# EgSA-Cube3.net
KiCad netlist of a schematic drawn in Altium Designer
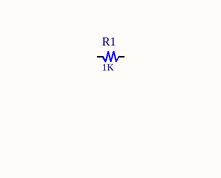
[diagram p0: EgSA-Cube3.SchDoc, top right]
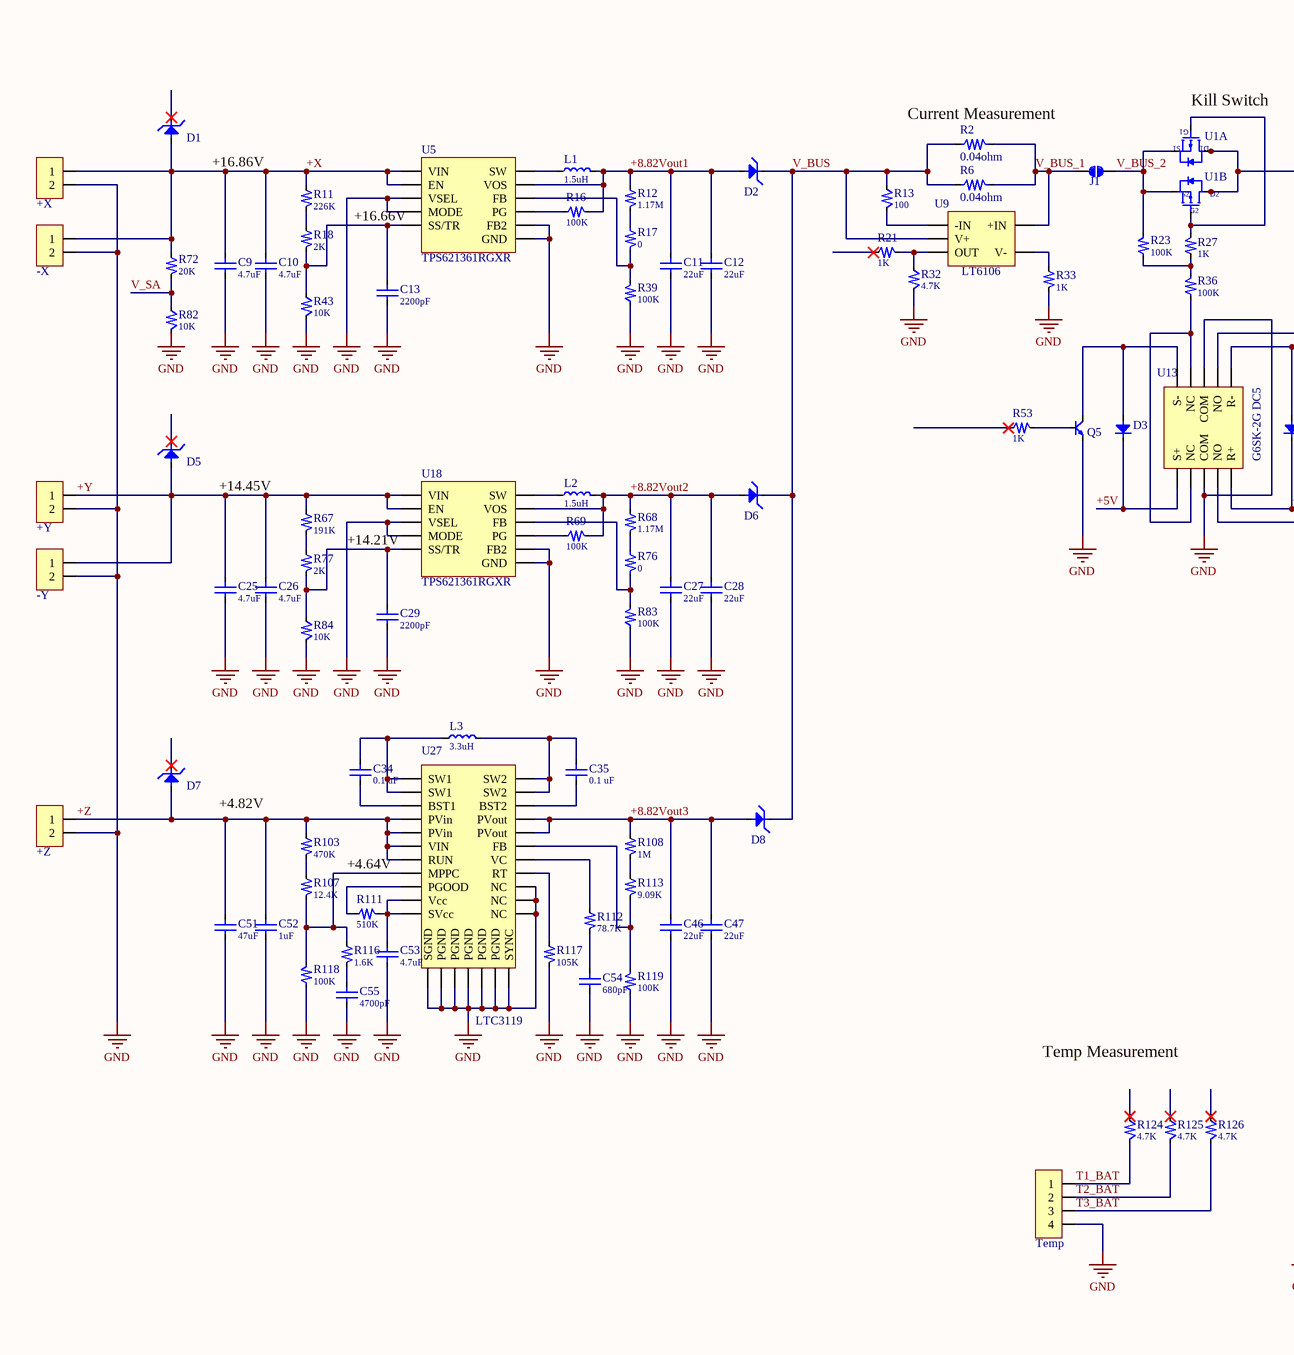
[diagram p1: EgSA-Cube3.SchDoc, bottom left]
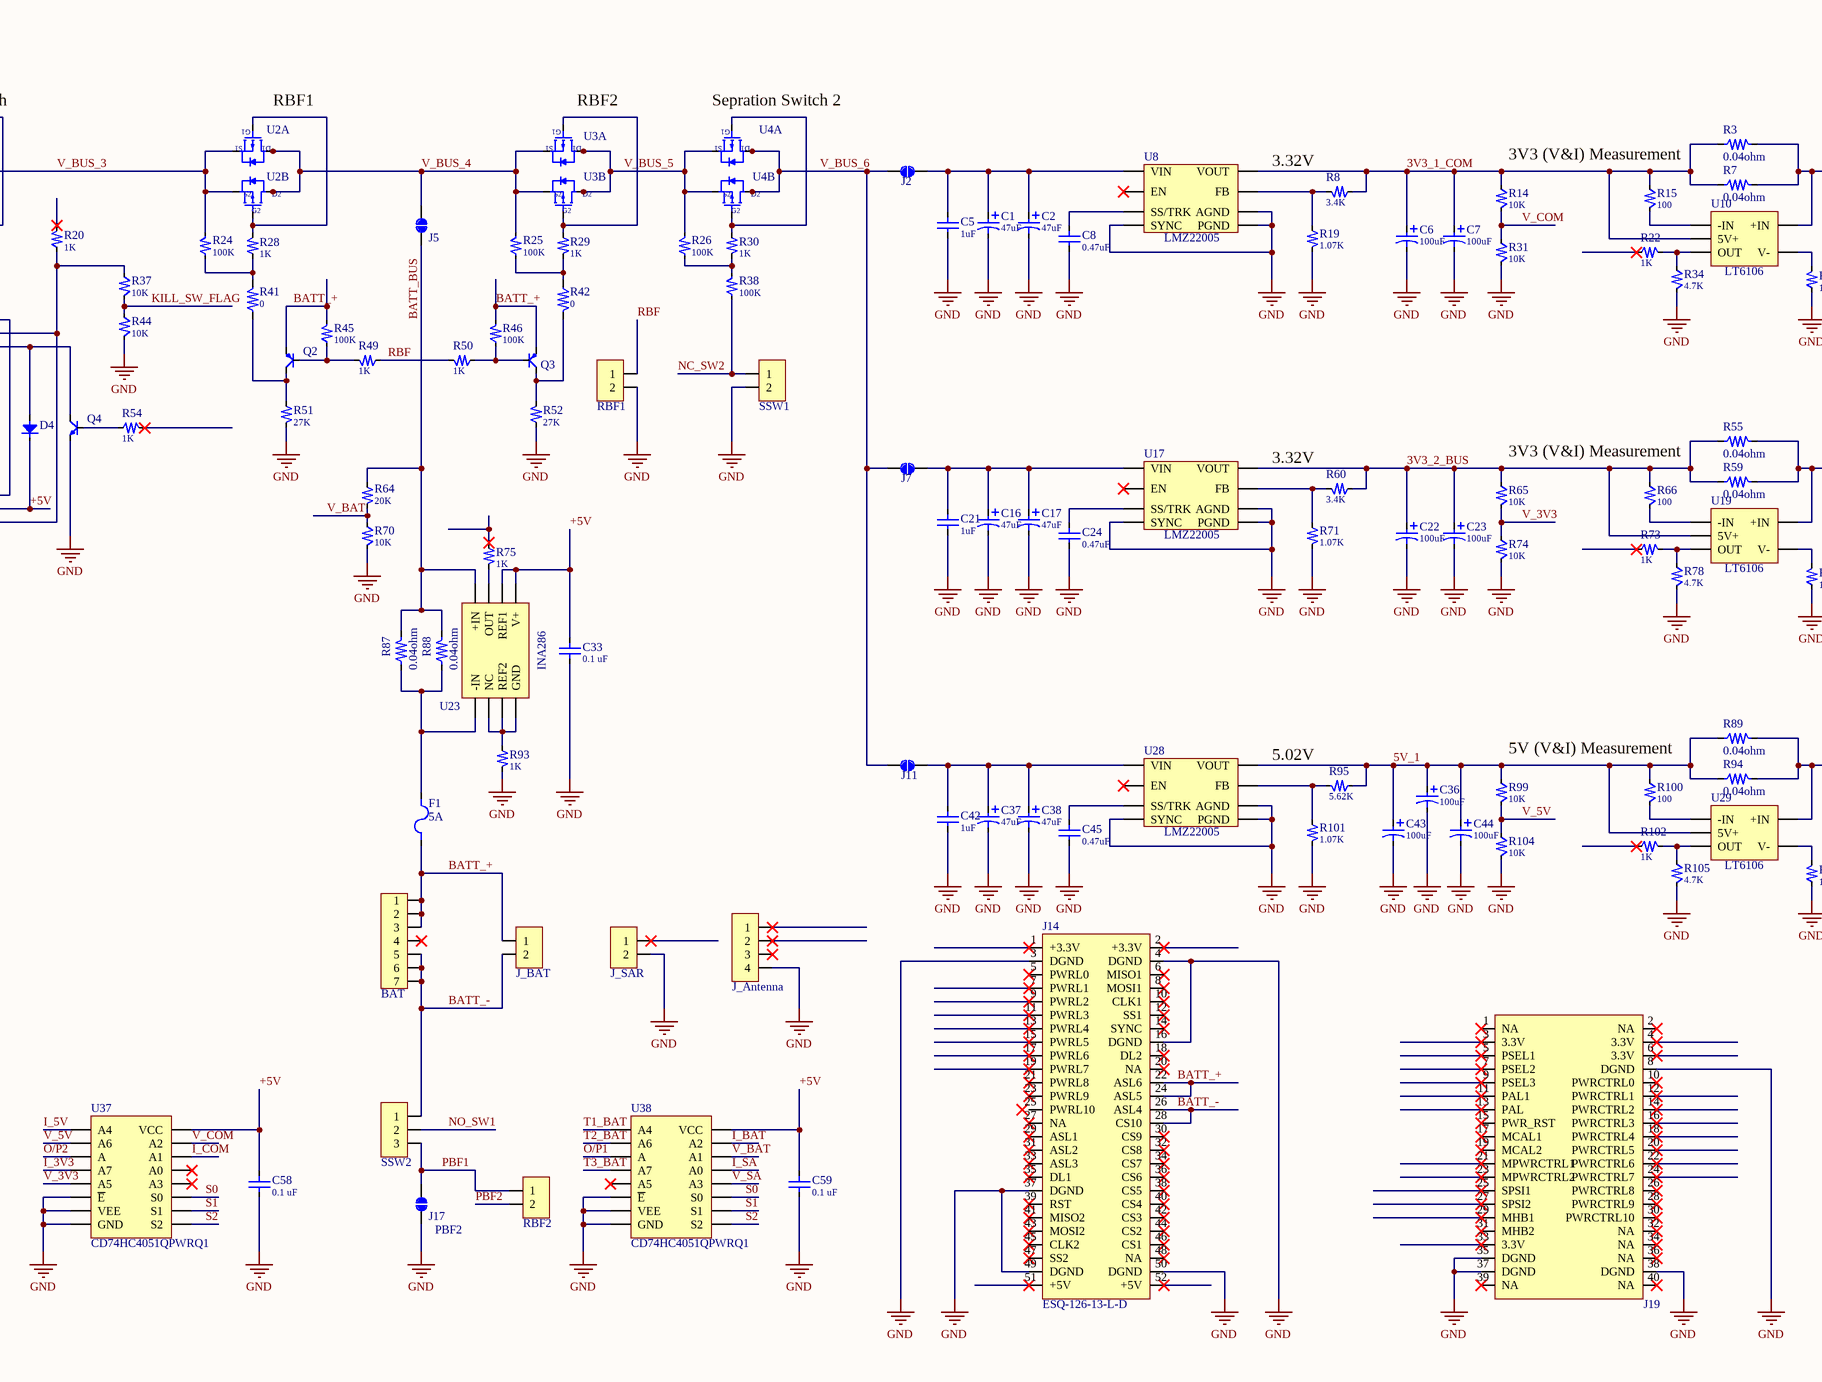
[diagram p2: EgSA-Cube3.SchDoc, bottom middle]
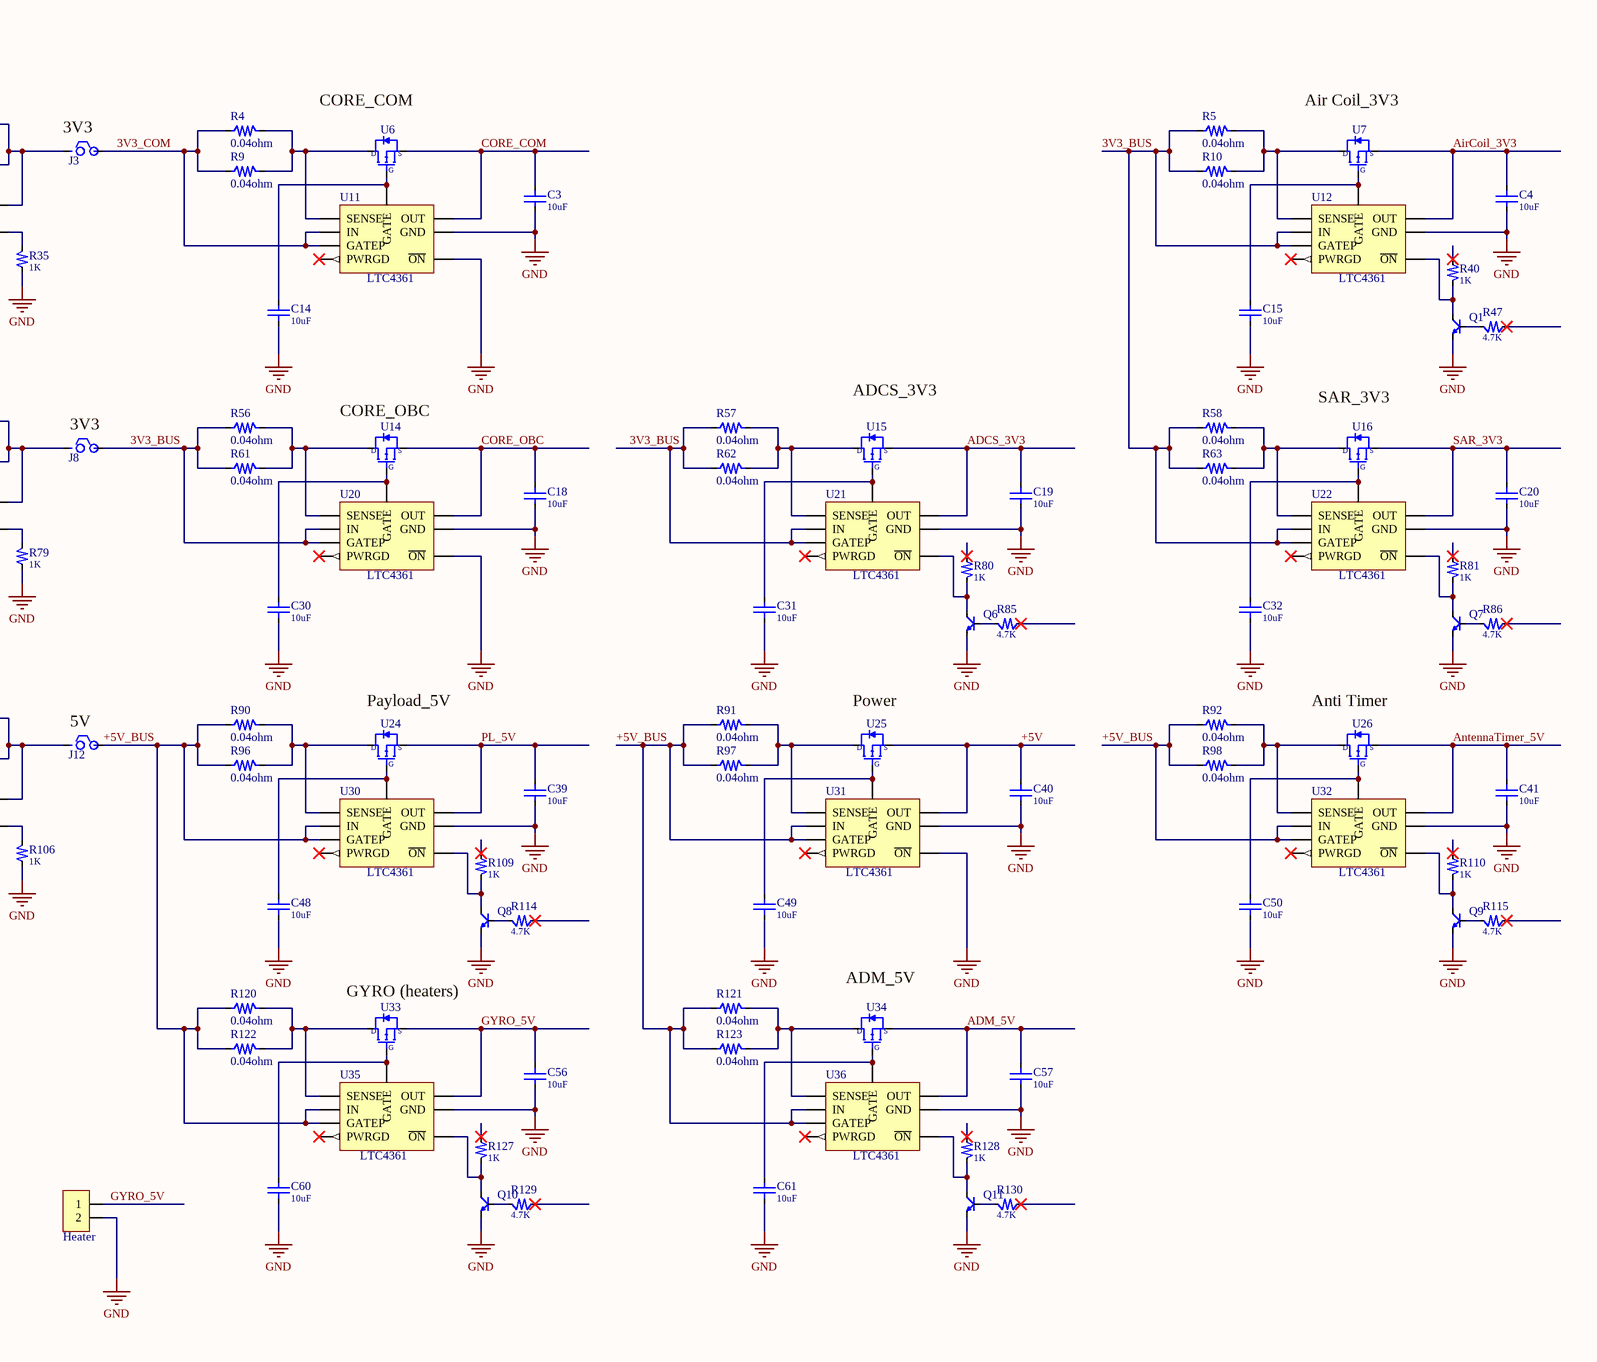
[diagram p3: EgSA-Cube3.SchDoc, bottom right]

(export (version "E")
  (design (tool "Eeschema 10.0.6"))
  (components
    (comp (ref "+X")
      (value "53261-0271")
      (footprint "53261-0271")
      (description "CONN HEADER SMD R/A 2POS 1.25MM")
      (fields
        (field (name "MANUFACTURER") "Molex, LLC")
        (field (name "MANUFACTURER PART NUMBER") "0532610271")
      )
      (libsource (lib "") (part "53261-0271_1"))
    )
    (comp (ref "+Y")
      (value "53261-0271")
      (footprint "53261-0271")
      (description "CONN HEADER SMD R/A 2POS 1.25MM")
      (fields
        (field (name "MANUFACTURER") "Molex, LLC")
        (field (name "MANUFACTURER PART NUMBER") "0532610271")
      )
      (libsource (lib "") (part "53261-0271_1"))
    )
    (comp (ref "+Z")
      (value "53261-0271")
      (footprint "53261-0271")
      (description "CONN HEADER SMD R/A 2POS 1.25MM")
      (fields
        (field (name "MANUFACTURER") "Molex, LLC")
        (field (name "MANUFACTURER PART NUMBER") "0532610271")
      )
      (libsource (lib "") (part "53261-0271_1"))
    )
    (comp (ref "-X")
      (value "53261-0271")
      (footprint "53261-0271")
      (description "CONN HEADER SMD R/A 2POS 1.25MM")
      (fields
        (field (name "MANUFACTURER") "Molex, LLC")
        (field (name "MANUFACTURER PART NUMBER") "0532610271")
      )
      (libsource (lib "") (part "53261-0271_1"))
    )
    (comp (ref "-Y")
      (value "53261-0271")
      (footprint "53261-0271")
      (description "CONN HEADER SMD R/A 2POS 1.25MM")
      (fields
        (field (name "MANUFACTURER") "Molex, LLC")
        (field (name "MANUFACTURER PART NUMBER") "0532610271")
      )
      (libsource (lib "") (part "53261-0271_1"))
    )
    (comp (ref "BAT")
      (value "53261-0771")
      (footprint "53261-0771")
      (description "CONN HEADER SMD R/A 7POS 1.25MM")
      (fields (field (name "MANUFACTURER") "Molex"))
      (libsource (lib "All_N_Cube3_Components") (part "53261-0771"))
    )
    (comp (ref "C1")
      (value "47uF")
      (footprint "T591B476M010ATE070")
      (description "CAP TANT POLY 47UF 10V 1411")
      (fields
        (field (name "MANUFACTURER") "KEMET")
        (field (name "MANUFACTURER PART NUMBER") "T591B476M010ATE070")
      )
      (libsource (lib "All_N_Cube3_Components") (part "T591B476M010ATE070"))
    )
    (comp (ref "C2")
      (value "47uF")
      (footprint "T591B476M010ATE070")
      (description "CAP TANT POLY 47UF 10V 1411")
      (fields
        (field (name "MANUFACTURER") "KEMET")
        (field (name "MANUFACTURER PART NUMBER") "T591B476M010ATE070")
      )
      (libsource (lib "All_N_Cube3_Components") (part "T591B476M010ATE070"))
    )
    (comp (ref "C3")
      (value "10uF")
      (footprint "CL21B106KOQNNNE")
      (description "CAP CER 10UF 16V X7R 0805")
      (fields
        (field (name "MANUFACTURER") "Samsung Electro-Mechanics")
        (field (name "MANUFACTURER PART NUMBER") "CL21B106KOQNNNE")
      )
      (libsource (lib "All_N_Cube3_Components") (part "CL21B106KOQNNNE"))
    )
    (comp (ref "C4")
      (value "10uF")
      (footprint "CL21B106KOQNNNE")
      (description "CAP CER 10UF 16V X7R 0805")
      (fields
        (field (name "MANUFACTURER") "Samsung Electro-Mechanics")
        (field (name "MANUFACTURER PART NUMBER") "CL21B106KOQNNNE")
      )
      (libsource (lib "All_N_Cube3_Components") (part "CL21B106KOQNNNE"))
    )
    (comp (ref "C5")
      (value "1uF")
      (footprint "CL21B105KAFVPNE")
      (description "CAP CER 1UF 25V X7R 0805")
      (fields
        (field (name "MANUFACTURER") "Samsung")
        (field (name "MANUFACTURER PART NUMBER") "CL21B105KAFVPNE")
      )
      (libsource (lib "All_N_Cube3_Components") (part "CL21B105KAFVPNE"))
    )
    (comp (ref "C6")
      (value "100uF")
      (footprint "T520B107M006ATE018")
      (description "CAP TANT POLY 100UF 6.3V 1411")
      (fields
        (field (name "MANUFACTURER") "KEMET")
        (field (name "MANUFACTURER PART NUMBER") "T520B107M006ATE018")
      )
      (libsource (lib "All_N_Cube3_Components") (part "T520B107M006ATE018"))
    )
    (comp (ref "C7")
      (value "100uF")
      (footprint "T520B107M006ATE018")
      (description "CAP TANT POLY 100UF 6.3V 1411")
      (fields
        (field (name "MANUFACTURER") "KEMET")
        (field (name "MANUFACTURER PART NUMBER") "T520B107M006ATE018")
      )
      (libsource (lib "All_N_Cube3_Components") (part "T520B107M006ATE018"))
    )
    (comp (ref "C8")
      (value "0.47uF")
      (footprint "0805YC474KAT2A")
      (description "CAP CER 0.47UF 16V X7R 0805")
      (fields
        (field (name "MANUFACTURER") "Kyocera AVX")
        (field (name "MANUFACTURER PART NUMBER") "0805YC474KAT2A")
      )
      (libsource (lib "All_N_Cube3_Components") (part "0805YC474KAT2A"))
    )
    (comp (ref "C9")
      (value "4.7uF")
      (footprint "CGA4J1X7R1V475K125AC")
      (description "CAP CER 4.7UF 35V X7R 0805")
      (fields
        (field (name "MANUFACTURER") "TDK")
        (field (name "MANUFACTURER PART NUMBER") "CGA4J1X7R1V475K125AC")
      )
      (libsource (lib "All_N_Cube3_Components") (part "CGA4J1X7R1V475K125AC"))
    )
    (comp (ref "C10")
      (value "4.7uF")
      (footprint "CGA4J1X7R1V475K125AC")
      (description "CAP CER 4.7UF 35V X7R 0805")
      (fields
        (field (name "MANUFACTURER") "TDK")
        (field (name "MANUFACTURER PART NUMBER") "CGA4J1X7R1V475K125AC")
      )
      (libsource (lib "All_N_Cube3_Components") (part "CGA4J1X7R1V475K125AC"))
    )
    (comp (ref "C11")
      (value "22uF")
      (footprint "C2012X5R1C226M125AC")
      (description "CAP CER 22UF 16V X5R 0805")
      (fields
        (field (name "MANUFACTURER") "TDK")
        (field (name "MANUFACTURER PART NUMBER") "C2012X5R1C226M125AC")
      )
      (libsource (lib "All_N_Cube3_Components") (part "C2012X5R1C226M125AC"))
    )
    (comp (ref "C12")
      (value "22uF")
      (footprint "C2012X5R1C226M125AC")
      (description "CAP CER 22UF 16V X5R 0805")
      (fields
        (field (name "MANUFACTURER") "TDK")
        (field (name "MANUFACTURER PART NUMBER") "C2012X5R1C226M125AC")
      )
      (libsource (lib "All_N_Cube3_Components") (part "C2012X5R1C226M125AC"))
    )
    (comp (ref "C13")
      (value "2200pF")
      (footprint "VJ0805Y222KXACW1BC")
      (description "CAP CER 2200PF 50V X7R 0805")
      (fields
        (field (name "MANUFACTURER") "Vishay")
        (field (name "MANUFACTURER PART NUMBER") "VJ0805Y222KXACW1BC")
      )
      (libsource (lib "All_N_Cube3_Components") (part "VJ0805Y222KXACW1BC"))
    )
    (comp (ref "C14")
      (value "10uF")
      (footprint "CL21B106KOQNNNE")
      (description "CAP CER 10UF 16V X7R 0805")
      (fields
        (field (name "MANUFACTURER") "Samsung Electro-Mechanics")
        (field (name "MANUFACTURER PART NUMBER") "CL21B106KOQNNNE")
      )
      (libsource (lib "All_N_Cube3_Components") (part "CL21B106KOQNNNE"))
    )
    (comp (ref "C15")
      (value "10uF")
      (footprint "CL21B106KOQNNNE")
      (description "CAP CER 10UF 16V X7R 0805")
      (fields
        (field (name "MANUFACTURER") "Samsung Electro-Mechanics")
        (field (name "MANUFACTURER PART NUMBER") "CL21B106KOQNNNE")
      )
      (libsource (lib "All_N_Cube3_Components") (part "CL21B106KOQNNNE"))
    )
    (comp (ref "C16")
      (value "47uF")
      (footprint "T591B476M010ATE070")
      (description "CAP TANT POLY 47UF 10V 1411")
      (fields
        (field (name "MANUFACTURER") "KEMET")
        (field (name "MANUFACTURER PART NUMBER") "T591B476M010ATE070")
      )
      (libsource (lib "All_N_Cube3_Components") (part "T591B476M010ATE070"))
    )
    (comp (ref "C17")
      (value "47uF")
      (footprint "T591B476M010ATE070")
      (description "CAP TANT POLY 47UF 10V 1411")
      (fields
        (field (name "MANUFACTURER") "KEMET")
        (field (name "MANUFACTURER PART NUMBER") "T591B476M010ATE070")
      )
      (libsource (lib "All_N_Cube3_Components") (part "T591B476M010ATE070"))
    )
    (comp (ref "C18")
      (value "10uF")
      (footprint "CL21B106KOQNNNE")
      (description "CAP CER 10UF 16V X7R 0805")
      (fields
        (field (name "MANUFACTURER") "Samsung Electro-Mechanics")
        (field (name "MANUFACTURER PART NUMBER") "CL21B106KOQNNNE")
      )
      (libsource (lib "All_N_Cube3_Components") (part "CL21B106KOQNNNE"))
    )
    (comp (ref "C19")
      (value "10uF")
      (footprint "CL21B106KOQNNNE")
      (description "CAP CER 10UF 16V X7R 0805")
      (fields
        (field (name "MANUFACTURER") "Samsung Electro-Mechanics")
        (field (name "MANUFACTURER PART NUMBER") "CL21B106KOQNNNE")
      )
      (libsource (lib "All_N_Cube3_Components") (part "CL21B106KOQNNNE"))
    )
    (comp (ref "C20")
      (value "10uF")
      (footprint "CL21B106KOQNNNE")
      (description "CAP CER 10UF 16V X7R 0805")
      (fields
        (field (name "MANUFACTURER") "Samsung Electro-Mechanics")
        (field (name "MANUFACTURER PART NUMBER") "CL21B106KOQNNNE")
      )
      (libsource (lib "All_N_Cube3_Components") (part "CL21B106KOQNNNE"))
    )
    (comp (ref "C21")
      (value "1uF")
      (footprint "CL21B105KAFVPNE")
      (description "CAP CER 1UF 25V X7R 0805")
      (fields
        (field (name "MANUFACTURER") "Samsung")
        (field (name "MANUFACTURER PART NUMBER") "CL21B105KAFVPNE")
      )
      (libsource (lib "All_N_Cube3_Components") (part "CL21B105KAFVPNE"))
    )
    (comp (ref "C22")
      (value "100uF")
      (footprint "T520B107M006ATE018")
      (description "CAP TANT POLY 100UF 6.3V 1411")
      (fields
        (field (name "MANUFACTURER") "KEMET")
        (field (name "MANUFACTURER PART NUMBER") "T520B107M006ATE018")
      )
      (libsource (lib "All_N_Cube3_Components") (part "T520B107M006ATE018"))
    )
    (comp (ref "C23")
      (value "100uF")
      (footprint "T520B107M006ATE018")
      (description "CAP TANT POLY 100UF 6.3V 1411")
      (fields
        (field (name "MANUFACTURER") "KEMET")
        (field (name "MANUFACTURER PART NUMBER") "T520B107M006ATE018")
      )
      (libsource (lib "All_N_Cube3_Components") (part "T520B107M006ATE018"))
    )
    (comp (ref "C24")
      (value "0.47uF")
      (footprint "0805YC474KAT2A")
      (description "CAP CER 0.47UF 16V X7R 0805")
      (fields
        (field (name "MANUFACTURER") "Kyocera AVX")
        (field (name "MANUFACTURER PART NUMBER") "0805YC474KAT2A")
      )
      (libsource (lib "All_N_Cube3_Components") (part "0805YC474KAT2A"))
    )
    (comp (ref "C25")
      (value "4.7uF")
      (footprint "CGA4J1X7R1V475K125AC")
      (description "CAP CER 4.7UF 35V X7R 0805")
      (fields
        (field (name "MANUFACTURER") "TDK")
        (field (name "MANUFACTURER PART NUMBER") "CGA4J1X7R1V475K125AC")
      )
      (libsource (lib "All_N_Cube3_Components") (part "CGA4J1X7R1V475K125AC"))
    )
    (comp (ref "C26")
      (value "4.7uF")
      (footprint "CGA4J1X7R1V475K125AC")
      (description "CAP CER 4.7UF 35V X7R 0805")
      (fields
        (field (name "MANUFACTURER") "TDK")
        (field (name "MANUFACTURER PART NUMBER") "CGA4J1X7R1V475K125AC")
      )
      (libsource (lib "All_N_Cube3_Components") (part "CGA4J1X7R1V475K125AC"))
    )
    (comp (ref "C27")
      (value "22uF")
      (footprint "C2012X5R1C226M125AC")
      (description "CAP CER 22UF 16V X5R 0805")
      (fields
        (field (name "MANUFACTURER") "TDK")
        (field (name "MANUFACTURER PART NUMBER") "C2012X5R1C226M125AC")
      )
      (libsource (lib "All_N_Cube3_Components") (part "C2012X5R1C226M125AC"))
    )
    (comp (ref "C28")
      (value "22uF")
      (footprint "C2012X5R1C226M125AC")
      (description "CAP CER 22UF 16V X5R 0805")
      (fields
        (field (name "MANUFACTURER") "TDK")
        (field (name "MANUFACTURER PART NUMBER") "C2012X5R1C226M125AC")
      )
      (libsource (lib "All_N_Cube3_Components") (part "C2012X5R1C226M125AC"))
    )
    (comp (ref "C29")
      (value "2200pF")
      (footprint "VJ0805Y222KXACW1BC")
      (description "CAP CER 2200PF 50V X7R 0805")
      (fields
        (field (name "MANUFACTURER") "Vishay")
        (field (name "MANUFACTURER PART NUMBER") "VJ0805Y222KXACW1BC")
      )
      (libsource (lib "All_N_Cube3_Components") (part "VJ0805Y222KXACW1BC"))
    )
    (comp (ref "C30")
      (value "10uF")
      (footprint "CL21B106KOQNNNE")
      (description "CAP CER 10UF 16V X7R 0805")
      (fields
        (field (name "MANUFACTURER") "Samsung Electro-Mechanics")
        (field (name "MANUFACTURER PART NUMBER") "CL21B106KOQNNNE")
      )
      (libsource (lib "All_N_Cube3_Components") (part "CL21B106KOQNNNE"))
    )
    (comp (ref "C31")
      (value "10uF")
      (footprint "CL21B106KOQNNNE")
      (description "CAP CER 10UF 16V X7R 0805")
      (fields
        (field (name "MANUFACTURER") "Samsung Electro-Mechanics")
        (field (name "MANUFACTURER PART NUMBER") "CL21B106KOQNNNE")
      )
      (libsource (lib "All_N_Cube3_Components") (part "CL21B106KOQNNNE"))
    )
    (comp (ref "C32")
      (value "10uF")
      (footprint "CL21B106KOQNNNE")
      (description "CAP CER 10UF 16V X7R 0805")
      (fields
        (field (name "MANUFACTURER") "Samsung Electro-Mechanics")
        (field (name "MANUFACTURER PART NUMBER") "CL21B106KOQNNNE")
      )
      (libsource (lib "All_N_Cube3_Components") (part "CL21B106KOQNNNE"))
    )
    (comp (ref "C33")
      (value "0.1 uF")
      (footprint "C0805C104J4RACTU")
      (description "CAP CER 0.1UF 16V X7R 0805")
      (fields
        (field (name "MANUFACTURER") "KEMET")
        (field (name "MANUFACTURER PART NUMBER") "C0805C104J4RACTU")
      )
      (libsource (lib "All_N_Cube3_Components") (part "C0805C104J4RACTU"))
    )
    (comp (ref "C34")
      (value "0.1 uF")
      (footprint "C0805C104J4RACTU")
      (description "CAP CER 0.1UF 16V X7R 0805")
      (fields
        (field (name "MANUFACTURER") "KEMET")
        (field (name "MANUFACTURER PART NUMBER") "C0805C104J4RACTU")
      )
      (libsource (lib "All_N_Cube3_Components") (part "C0805C104J4RACTU"))
    )
    (comp (ref "C35")
      (value "0.1 uF")
      (footprint "C0805C104J4RACTU")
      (description "CAP CER 0.1UF 16V X7R 0805")
      (fields
        (field (name "MANUFACTURER") "KEMET")
        (field (name "MANUFACTURER PART NUMBER") "C0805C104J4RACTU")
      )
      (libsource (lib "All_N_Cube3_Components") (part "C0805C104J4RACTU"))
    )
    (comp (ref "C36")
      (value "100uF")
      (footprint "T520B107M006ATE018")
      (description "CAP TANT POLY 100UF 6.3V 1411")
      (fields
        (field (name "MANUFACTURER") "KEMET")
        (field (name "MANUFACTURER PART NUMBER") "T520B107M006ATE018")
      )
      (libsource (lib "All_N_Cube3_Components") (part "T520B107M006ATE018"))
    )
    (comp (ref "C37")
      (value "47uF")
      (footprint "T591B476M010ATE070")
      (description "CAP TANT POLY 47UF 10V 1411")
      (fields
        (field (name "MANUFACTURER") "KEMET")
        (field (name "MANUFACTURER PART NUMBER") "T591B476M010ATE070")
      )
      (libsource (lib "All_N_Cube3_Components") (part "T591B476M010ATE070"))
    )
    (comp (ref "C38")
      (value "47uF")
      (footprint "T591B476M010ATE070")
      (description "CAP TANT POLY 47UF 10V 1411")
      (fields
        (field (name "MANUFACTURER") "KEMET")
        (field (name "MANUFACTURER PART NUMBER") "T591B476M010ATE070")
      )
      (libsource (lib "All_N_Cube3_Components") (part "T591B476M010ATE070"))
    )
    (comp (ref "C39")
      (value "10uF")
      (footprint "CL21B106KOQNNNE")
      (description "CAP CER 10UF 16V X7R 0805")
      (fields
        (field (name "MANUFACTURER") "Samsung Electro-Mechanics")
        (field (name "MANUFACTURER PART NUMBER") "CL21B106KOQNNNE")
      )
      (libsource (lib "All_N_Cube3_Components") (part "CL21B106KOQNNNE"))
    )
    (comp (ref "C40")
      (value "10uF")
      (footprint "CL21B106KOQNNNE")
      (description "CAP CER 10UF 16V X7R 0805")
      (fields
        (field (name "MANUFACTURER") "Samsung Electro-Mechanics")
        (field (name "MANUFACTURER PART NUMBER") "CL21B106KOQNNNE")
      )
      (libsource (lib "All_N_Cube3_Components") (part "CL21B106KOQNNNE"))
    )
    (comp (ref "C41")
      (value "10uF")
      (footprint "CL21B106KOQNNNE")
      (description "CAP CER 10UF 16V X7R 0805")
      (fields
        (field (name "MANUFACTURER") "Samsung Electro-Mechanics")
        (field (name "MANUFACTURER PART NUMBER") "CL21B106KOQNNNE")
      )
      (libsource (lib "All_N_Cube3_Components") (part "CL21B106KOQNNNE"))
    )
    (comp (ref "C42")
      (value "1uF")
      (footprint "CL21B105KAFVPNE")
      (description "CAP CER 1UF 25V X7R 0805")
      (fields
        (field (name "MANUFACTURER") "Samsung")
        (field (name "MANUFACTURER PART NUMBER") "CL21B105KAFVPNE")
      )
      (libsource (lib "All_N_Cube3_Components") (part "CL21B105KAFVPNE"))
    )
    (comp (ref "C43")
      (value "100uF")
      (footprint "T520B107M006ATE018")
      (description "CAP TANT POLY 100UF 6.3V 1411")
      (fields
        (field (name "MANUFACTURER") "KEMET")
        (field (name "MANUFACTURER PART NUMBER") "T520B107M006ATE018")
      )
      (libsource (lib "All_N_Cube3_Components") (part "T520B107M006ATE018"))
    )
    (comp (ref "C44")
      (value "100uF")
      (footprint "T520B107M006ATE018")
      (description "CAP TANT POLY 100UF 6.3V 1411")
      (fields
        (field (name "MANUFACTURER") "KEMET")
        (field (name "MANUFACTURER PART NUMBER") "T520B107M006ATE018")
      )
      (libsource (lib "All_N_Cube3_Components") (part "T520B107M006ATE018"))
    )
    (comp (ref "C45")
      (value "0.47uF")
      (footprint "0805YC474KAT2A")
      (description "CAP CER 0.47UF 16V X7R 0805")
      (fields
        (field (name "MANUFACTURER") "Kyocera AVX")
        (field (name "MANUFACTURER PART NUMBER") "0805YC474KAT2A")
      )
      (libsource (lib "All_N_Cube3_Components") (part "0805YC474KAT2A"))
    )
    (comp (ref "C46")
      (value "22uF")
      (footprint "C2012X5R1C226M125AC")
      (description "CAP CER 22UF 16V X5R 0805")
      (fields
        (field (name "MANUFACTURER") "TDK")
        (field (name "MANUFACTURER PART NUMBER") "C2012X5R1C226M125AC")
      )
      (libsource (lib "All_N_Cube3_Components") (part "C2012X5R1C226M125AC"))
    )
    (comp (ref "C47")
      (value "22uF")
      (footprint "C2012X5R1C226M125AC")
      (description "CAP CER 22UF 16V X5R 0805")
      (fields
        (field (name "MANUFACTURER") "TDK")
        (field (name "MANUFACTURER PART NUMBER") "C2012X5R1C226M125AC")
      )
      (libsource (lib "All_N_Cube3_Components") (part "C2012X5R1C226M125AC"))
    )
    (comp (ref "C48")
      (value "10uF")
      (footprint "CL21B106KOQNNNE")
      (description "CAP CER 10UF 16V X7R 0805")
      (fields
        (field (name "MANUFACTURER") "Samsung Electro-Mechanics")
        (field (name "MANUFACTURER PART NUMBER") "CL21B106KOQNNNE")
      )
      (libsource (lib "All_N_Cube3_Components") (part "CL21B106KOQNNNE"))
    )
    (comp (ref "C49")
      (value "10uF")
      (footprint "CL21B106KOQNNNE")
      (description "CAP CER 10UF 16V X7R 0805")
      (fields
        (field (name "MANUFACTURER") "Samsung Electro-Mechanics")
        (field (name "MANUFACTURER PART NUMBER") "CL21B106KOQNNNE")
      )
      (libsource (lib "All_N_Cube3_Components") (part "CL21B106KOQNNNE"))
    )
    (comp (ref "C50")
      (value "10uF")
      (footprint "CL21B106KOQNNNE")
      (description "CAP CER 10UF 16V X7R 0805")
      (fields
        (field (name "MANUFACTURER") "Samsung Electro-Mechanics")
        (field (name "MANUFACTURER PART NUMBER") "CL21B106KOQNNNE")
      )
      (libsource (lib "All_N_Cube3_Components") (part "CL21B106KOQNNNE"))
    )
    (comp (ref "C51")
      (value "47uF")
      (footprint "C2012X5R1A476M125AC")
      (description "CAP CER 47UF 10V X5R 0805")
      (fields
        (field (name "MANUFACTURER") "TDK")
        (field (name "MANUFACTURER PART NUMBER") "C2012X5R1A476M125AC")
      )
      (libsource (lib "All_N_Cube3_Components") (part "C2012X5R1A476M125AC"))
    )
    (comp (ref "C52")
      (value "1uF")
      (footprint "CL21B105KAFVPNE")
      (description "CAP CER 1UF 25V X7R 0805")
      (fields
        (field (name "MANUFACTURER") "Samsung")
        (field (name "MANUFACTURER PART NUMBER") "CL21B105KAFVPNE")
      )
      (libsource (lib "All_N_Cube3_Components") (part "CL21B105KAFVPNE"))
    )
    (comp (ref "C53")
      (value "4.7uF")
      (footprint "CGA4J1X7R1V475K125AC")
      (description "CAP CER 4.7UF 35V X7R 0805")
      (fields
        (field (name "MANUFACTURER") "TDK")
        (field (name "MANUFACTURER PART NUMBER") "CGA4J1X7R1V475K125AC")
      )
      (libsource (lib "All_N_Cube3_Components") (part "CGA4J1X7R1V475K125AC"))
    )
    (comp (ref "C54")
      (value "680pF")
      (footprint "VJ0805Y681JXXCW1BC")
      (description "CAP CER 680PF 25V X7R 0805")
      (fields
        (field (name "MANUFACTURER") "Vishay Vitramon")
        (field (name "MANUFACTURER PART NUMBER") "VJ0805Y681JXXCW1BC")
      )
      (libsource (lib "All_N_Cube3_Components") (part "VJ0805Y681JXXCW1BC"))
    )
    (comp (ref "C55")
      (value "4700pF")
      (footprint "C0805C472K4RAC7800")
      (description "CAP CER 4700PF 16V X7R 0805")
      (fields
        (field (name "MANUFACTURER") "KEMET")
        (field (name "MANUFACTURER PART NUMBER") "C0805C472K4RAC7800")
      )
      (libsource (lib "All_N_Cube3_Components") (part "C0805C472K4RAC7800"))
    )
    (comp (ref "C56")
      (value "10uF")
      (footprint "CL21B106KOQNNNE")
      (description "CAP CER 10UF 16V X7R 0805")
      (fields
        (field (name "MANUFACTURER") "Samsung Electro-Mechanics")
        (field (name "MANUFACTURER PART NUMBER") "CL21B106KOQNNNE")
      )
      (libsource (lib "All_N_Cube3_Components") (part "CL21B106KOQNNNE"))
    )
    (comp (ref "C57")
      (value "10uF")
      (footprint "CL21B106KOQNNNE")
      (description "CAP CER 10UF 16V X7R 0805")
      (fields
        (field (name "MANUFACTURER") "Samsung Electro-Mechanics")
        (field (name "MANUFACTURER PART NUMBER") "CL21B106KOQNNNE")
      )
      (libsource (lib "All_N_Cube3_Components") (part "CL21B106KOQNNNE"))
    )
    (comp (ref "C58")
      (value "0.1 uF")
      (footprint "C0805C104J4RACTU")
      (description "CAP CER 0.1UF 16V X7R 0805")
      (fields
        (field (name "MANUFACTURER") "KEMET")
        (field (name "MANUFACTURER PART NUMBER") "C0805C104J4RACTU")
      )
      (libsource (lib "All_N_Cube3_Components") (part "C0805C104J4RACTU"))
    )
    (comp (ref "C59")
      (value "0.1 uF")
      (footprint "C0805C104J4RACTU")
      (description "CAP CER 0.1UF 16V X7R 0805")
      (fields
        (field (name "MANUFACTURER") "KEMET")
        (field (name "MANUFACTURER PART NUMBER") "C0805C104J4RACTU")
      )
      (libsource (lib "All_N_Cube3_Components") (part "C0805C104J4RACTU"))
    )
    (comp (ref "C60")
      (value "10uF")
      (footprint "CL21B106KOQNNNE")
      (description "CAP CER 10UF 16V X7R 0805")
      (fields
        (field (name "MANUFACTURER") "Samsung Electro-Mechanics")
        (field (name "MANUFACTURER PART NUMBER") "CL21B106KOQNNNE")
      )
      (libsource (lib "All_N_Cube3_Components") (part "CL21B106KOQNNNE"))
    )
    (comp (ref "C61")
      (value "10uF")
      (footprint "CL21B106KOQNNNE")
      (description "CAP CER 10UF 16V X7R 0805")
      (fields
        (field (name "MANUFACTURER") "Samsung Electro-Mechanics")
        (field (name "MANUFACTURER PART NUMBER") "CL21B106KOQNNNE")
      )
      (libsource (lib "All_N_Cube3_Components") (part "CL21B106KOQNNNE"))
    )
    (comp (ref "D1")
      (value "SL22PL-TP")
      (footprint "SL22PL-TP")
      (description "DIODE SCHOTTKY 20V 2A SOD-123FL")
      (fields (field (name "MANUFACTURER") "MCC"))
      (libsource (lib "RG_Projects") (part "SL22PL-TP"))
    )
    (comp (ref "D2")
      (value "SL22PL-TP")
      (footprint "SL22PL-TP")
      (description "DIODE SCHOTTKY 20V 2A SOD-123FL")
      (fields (field (name "MANUFACTURER") "MCC"))
      (libsource (lib "RG_Projects") (part "SL22PL-TP"))
    )
    (comp (ref "D3")
      (value "MMSD459A")
      (footprint "MMSD459A")
      (description "DIODE GEN PURP SOD123")
      (fields (field (name "MANUFACTURER") "ON Semiconductor") (field (name "BASE PART NUMBER") "MMSD459"))
      (libsource (lib "All_N_Cube3_Components") (part "MMSD459A"))
    )
    (comp (ref "D4")
      (value "MMSD459A")
      (footprint "MMSD459A")
      (description "DIODE GEN PURP SOD123")
      (fields (field (name "MANUFACTURER") "ON Semiconductor") (field (name "BASE PART NUMBER") "MMSD459"))
      (libsource (lib "All_N_Cube3_Components") (part "MMSD459A"))
    )
    (comp (ref "D5")
      (value "SL22PL-TP")
      (footprint "SL22PL-TP")
      (description "DIODE SCHOTTKY 20V 2A SOD-123FL")
      (fields (field (name "MANUFACTURER") "MCC"))
      (libsource (lib "RG_Projects") (part "SL22PL-TP"))
    )
    (comp (ref "D6")
      (value "SL22PL-TP")
      (footprint "SL22PL-TP")
      (description "DIODE SCHOTTKY 20V 2A SOD-123FL")
      (fields (field (name "MANUFACTURER") "MCC"))
      (libsource (lib "RG_Projects") (part "SL22PL-TP"))
    )
    (comp (ref "D7")
      (value "SL22PL-TP")
      (footprint "SL22PL-TP")
      (description "DIODE SCHOTTKY 20V 2A SOD-123FL")
      (fields (field (name "MANUFACTURER") "MCC"))
      (libsource (lib "RG_Projects") (part "SL22PL-TP"))
    )
    (comp (ref "D8")
      (value "SL22PL-TP")
      (footprint "SL22PL-TP")
      (description "DIODE SCHOTTKY 20V 2A SOD-123FL")
      (fields (field (name "MANUFACTURER") "MCC"))
      (libsource (lib "RG_Projects") (part "SL22PL-TP"))
    )
    (comp (ref "F1")
      (value "1206L500/12SLPR")
      (footprint "1206L500/12SLPR")
      (description "PTC RESET FUSE 5.0A 12V 1206")
      (fields (field (name "MANUFACTURER") "Littelfuse") (field (name "TRIP CURRENT") "5A"))
      (libsource (lib "All_N_Cube3_Components") (part "1206L500/12SLPR"))
    )
    (comp (ref "Heater")
      (value "53261-0271")
      (footprint "53261-0271")
      (description "CONN HEADER SMD R/A 2POS 1.25MM")
      (fields
        (field (name "MANUFACTURER") "Molex, LLC")
        (field (name "MANUFACTURER PART NUMBER") "0532610271")
      )
      (libsource (lib "") (part "53261-0271_1"))
    )
    (comp (ref "J1")
      (value "JUMPER")
      (footprint "JUMPER")
      (description "OPTION SELECTION 2POS PAD")
      (libsource (lib "RG_Projects") (part "JUMPER"))
    )
    (comp (ref "J2")
      (value "JUMPER")
      (footprint "JUMPER")
      (description "OPTION SELECTION 2POS PAD")
      (libsource (lib "RG_Projects") (part "JUMPER"))
    )
    (comp (ref "J3")
      (value "ESW-102-13-L-S")
      (footprint "ESW-102-13-L-S")
      (description "CONN SOCKET 2POS 0.1 GOLD PCB")
      (fields (field (name "MANUFACTURER") "Samtec"))
      (libsource (lib "All_N_Cube3_Components") (part "ESW-102-13-L-S"))
    )
    (comp (ref "J5")
      (value "JUMPER")
      (footprint "JUMPER")
      (description "OPTION SELECTION 2POS PAD")
      (libsource (lib "") (part "JUMPER_1"))
    )
    (comp (ref "J7")
      (value "JUMPER")
      (footprint "JUMPER")
      (description "OPTION SELECTION 2POS PAD")
      (libsource (lib "RG_Projects") (part "JUMPER"))
    )
    (comp (ref "J8")
      (value "ESW-102-13-L-S")
      (footprint "ESW-102-13-L-S")
      (description "CONN SOCKET 2POS 0.1 GOLD PCB")
      (fields (field (name "MANUFACTURER") "Samtec"))
      (libsource (lib "All_N_Cube3_Components") (part "ESW-102-13-L-S"))
    )
    (comp (ref "J11")
      (value "JUMPER")
      (footprint "JUMPER")
      (description "OPTION SELECTION 2POS PAD")
      (libsource (lib "RG_Projects") (part "JUMPER"))
    )
    (comp (ref "J12")
      (value "ESW-102-13-L-S")
      (footprint "ESW-102-13-L-S")
      (description "CONN SOCKET 2POS 0.1 GOLD PCB")
      (fields (field (name "MANUFACTURER") "Samtec"))
      (libsource (lib "All_N_Cube3_Components") (part "ESW-102-13-L-S"))
    )
    (comp (ref "J14")
      (value "ESQ-126-13-L-D")
      (footprint "ESQ-126-13-L-D")
      (description "CONN SOCKET 52POS 0.1 GOLD PCB")
      (fields (field (name "MANUFACTURER") "Samtec"))
      (libsource (lib "RG_Projects") (part "ESQ-126-13-L-D"))
    )
    (comp (ref "J17")
      (value "JUMPER")
      (footprint "JUMPER")
      (description "OPTION SELECTION 2POS PAD")
      (libsource (lib "") (part "JUMPER_1"))
    )
    (comp (ref "J19")
      (value "ESQ-120-13-L-D")
      (footprint "ESQ-120-13-L-D")
      (description "CONN SOCKET 40POS 0.1 GOLD PCB")
      (libsource (lib "RG_Projects") (part "ESQ-120-13-L-D"))
    )
    (comp (ref "J_Antenna")
      (value "53261-0471")
      (footprint "53261-0471")
      (description "CONN HEADER SMD R/A 4POS 1.25MM")
      (fields (field (name "MANUFACTURER") "Molex"))
      (libsource (lib "RG_Projects") (part "53261-0471"))
    )
    (comp (ref "J_BAT")
      (value "53261-0271")
      (footprint "53261-0271")
      (description "CONN HEADER SMD R/A 2POS 1.25MM")
      (fields
        (field (name "MANUFACTURER") "Molex, LLC")
        (field (name "MANUFACTURER PART NUMBER") "0532610271")
      )
      (libsource (lib "All_N_Cube3_Components") (part "53261-0271"))
    )
    (comp (ref "J_SAR")
      (value "53261-0271")
      (footprint "53261-0271")
      (description "CONN HEADER SMD R/A 2POS 1.25MM")
      (fields
        (field (name "MANUFACTURER") "Molex, LLC")
        (field (name "MANUFACTURER PART NUMBER") "0532610271")
      )
      (libsource (lib "RG_Projects") (part "53261-0271"))
    )
    (comp (ref "L1")
      (value "1.5uH")
      (footprint "XEL4020-152MEB")
      (description "FIXED IND 1.5UH 7.5A 23.6 MOHM")
      (fields
        (field (name "MANUFACTURER") "Coilcraft")
        (field (name "MANUFACTURER PART NUMBER") "XEL4020-152MEB")
      )
      (libsource (lib "All_N_Cube3_Components") (part "XEL4020-152MEB"))
    )
    (comp (ref "L2")
      (value "1.5uH")
      (footprint "XEL4020-152MEB")
      (description "FIXED IND 1.5UH 7.5A 23.6 MOHM")
      (fields
        (field (name "MANUFACTURER") "Coilcraft")
        (field (name "MANUFACTURER PART NUMBER") "XEL4020-152MEB")
      )
      (libsource (lib "All_N_Cube3_Components") (part "XEL4020-152MEB"))
    )
    (comp (ref "L3")
      (value "3.3uH")
      (footprint "XEL4030-332MEC")
      (description "FIXED IND 3.3UH 6.6A 28.6 MOHM")
      (fields
        (field (name "MANUFACTURER") "Coilcraft")
        (field (name "MANUFACTURER PART NUMBER") "XEL4030-332MEC")
      )
      (libsource (lib "All_N_Cube3_Components") (part "XEL4030-332MEC"))
    )
    (comp (ref "Q1")
      (value "SMMBT3904LT3G")
      (footprint "SMMBT3904LT3G")
      (description "TRANS NPN 40V 0.2A SOT23")
      (fields (field (name "MANUFACTURER") "ON Semiconductor"))
      (libsource (lib "All_N_Cube3_Components") (part "SMMBT3904LT3G"))
    )
    (comp (ref "Q2")
      (value "CMPT404A TR")
      (footprint "CMPT404A TR")
      (description "Bipolar Transistors - BJT PNP Silicon Chopper SMT Transistor")
      (fields (field (name "MANUFACTURER") "Central Semiconductor"))
      (libsource (lib "All_N_Cube3_Components") (part "CMPT404A TR"))
    )
    (comp (ref "Q3")
      (value "CMPT404A TR")
      (footprint "CMPT404A TR")
      (description "Bipolar Transistors - BJT PNP Silicon Chopper SMT Transistor")
      (fields (field (name "MANUFACTURER") "Central Semiconductor"))
      (libsource (lib "All_N_Cube3_Components") (part "CMPT404A TR"))
    )
    (comp (ref "Q4")
      (value "SMMBT3904LT3G")
      (footprint "SMMBT3904LT3G")
      (description "TRANS NPN 40V 0.2A SOT23")
      (fields (field (name "MANUFACTURER") "ON Semiconductor"))
      (libsource (lib "All_N_Cube3_Components") (part "SMMBT3904LT3G"))
    )
    (comp (ref "Q5")
      (value "SMMBT3904LT3G")
      (footprint "SMMBT3904LT3G")
      (description "TRANS NPN 40V 0.2A SOT23")
      (fields (field (name "MANUFACTURER") "ON Semiconductor"))
      (libsource (lib "All_N_Cube3_Components") (part "SMMBT3904LT3G"))
    )
    (comp (ref "Q6")
      (value "SMMBT3904LT3G")
      (footprint "SMMBT3904LT3G")
      (description "TRANS NPN 40V 0.2A SOT23")
      (fields (field (name "MANUFACTURER") "ON Semiconductor"))
      (libsource (lib "All_N_Cube3_Components") (part "SMMBT3904LT3G"))
    )
    (comp (ref "Q7")
      (value "SMMBT3904LT3G")
      (footprint "SMMBT3904LT3G")
      (description "TRANS NPN 40V 0.2A SOT23")
      (fields (field (name "MANUFACTURER") "ON Semiconductor"))
      (libsource (lib "All_N_Cube3_Components") (part "SMMBT3904LT3G"))
    )
    (comp (ref "Q8")
      (value "SMMBT3904LT3G")
      (footprint "SMMBT3904LT3G")
      (description "TRANS NPN 40V 0.2A SOT23")
      (fields (field (name "MANUFACTURER") "ON Semiconductor"))
      (libsource (lib "All_N_Cube3_Components") (part "SMMBT3904LT3G"))
    )
    (comp (ref "Q9")
      (value "SMMBT3904LT3G")
      (footprint "SMMBT3904LT3G")
      (description "TRANS NPN 40V 0.2A SOT23")
      (fields (field (name "MANUFACTURER") "ON Semiconductor"))
      (libsource (lib "All_N_Cube3_Components") (part "SMMBT3904LT3G"))
    )
    (comp (ref "Q10")
      (value "SMMBT3904LT3G")
      (footprint "SMMBT3904LT3G")
      (description "TRANS NPN 40V 0.2A SOT23")
      (fields (field (name "MANUFACTURER") "ON Semiconductor"))
      (libsource (lib "All_N_Cube3_Components") (part "SMMBT3904LT3G"))
    )
    (comp (ref "Q11")
      (value "SMMBT3904LT3G")
      (footprint "SMMBT3904LT3G")
      (description "TRANS NPN 40V 0.2A SOT23")
      (fields (field (name "MANUFACTURER") "ON Semiconductor"))
      (libsource (lib "All_N_Cube3_Components") (part "SMMBT3904LT3G"))
    )
    (comp (ref "R1")
      (value "1K")
      (footprint "All_N_Cube3_Components:ERJ-P6WJ102V")
      (description "RES SMD 1K OHM 5% 1/2W 0805")
      (fields
        (field (name "MANUFACTURER") "Panasonic Electronic Components")
        (field (name "MANUFACTURER PART NUMBER") "ERJ-P6WJ102V")
      )
      (libsource (lib "All_N_Cube3_Components") (part "ERJ-P6WJ102V"))
    )
    (comp (ref "R2")
      (value "0.04ohm")
      (footprint "All_N_Cube3_Components:RL3720WT-R040-G")
      (description "RES 0.04 OHM 1W 1508 WIDE")
      (fields
        (field (name "MANUFACTURER") "Susumu")
        (field (name "MANUFACTURER PART NUMBER") "RL3720WT-R040-G")
      )
      (libsource (lib "All_N_Cube3_Components") (part "RL3720WT-R040-G"))
    )
    (comp (ref "R3")
      (value "0.04ohm")
      (footprint "All_N_Cube3_Components:RL3720WT-R040-G")
      (description "RES 0.04 OHM 1W 1508 WIDE")
      (fields
        (field (name "MANUFACTURER") "Susumu")
        (field (name "MANUFACTURER PART NUMBER") "RL3720WT-R040-G")
      )
      (libsource (lib "All_N_Cube3_Components") (part "RL3720WT-R040-G"))
    )
    (comp (ref "R4")
      (value "0.04ohm")
      (footprint "All_N_Cube3_Components:RL3720WT-R040-G")
      (description "RES 0.04 OHM 1W 1508 WIDE")
      (fields
        (field (name "MANUFACTURER") "Susumu")
        (field (name "MANUFACTURER PART NUMBER") "RL3720WT-R040-G")
      )
      (libsource (lib "All_N_Cube3_Components") (part "RL3720WT-R040-G"))
    )
    (comp (ref "R5")
      (value "0.04ohm")
      (footprint "All_N_Cube3_Components:RL3720WT-R040-G")
      (description "RES 0.04 OHM 1W 1508 WIDE")
      (fields
        (field (name "MANUFACTURER") "Susumu")
        (field (name "MANUFACTURER PART NUMBER") "RL3720WT-R040-G")
      )
      (libsource (lib "All_N_Cube3_Components") (part "RL3720WT-R040-G"))
    )
    (comp (ref "R6")
      (value "0.04ohm")
      (footprint "All_N_Cube3_Components:RL3720WT-R040-G")
      (description "RES 0.04 OHM 1W 1508 WIDE")
      (fields
        (field (name "MANUFACTURER") "Susumu")
        (field (name "MANUFACTURER PART NUMBER") "RL3720WT-R040-G")
      )
      (libsource (lib "All_N_Cube3_Components") (part "RL3720WT-R040-G"))
    )
    (comp (ref "R7")
      (value "0.04ohm")
      (footprint "All_N_Cube3_Components:RL3720WT-R040-G")
      (description "RES 0.04 OHM 1W 1508 WIDE")
      (fields
        (field (name "MANUFACTURER") "Susumu")
        (field (name "MANUFACTURER PART NUMBER") "RL3720WT-R040-G")
      )
      (libsource (lib "All_N_Cube3_Components") (part "RL3720WT-R040-G"))
    )
    (comp (ref "R8")
      (value "3.4K")
      (footprint "ERJ-P06F3401V")
      (description "RES 3.4 KOHM 1% 1/2W 0805")
      (fields
        (field (name "MANUFACTURER") "Panasonic")
        (field (name "MANUFACTURER PART NUMBER") "ERJP06F3401V")
      )
      (libsource (lib "All_N_Cube3_Components") (part "ERJ-P06F3401V"))
    )
    (comp (ref "R9")
      (value "0.04ohm")
      (footprint "All_N_Cube3_Components:RL3720WT-R040-G")
      (description "RES 0.04 OHM 1W 1508 WIDE")
      (fields
        (field (name "MANUFACTURER") "Susumu")
        (field (name "MANUFACTURER PART NUMBER") "RL3720WT-R040-G")
      )
      (libsource (lib "All_N_Cube3_Components") (part "RL3720WT-R040-G"))
    )
    (comp (ref "R10")
      (value "0.04ohm")
      (footprint "All_N_Cube3_Components:RL3720WT-R040-G")
      (description "RES 0.04 OHM 1W 1508 WIDE")
      (fields
        (field (name "MANUFACTURER") "Susumu")
        (field (name "MANUFACTURER PART NUMBER") "RL3720WT-R040-G")
      )
      (libsource (lib "All_N_Cube3_Components") (part "RL3720WT-R040-G"))
    )
    (comp (ref "R11")
      (value "226K")
      (footprint "RK73H2ATTD2263F")
      (description "RES 226K OHM 1% 1/4W 0805")
      (fields
        (field (name "MANUFACTURER") "KOA Speer")
        (field (name "MANUFACTURER PART NUMBER") "RK73H2ATTD2263F")
      )
      (libsource (lib "All_N_Cube3_Components") (part "RK73H2ATTD2263F"))
    )
    (comp (ref "R12")
      (value "1.17M")
      (footprint "RT0805BRD071M17L")
      (description "RES 1.17M OHM 0.1% 1/8W 0805")
      (fields
        (field (name "MANUFACTURER") "Yageo")
        (field (name "MANUFACTURER PART NUMBER") "RT0805BRD071M17L")
      )
      (libsource (lib "All_N_Cube3_Components") (part "RT0805BRD071M17L"))
    )
    (comp (ref "R13")
      (value "100")
      (footprint "All_N_Cube3_Components:CRCW0805100RFKEAHP")
      (description "RES 100 OHM 1% 1/2W 0805")
      (fields
        (field (name "MANUFACTURER") "Vishay Dale")
        (field (name "MANUFACTURER PART NUMBER") "CRCW0805100RFKEAHP")
      )
      (libsource (lib "All_N_Cube3_Components") (part "CRCW0805100RFKEAHP"))
    )
    (comp (ref "R14")
      (value "10K")
      (footprint "ERJ-P06F1002V")
      (description "RES 10K OHM 1% 1/2W 0805")
      (fields
        (field (name "MANUFACTURER") "Panasonic")
        (field (name "MANUFACTURER PART NUMBER") "ERJ-P06F1002V")
      )
      (libsource (lib "RG_Projects") (part "ERJ-P06F1002V"))
    )
    (comp (ref "R15")
      (value "100")
      (footprint "All_N_Cube3_Components:CRCW0805100RFKEAHP")
      (description "RES 100 OHM 1% 1/2W 0805")
      (fields
        (field (name "MANUFACTURER") "Vishay Dale")
        (field (name "MANUFACTURER PART NUMBER") "CRCW0805100RFKEAHP")
      )
      (libsource (lib "All_N_Cube3_Components") (part "CRCW0805100RFKEAHP"))
    )
    (comp (ref "R16")
      (value "100K")
      (footprint "CRCW0805100KFKEAHP")
      (description "RES 100K OHM 1% 1/2W 0805")
      (fields
        (field (name "MANUFACTURER") "Vishay")
        (field (name "MANUFACTURER PART NUMBER") "CRCW0805100KFKEAHP")
      )
      (libsource (lib "All_N_Cube3_Components") (part "CRCW0805100KFKEAHP"))
    )
    (comp (ref "R17")
      (value "0")
      (footprint "CRCW08050000Z0EAHP")
      (description "RES 0 OHM JUMPER 1/2W 0805")
      (fields
        (field (name "MANUFACTURER") "Vishay Dale")
        (field (name "MANUFACTURER PART NUMBER") "CRCW08050000Z0EAHP")
      )
      (libsource (lib "All_N_Cube3_Components") (part "CRCW08050000Z0EAHP"))
    )
    (comp (ref "R18")
      (value "2K")
      (footprint "CRCW08052K00FKEAHP")
      (description "RES 2K OHM 1% 1/2W 0805")
      (fields
        (field (name "MANUFACTURER") "Vishay Dale")
        (field (name "MANUFACTURER PART NUMBER") "CRCW08052K00FKEAHP")
      )
      (libsource (lib "All_N_Cube3_Components") (part "CRCW08052K00FKEAHP"))
    )
    (comp (ref "R19")
      (value "1.07K")
      (footprint "ERJ-P06F1071V")
      (description "RES 1.07 KOHM 1% 1/2W 0805")
      (fields
        (field (name "MANUFACTURER") "Panasonic")
        (field (name "MANUFACTURER PART NUMBER") "ERJP06F1071V")
      )
      (libsource (lib "All_N_Cube3_Components") (part "ERJ-P06F1071V"))
    )
    (comp (ref "R20")
      (value "1K")
      (footprint "CRCW08051K00FKEAHP")
      (description "RES 1K OHM 1% 1/2W 0805")
      (fields
        (field (name "MANUFACTURER") "Vishay Dale")
        (field (name "MANUFACTURER PART NUMBER") "CRCW08051K00FKEAHP")
      )
      (libsource (lib "RG_Projects") (part "CRCW08051K00FKEAHP"))
    )
    (comp (ref "R21")
      (value "1K")
      (footprint "CRCW08051K00FKEAHP")
      (description "RES 1K OHM 1% 1/2W 0805")
      (fields
        (field (name "MANUFACTURER") "Vishay Dale")
        (field (name "MANUFACTURER PART NUMBER") "CRCW08051K00FKEAHP")
      )
      (libsource (lib "RG_Projects") (part "CRCW08051K00FKEAHP"))
    )
    (comp (ref "R22")
      (value "1K")
      (footprint "CRCW08051K00FKEAHP")
      (description "RES 1K OHM 1% 1/2W 0805")
      (fields
        (field (name "MANUFACTURER") "Vishay Dale")
        (field (name "MANUFACTURER PART NUMBER") "CRCW08051K00FKEAHP")
      )
      (libsource (lib "RG_Projects") (part "CRCW08051K00FKEAHP"))
    )
    (comp (ref "R23")
      (value "100K")
      (footprint "CRCW0805100KFKEAHP")
      (description "RES 100K OHM 1% 1/2W 0805")
      (fields
        (field (name "MANUFACTURER") "Vishay")
        (field (name "MANUFACTURER PART NUMBER") "CRCW0805100KFKEAHP")
      )
      (libsource (lib "All_N_Cube3_Components") (part "CRCW0805100KFKEAHP"))
    )
    (comp (ref "R24")
      (value "100K")
      (footprint "CRCW0805100KFKEAHP")
      (description "RES 100K OHM 1% 1/2W 0805")
      (fields
        (field (name "MANUFACTURER") "Vishay")
        (field (name "MANUFACTURER PART NUMBER") "CRCW0805100KFKEAHP")
      )
      (libsource (lib "All_N_Cube3_Components") (part "CRCW0805100KFKEAHP"))
    )
    (comp (ref "R25")
      (value "100K")
      (footprint "CRCW0805100KFKEAHP")
      (description "RES 100K OHM 1% 1/2W 0805")
      (fields
        (field (name "MANUFACTURER") "Vishay")
        (field (name "MANUFACTURER PART NUMBER") "CRCW0805100KFKEAHP")
      )
      (libsource (lib "All_N_Cube3_Components") (part "CRCW0805100KFKEAHP"))
    )
    (comp (ref "R26")
      (value "100K")
      (footprint "CRCW0805100KFKEAHP")
      (description "RES 100K OHM 1% 1/2W 0805")
      (fields
        (field (name "MANUFACTURER") "Vishay")
        (field (name "MANUFACTURER PART NUMBER") "CRCW0805100KFKEAHP")
      )
      (libsource (lib "All_N_Cube3_Components") (part "CRCW0805100KFKEAHP"))
    )
    (comp (ref "R27")
      (value "1K")
      (footprint "CRCW08051K00FKEAHP")
      (description "RES 1K OHM 1% 1/2W 0805")
      (fields
        (field (name "MANUFACTURER") "Vishay Dale")
        (field (name "MANUFACTURER PART NUMBER") "CRCW08051K00FKEAHP")
      )
      (libsource (lib "RG_Projects") (part "CRCW08051K00FKEAHP"))
    )
    (comp (ref "R28")
      (value "1K")
      (footprint "CRCW08051K00FKEAHP")
      (description "RES 1K OHM 1% 1/2W 0805")
      (fields
        (field (name "MANUFACTURER") "Vishay Dale")
        (field (name "MANUFACTURER PART NUMBER") "CRCW08051K00FKEAHP")
      )
      (libsource (lib "RG_Projects") (part "CRCW08051K00FKEAHP"))
    )
    (comp (ref "R29")
      (value "1K")
      (footprint "CRCW08051K00FKEAHP")
      (description "RES 1K OHM 1% 1/2W 0805")
      (fields
        (field (name "MANUFACTURER") "Vishay Dale")
        (field (name "MANUFACTURER PART NUMBER") "CRCW08051K00FKEAHP")
      )
      (libsource (lib "RG_Projects") (part "CRCW08051K00FKEAHP"))
    )
    (comp (ref "R30")
      (value "1K")
      (footprint "CRCW08051K00FKEAHP")
      (description "RES 1K OHM 1% 1/2W 0805")
      (fields
        (field (name "MANUFACTURER") "Vishay Dale")
        (field (name "MANUFACTURER PART NUMBER") "CRCW08051K00FKEAHP")
      )
      (libsource (lib "RG_Projects") (part "CRCW08051K00FKEAHP"))
    )
    (comp (ref "R31")
      (value "10K")
      (footprint "ERJ-P06F1002V")
      (description "RES 10K OHM 1% 1/2W 0805")
      (fields
        (field (name "MANUFACTURER") "Panasonic")
        (field (name "MANUFACTURER PART NUMBER") "ERJ-P06F1002V")
      )
      (libsource (lib "RG_Projects") (part "ERJ-P06F1002V"))
    )
    (comp (ref "R32")
      (value "4.7K")
      (footprint "All_N_Cube3_Components:ERJ-P06F4701V")
      (description "RES 4.7K OHM 1% 1/2W 0805")
      (fields
        (field (name "MANUFACTURER") "Panasonic Electronic Components")
        (field (name "MANUFACTURER PART NUMBER") "ERJ-P06F4701V")
      )
      (libsource (lib "All_N_Cube3_Components") (part "ERJ-P06F4701V"))
    )
    (comp (ref "R33")
      (value "1K")
      (footprint "CRCW08051K00FKEAHP")
      (description "RES 1K OHM 1% 1/2W 0805")
      (fields
        (field (name "MANUFACTURER") "Vishay Dale")
        (field (name "MANUFACTURER PART NUMBER") "CRCW08051K00FKEAHP")
      )
      (libsource (lib "RG_Projects") (part "CRCW08051K00FKEAHP"))
    )
    (comp (ref "R34")
      (value "4.7K")
      (footprint "All_N_Cube3_Components:ERJ-P06F4701V")
      (description "RES 4.7K OHM 1% 1/2W 0805")
      (fields
        (field (name "MANUFACTURER") "Panasonic Electronic Components")
        (field (name "MANUFACTURER PART NUMBER") "ERJ-P06F4701V")
      )
      (libsource (lib "All_N_Cube3_Components") (part "ERJ-P06F4701V"))
    )
    (comp (ref "R35")
      (value "1K")
      (footprint "CRCW08051K00FKEAHP")
      (description "RES 1K OHM 1% 1/2W 0805")
      (fields
        (field (name "MANUFACTURER") "Vishay Dale")
        (field (name "MANUFACTURER PART NUMBER") "CRCW08051K00FKEAHP")
      )
      (libsource (lib "RG_Projects") (part "CRCW08051K00FKEAHP"))
    )
    (comp (ref "R36")
      (value "100K")
      (footprint "CRCW0805100KFKEAHP")
      (description "RES 100K OHM 1% 1/2W 0805")
      (fields
        (field (name "MANUFACTURER") "Vishay")
        (field (name "MANUFACTURER PART NUMBER") "CRCW0805100KFKEAHP")
      )
      (libsource (lib "All_N_Cube3_Components") (part "CRCW0805100KFKEAHP"))
    )
    (comp (ref "R37")
      (value "10K")
      (footprint "ERJ-P06F1002V")
      (description "RES 10K OHM 1% 1/2W 0805")
      (fields
        (field (name "MANUFACTURER") "Panasonic")
        (field (name "MANUFACTURER PART NUMBER") "ERJ-P06F1002V")
      )
      (libsource (lib "RG_Projects") (part "ERJ-P06F1002V"))
    )
    (comp (ref "R38")
      (value "100K")
      (footprint "CRCW0805100KFKEAHP")
      (description "RES 100K OHM 1% 1/2W 0805")
      (fields
        (field (name "MANUFACTURER") "Vishay")
        (field (name "MANUFACTURER PART NUMBER") "CRCW0805100KFKEAHP")
      )
      (libsource (lib "All_N_Cube3_Components") (part "CRCW0805100KFKEAHP"))
    )
    (comp (ref "R39")
      (value "100K")
      (footprint "CRCW0805100KFKEAHP")
      (description "RES 100K OHM 1% 1/2W 0805")
      (fields
        (field (name "MANUFACTURER") "Vishay")
        (field (name "MANUFACTURER PART NUMBER") "CRCW0805100KFKEAHP")
      )
      (libsource (lib "All_N_Cube3_Components") (part "CRCW0805100KFKEAHP"))
    )
    (comp (ref "R40")
      (value "1K")
      (footprint "CRCW08051K00FKEAHP")
      (description "RES 1K OHM 1% 1/2W 0805")
      (fields
        (field (name "MANUFACTURER") "Vishay Dale")
        (field (name "MANUFACTURER PART NUMBER") "CRCW08051K00FKEAHP")
      )
      (libsource (lib "RG_Projects") (part "CRCW08051K00FKEAHP"))
    )
    (comp (ref "R41")
      (value "0")
      (footprint "HCJ0805ZT0R00")
      (description "RES SMD 0 OHM JUMPER 0805")
      (fields
        (field (name "MANUFACTURER") "Stackpole Electronics Inc.")
        (field (name "MANUFACTURER PART NUMBER") "HCJ0805ZT0R00")
      )
      (libsource (lib "All_ESK_Components") (part "HCJ0805ZT0R00"))
    )
    (comp (ref "R42")
      (value "0")
      (footprint "HCJ0805ZT0R00")
      (description "RES SMD 0 OHM JUMPER 0805")
      (fields
        (field (name "MANUFACTURER") "Stackpole Electronics Inc.")
        (field (name "MANUFACTURER PART NUMBER") "HCJ0805ZT0R00")
      )
      (libsource (lib "All_ESK_Components") (part "HCJ0805ZT0R00"))
    )
    (comp (ref "R43")
      (value "10K")
      (footprint "ERJ-P06F1002V")
      (description "RES 10K OHM 1% 1/2W 0805")
      (fields
        (field (name "MANUFACTURER") "Panasonic")
        (field (name "MANUFACTURER PART NUMBER") "ERJ-P06F1002V")
      )
      (libsource (lib "RG_Projects") (part "ERJ-P06F1002V"))
    )
    (comp (ref "R44")
      (value "10K")
      (footprint "ERJ-P06F1002V")
      (description "RES 10K OHM 1% 1/2W 0805")
      (fields
        (field (name "MANUFACTURER") "Panasonic")
        (field (name "MANUFACTURER PART NUMBER") "ERJ-P06F1002V")
      )
      (libsource (lib "RG_Projects") (part "ERJ-P06F1002V"))
    )
    (comp (ref "R45")
      (value "100K")
      (footprint "CRCW0805100KFKEAHP")
      (description "RES 100K OHM 1% 1/2W 0805")
      (fields
        (field (name "MANUFACTURER") "Vishay")
        (field (name "MANUFACTURER PART NUMBER") "CRCW0805100KFKEAHP")
      )
      (libsource (lib "All_N_Cube3_Components") (part "CRCW0805100KFKEAHP"))
    )
    (comp (ref "R46")
      (value "100K")
      (footprint "CRCW0805100KFKEAHP")
      (description "RES 100K OHM 1% 1/2W 0805")
      (fields
        (field (name "MANUFACTURER") "Vishay")
        (field (name "MANUFACTURER PART NUMBER") "CRCW0805100KFKEAHP")
      )
      (libsource (lib "All_N_Cube3_Components") (part "CRCW0805100KFKEAHP"))
    )
    (comp (ref "R47")
      (value "4.7K")
      (footprint "All_N_Cube3_Components:ERJ-P06F4701V")
      (description "RES 4.7K OHM 1% 1/2W 0805")
      (fields
        (field (name "MANUFACTURER") "Panasonic Electronic Components")
        (field (name "MANUFACTURER PART NUMBER") "ERJ-P06F4701V")
      )
      (libsource (lib "All_N_Cube3_Components") (part "ERJ-P06F4701V"))
    )
    (comp (ref "R49")
      (value "1K")
      (footprint "CRCW08051K00FKEAHP")
      (description "RES 1K OHM 1% 1/2W 0805")
      (fields
        (field (name "MANUFACTURER") "Vishay Dale")
        (field (name "MANUFACTURER PART NUMBER") "CRCW08051K00FKEAHP")
      )
      (libsource (lib "RG_Projects") (part "CRCW08051K00FKEAHP"))
    )
    (comp (ref "R50")
      (value "1K")
      (footprint "CRCW08051K00FKEAHP")
      (description "RES 1K OHM 1% 1/2W 0805")
      (fields
        (field (name "MANUFACTURER") "Vishay Dale")
        (field (name "MANUFACTURER PART NUMBER") "CRCW08051K00FKEAHP")
      )
      (libsource (lib "RG_Projects") (part "CRCW08051K00FKEAHP"))
    )
    (comp (ref "R51")
      (value "27K")
      (footprint "ERJ-P6WF2702V")
      (description "RES 27K OHM 1% 1/2W 0805")
      (fields
        (field (name "MANUFACTURER") "Panasonic Electronic Components")
        (field (name "MANUFACTURER PART NUMBER") "ERJ-P6WF2702V")
      )
      (libsource (lib "All_N_Cube3_Components") (part "ERJ-P6WF2702V"))
    )
    (comp (ref "R52")
      (value "27K")
      (footprint "ERJ-P6WF2702V")
      (description "RES 27K OHM 1% 1/2W 0805")
      (fields
        (field (name "MANUFACTURER") "Panasonic Electronic Components")
        (field (name "MANUFACTURER PART NUMBER") "ERJ-P6WF2702V")
      )
      (libsource (lib "All_N_Cube3_Components") (part "ERJ-P6WF2702V"))
    )
    (comp (ref "R53")
      (value "1K")
      (footprint "CRCW08051K00FKEAHP")
      (description "RES 1K OHM 1% 1/2W 0805")
      (fields
        (field (name "MANUFACTURER") "Vishay Dale")
        (field (name "MANUFACTURER PART NUMBER") "CRCW08051K00FKEAHP")
      )
      (libsource (lib "RG_Projects") (part "CRCW08051K00FKEAHP"))
    )
    (comp (ref "R54")
      (value "1K")
      (footprint "CRCW08051K00FKEAHP")
      (description "RES 1K OHM 1% 1/2W 0805")
      (fields
        (field (name "MANUFACTURER") "Vishay Dale")
        (field (name "MANUFACTURER PART NUMBER") "CRCW08051K00FKEAHP")
      )
      (libsource (lib "RG_Projects") (part "CRCW08051K00FKEAHP"))
    )
    (comp (ref "R55")
      (value "0.04ohm")
      (footprint "All_N_Cube3_Components:RL3720WT-R040-G")
      (description "RES 0.04 OHM 1W 1508 WIDE")
      (fields
        (field (name "MANUFACTURER") "Susumu")
        (field (name "MANUFACTURER PART NUMBER") "RL3720WT-R040-G")
      )
      (libsource (lib "All_N_Cube3_Components") (part "RL3720WT-R040-G"))
    )
    (comp (ref "R56")
      (value "0.04ohm")
      (footprint "All_N_Cube3_Components:RL3720WT-R040-G")
      (description "RES 0.04 OHM 1W 1508 WIDE")
      (fields
        (field (name "MANUFACTURER") "Susumu")
        (field (name "MANUFACTURER PART NUMBER") "RL3720WT-R040-G")
      )
      (libsource (lib "All_N_Cube3_Components") (part "RL3720WT-R040-G"))
    )
    (comp (ref "R57")
      (value "0.04ohm")
      (footprint "RG_Projects:RL3720WT-R040-G")
      (description "RES 0.04 OHM 1W 1508 WIDE")
      (fields
        (field (name "MANUFACTURER") "Susumu")
        (field (name "MANUFACTURER PART NUMBER") "RL3720WT-R040-G")
      )
      (libsource (lib "All_N_Cube3_Components") (part "RL3720WT-R040-G"))
    )
    (comp (ref "R58")
      (value "0.04ohm")
      (footprint "RG_Projects:RL3720WT-R040-G")
      (description "RES 0.04 OHM 1W 1508 WIDE")
      (fields
        (field (name "MANUFACTURER") "Susumu")
        (field (name "MANUFACTURER PART NUMBER") "RL3720WT-R040-G")
      )
      (libsource (lib "All_N_Cube3_Components") (part "RL3720WT-R040-G"))
    )
    (comp (ref "R59")
      (value "0.04ohm")
      (footprint "All_N_Cube3_Components:RL3720WT-R040-G")
      (description "RES 0.04 OHM 1W 1508 WIDE")
      (fields
        (field (name "MANUFACTURER") "Susumu")
        (field (name "MANUFACTURER PART NUMBER") "RL3720WT-R040-G")
      )
      (libsource (lib "All_N_Cube3_Components") (part "RL3720WT-R040-G"))
    )
    (comp (ref "R60")
      (value "3.4K")
      (footprint "ERJ-P06F3401V")
      (description "RES 3.4 KOHM 1% 1/2W 0805")
      (fields
        (field (name "MANUFACTURER") "Panasonic")
        (field (name "MANUFACTURER PART NUMBER") "ERJP06F3401V")
      )
      (libsource (lib "All_N_Cube3_Components") (part "ERJ-P06F3401V"))
    )
    (comp (ref "R61")
      (value "0.04ohm")
      (footprint "All_N_Cube3_Components:RL3720WT-R040-G")
      (description "RES 0.04 OHM 1W 1508 WIDE")
      (fields
        (field (name "MANUFACTURER") "Susumu")
        (field (name "MANUFACTURER PART NUMBER") "RL3720WT-R040-G")
      )
      (libsource (lib "All_N_Cube3_Components") (part "RL3720WT-R040-G"))
    )
    (comp (ref "R62")
      (value "0.04ohm")
      (footprint "All_N_Cube3_Components:RL3720WT-R040-G")
      (description "RES 0.04 OHM 1W 1508 WIDE")
      (fields
        (field (name "MANUFACTURER") "Susumu")
        (field (name "MANUFACTURER PART NUMBER") "RL3720WT-R040-G")
      )
      (libsource (lib "All_N_Cube3_Components") (part "RL3720WT-R040-G"))
    )
    (comp (ref "R63")
      (value "0.04ohm")
      (footprint "All_N_Cube3_Components:RL3720WT-R040-G")
      (description "RES 0.04 OHM 1W 1508 WIDE")
      (fields
        (field (name "MANUFACTURER") "Susumu")
        (field (name "MANUFACTURER PART NUMBER") "RL3720WT-R040-G")
      )
      (libsource (lib "All_N_Cube3_Components") (part "RL3720WT-R040-G"))
    )
    (comp (ref "R64")
      (value "20K")
      (footprint "CRCW080520K0FKEAHP")
      (description "RES 20K OHM 1% 1/2W 0805")
      (fields
        (field (name "MANUFACTURER") "Vishay Dale")
        (field (name "MANUFACTURER PART NUMBER") "CRCW080520K0FKEAHP")
      )
      (libsource (lib "All_N_Cube3_Components") (part "CRCW080520K0FKEAHP"))
    )
    (comp (ref "R65")
      (value "10K")
      (footprint "ERJ-P06F1002V")
      (description "RES 10K OHM 1% 1/2W 0805")
      (fields
        (field (name "MANUFACTURER") "Panasonic")
        (field (name "MANUFACTURER PART NUMBER") "ERJ-P06F1002V")
      )
      (libsource (lib "RG_Projects") (part "ERJ-P06F1002V"))
    )
    (comp (ref "R66")
      (value "100")
      (footprint "All_N_Cube3_Components:CRCW0805100RFKEAHP")
      (description "RES 100 OHM 1% 1/2W 0805")
      (fields
        (field (name "MANUFACTURER") "Vishay Dale")
        (field (name "MANUFACTURER PART NUMBER") "CRCW0805100RFKEAHP")
      )
      (libsource (lib "All_N_Cube3_Components") (part "CRCW0805100RFKEAHP"))
    )
    (comp (ref "R67")
      (value "191K")
      (footprint "ERJ-P06F1913V")
      (description "RES 191K OHM 1% 1/2W 0805")
      (fields
        (field (name "MANUFACTURER") "Panasonic")
        (field (name "MANUFACTURER PART NUMBER") "ERJP06F1913V")
      )
      (libsource (lib "All_N_Cube3_Components") (part "ERJ-P06F1913V"))
    )
    (comp (ref "R68")
      (value "1.17M")
      (footprint "RT0805BRD071M17L")
      (description "RES 1.17M OHM 0.1% 1/8W 0805")
      (fields
        (field (name "MANUFACTURER") "Yageo")
        (field (name "MANUFACTURER PART NUMBER") "RT0805BRD071M17L")
      )
      (libsource (lib "All_N_Cube3_Components") (part "RT0805BRD071M17L"))
    )
    (comp (ref "R69")
      (value "100K")
      (footprint "CRCW0805100KFKEAHP")
      (description "RES 100K OHM 1% 1/2W 0805")
      (fields
        (field (name "MANUFACTURER") "Vishay")
        (field (name "MANUFACTURER PART NUMBER") "CRCW0805100KFKEAHP")
      )
      (libsource (lib "All_N_Cube3_Components") (part "CRCW0805100KFKEAHP"))
    )
    (comp (ref "R70")
      (value "10K")
      (footprint "ERJ-P06F1002V")
      (description "RES 10K OHM 1% 1/2W 0805")
      (fields
        (field (name "MANUFACTURER") "Panasonic")
        (field (name "MANUFACTURER PART NUMBER") "ERJ-P06F1002V")
      )
      (libsource (lib "RG_Projects") (part "ERJ-P06F1002V"))
    )
    (comp (ref "R71")
      (value "1.07K")
      (footprint "ERJ-P06F1071V")
      (description "RES 1.07 KOHM 1% 1/2W 0805")
      (fields
        (field (name "MANUFACTURER") "Panasonic")
        (field (name "MANUFACTURER PART NUMBER") "ERJP06F1071V")
      )
      (libsource (lib "All_N_Cube3_Components") (part "ERJ-P06F1071V"))
    )
    (comp (ref "R72")
      (value "20K")
      (footprint "CRCW080520K0FKEAHP")
      (description "RES 20K OHM 1% 1/2W 0805")
      (fields
        (field (name "MANUFACTURER") "Vishay Dale")
        (field (name "MANUFACTURER PART NUMBER") "CRCW080520K0FKEAHP")
      )
      (libsource (lib "All_N_Cube3_Components") (part "CRCW080520K0FKEAHP"))
    )
    (comp (ref "R73")
      (value "1K")
      (footprint "CRCW08051K00FKEAHP")
      (description "RES 1K OHM 1% 1/2W 0805")
      (fields
        (field (name "MANUFACTURER") "Vishay Dale")
        (field (name "MANUFACTURER PART NUMBER") "CRCW08051K00FKEAHP")
      )
      (libsource (lib "RG_Projects") (part "CRCW08051K00FKEAHP"))
    )
    (comp (ref "R74")
      (value "10K")
      (footprint "ERJ-P06F1002V")
      (description "RES 10K OHM 1% 1/2W 0805")
      (fields
        (field (name "MANUFACTURER") "Panasonic")
        (field (name "MANUFACTURER PART NUMBER") "ERJ-P06F1002V")
      )
      (libsource (lib "RG_Projects") (part "ERJ-P06F1002V"))
    )
    (comp (ref "R75")
      (value "1K")
      (footprint "CRCW08051K00FKEAHP")
      (description "RES 1K OHM 1% 1/2W 0805")
      (fields
        (field (name "MANUFACTURER") "Vishay Dale")
        (field (name "MANUFACTURER PART NUMBER") "CRCW08051K00FKEAHP")
      )
      (libsource (lib "RG_Projects") (part "CRCW08051K00FKEAHP"))
    )
    (comp (ref "R76")
      (value "0")
      (footprint "CRCW08050000Z0EAHP")
      (description "RES 0 OHM JUMPER 1/2W 0805")
      (fields
        (field (name "MANUFACTURER") "Vishay Dale")
        (field (name "MANUFACTURER PART NUMBER") "CRCW08050000Z0EAHP")
      )
      (libsource (lib "All_N_Cube3_Components") (part "CRCW08050000Z0EAHP"))
    )
    (comp (ref "R77")
      (value "2K")
      (footprint "CRCW08052K00FKEAHP")
      (description "RES 2K OHM 1% 1/2W 0805")
      (fields
        (field (name "MANUFACTURER") "Vishay Dale")
        (field (name "MANUFACTURER PART NUMBER") "CRCW08052K00FKEAHP")
      )
      (libsource (lib "All_N_Cube3_Components") (part "CRCW08052K00FKEAHP"))
    )
    (comp (ref "R78")
      (value "4.7K")
      (footprint "All_N_Cube3_Components:ERJ-P06F4701V")
      (description "RES 4.7K OHM 1% 1/2W 0805")
      (fields
        (field (name "MANUFACTURER") "Panasonic Electronic Components")
        (field (name "MANUFACTURER PART NUMBER") "ERJ-P06F4701V")
      )
      (libsource (lib "All_N_Cube3_Components") (part "ERJ-P06F4701V"))
    )
    (comp (ref "R79")
      (value "1K")
      (footprint "CRCW08051K00FKEAHP")
      (description "RES 1K OHM 1% 1/2W 0805")
      (fields
        (field (name "MANUFACTURER") "Vishay Dale")
        (field (name "MANUFACTURER PART NUMBER") "CRCW08051K00FKEAHP")
      )
      (libsource (lib "RG_Projects") (part "CRCW08051K00FKEAHP"))
    )
    (comp (ref "R80")
      (value "1K")
      (footprint "CRCW08051K00FKEAHP")
      (description "RES 1K OHM 1% 1/2W 0805")
      (fields
        (field (name "MANUFACTURER") "Vishay Dale")
        (field (name "MANUFACTURER PART NUMBER") "CRCW08051K00FKEAHP")
      )
      (libsource (lib "RG_Projects") (part "CRCW08051K00FKEAHP"))
    )
    (comp (ref "R81")
      (value "1K")
      (footprint "CRCW08051K00FKEAHP")
      (description "RES 1K OHM 1% 1/2W 0805")
      (fields
        (field (name "MANUFACTURER") "Vishay Dale")
        (field (name "MANUFACTURER PART NUMBER") "CRCW08051K00FKEAHP")
      )
      (libsource (lib "RG_Projects") (part "CRCW08051K00FKEAHP"))
    )
    (comp (ref "R82")
      (value "10K")
      (footprint "ERJ-P06F1002V")
      (description "RES 10K OHM 1% 1/2W 0805")
      (fields
        (field (name "MANUFACTURER") "Panasonic")
        (field (name "MANUFACTURER PART NUMBER") "ERJ-P06F1002V")
      )
      (libsource (lib "RG_Projects") (part "ERJ-P06F1002V"))
    )
    (comp (ref "R83")
      (value "100K")
      (footprint "CRCW0805100KFKEAHP")
      (description "RES 100K OHM 1% 1/2W 0805")
      (fields
        (field (name "MANUFACTURER") "Vishay")
        (field (name "MANUFACTURER PART NUMBER") "CRCW0805100KFKEAHP")
      )
      (libsource (lib "All_N_Cube3_Components") (part "CRCW0805100KFKEAHP"))
    )
    (comp (ref "R84")
      (value "10K")
      (footprint "ERJ-P06F1002V")
      (description "RES 10K OHM 1% 1/2W 0805")
      (fields
        (field (name "MANUFACTURER") "Panasonic")
        (field (name "MANUFACTURER PART NUMBER") "ERJ-P06F1002V")
      )
      (libsource (lib "RG_Projects") (part "ERJ-P06F1002V"))
    )
    (comp (ref "R85")
      (value "4.7K")
      (footprint "All_N_Cube3_Components:ERJ-P06F4701V")
      (description "RES 4.7K OHM 1% 1/2W 0805")
      (fields
        (field (name "MANUFACTURER") "Panasonic Electronic Components")
        (field (name "MANUFACTURER PART NUMBER") "ERJ-P06F4701V")
      )
      (libsource (lib "All_N_Cube3_Components") (part "ERJ-P06F4701V"))
    )
    (comp (ref "R86")
      (value "4.7K")
      (footprint "All_N_Cube3_Components:ERJ-P06F4701V")
      (description "RES 4.7K OHM 1% 1/2W 0805")
      (fields
        (field (name "MANUFACTURER") "Panasonic Electronic Components")
        (field (name "MANUFACTURER PART NUMBER") "ERJ-P06F4701V")
      )
      (libsource (lib "All_N_Cube3_Components") (part "ERJ-P06F4701V"))
    )
    (comp (ref "R87")
      (value "0.04ohm")
      (footprint "All_N_Cube3_Components:RL3720WT-R040-G")
      (description "RES 0.04 OHM 1W 1508 WIDE")
      (fields
        (field (name "MANUFACTURER") "Susumu")
        (field (name "MANUFACTURER PART NUMBER") "RL3720WT-R040-G")
      )
      (libsource (lib "All_N_Cube3_Components") (part "RL3720WT-R040-G"))
    )
    (comp (ref "R88")
      (value "0.04ohm")
      (footprint "All_N_Cube3_Components:RL3720WT-R040-G")
      (description "RES 0.04 OHM 1W 1508 WIDE")
      (fields
        (field (name "MANUFACTURER") "Susumu")
        (field (name "MANUFACTURER PART NUMBER") "RL3720WT-R040-G")
      )
      (libsource (lib "All_N_Cube3_Components") (part "RL3720WT-R040-G"))
    )
    (comp (ref "R89")
      (value "0.04ohm")
      (footprint "All_N_Cube3_Components:RL3720WT-R040-G")
      (description "RES 0.04 OHM 1W 1508 WIDE")
      (fields
        (field (name "MANUFACTURER") "Susumu")
        (field (name "MANUFACTURER PART NUMBER") "RL3720WT-R040-G")
      )
      (libsource (lib "All_N_Cube3_Components") (part "RL3720WT-R040-G"))
    )
    (comp (ref "R90")
      (value "0.04ohm")
      (footprint "All_N_Cube3_Components:RL3720WT-R040-G")
      (description "RES 0.04 OHM 1W 1508 WIDE")
      (fields
        (field (name "MANUFACTURER") "Susumu")
        (field (name "MANUFACTURER PART NUMBER") "RL3720WT-R040-G")
      )
      (libsource (lib "All_N_Cube3_Components") (part "RL3720WT-R040-G"))
    )
    (comp (ref "R91")
      (value "0.04ohm")
      (footprint "All_N_Cube3_Components:RL3720WT-R040-G")
      (description "RES 0.04 OHM 1W 1508 WIDE")
      (fields
        (field (name "MANUFACTURER") "Susumu")
        (field (name "MANUFACTURER PART NUMBER") "RL3720WT-R040-G")
      )
      (libsource (lib "All_N_Cube3_Components") (part "RL3720WT-R040-G"))
    )
    (comp (ref "R92")
      (value "0.04ohm")
      (footprint "All_N_Cube3_Components:RL3720WT-R040-G")
      (description "RES 0.04 OHM 1W 1508 WIDE")
      (fields
        (field (name "MANUFACTURER") "Susumu")
        (field (name "MANUFACTURER PART NUMBER") "RL3720WT-R040-G")
      )
      (libsource (lib "All_N_Cube3_Components") (part "RL3720WT-R040-G"))
    )
    (comp (ref "R93")
      (value "1K")
      (footprint "CRCW08051K00FKEAHP")
      (description "RES 1K OHM 1% 1/2W 0805")
      (fields
        (field (name "MANUFACTURER") "Vishay Dale")
        (field (name "MANUFACTURER PART NUMBER") "CRCW08051K00FKEAHP")
      )
      (libsource (lib "RG_Projects") (part "CRCW08051K00FKEAHP"))
    )
    (comp (ref "R94")
      (value "0.04ohm")
      (footprint "All_N_Cube3_Components:RL3720WT-R040-G")
      (description "RES 0.04 OHM 1W 1508 WIDE")
      (fields
        (field (name "MANUFACTURER") "Susumu")
        (field (name "MANUFACTURER PART NUMBER") "RL3720WT-R040-G")
      )
      (libsource (lib "All_N_Cube3_Components") (part "RL3720WT-R040-G"))
    )
    (comp (ref "R95")
      (value "5.62K")
      (footprint "CRCW08055K62FKEAHP")
      (description "RES 5.62K OHM 1% 1/2W 0805")
      (fields
        (field (name "MANUFACTURER") "Vishay Dale")
        (field (name "MANUFACTURER PART NUMBER") "CRCW08055K62FKEAHP")
      )
      (libsource (lib "All_N_Cube3_Components") (part "CRCW08055K62FKEAHP"))
    )
    (comp (ref "R96")
      (value "0.04ohm")
      (footprint "All_N_Cube3_Components:RL3720WT-R040-G")
      (description "RES 0.04 OHM 1W 1508 WIDE")
      (fields
        (field (name "MANUFACTURER") "Susumu")
        (field (name "MANUFACTURER PART NUMBER") "RL3720WT-R040-G")
      )
      (libsource (lib "All_N_Cube3_Components") (part "RL3720WT-R040-G"))
    )
    (comp (ref "R97")
      (value "0.04ohm")
      (footprint "All_N_Cube3_Components:RL3720WT-R040-G")
      (description "RES 0.04 OHM 1W 1508 WIDE")
      (fields
        (field (name "MANUFACTURER") "Susumu")
        (field (name "MANUFACTURER PART NUMBER") "RL3720WT-R040-G")
      )
      (libsource (lib "All_N_Cube3_Components") (part "RL3720WT-R040-G"))
    )
    (comp (ref "R98")
      (value "0.04ohm")
      (footprint "All_N_Cube3_Components:RL3720WT-R040-G")
      (description "RES 0.04 OHM 1W 1508 WIDE")
      (fields
        (field (name "MANUFACTURER") "Susumu")
        (field (name "MANUFACTURER PART NUMBER") "RL3720WT-R040-G")
      )
      (libsource (lib "All_N_Cube3_Components") (part "RL3720WT-R040-G"))
    )
    (comp (ref "R99")
      (value "10K")
      (footprint "ERJ-P06F1002V")
      (description "RES 10K OHM 1% 1/2W 0805")
      (fields
        (field (name "MANUFACTURER") "Panasonic")
        (field (name "MANUFACTURER PART NUMBER") "ERJ-P06F1002V")
      )
      (libsource (lib "RG_Projects") (part "ERJ-P06F1002V"))
    )
    (comp (ref "R100")
      (value "100")
      (footprint "All_N_Cube3_Components:CRCW0805100RFKEAHP")
      (description "RES 100 OHM 1% 1/2W 0805")
      (fields
        (field (name "MANUFACTURER") "Vishay Dale")
        (field (name "MANUFACTURER PART NUMBER") "CRCW0805100RFKEAHP")
      )
      (libsource (lib "All_N_Cube3_Components") (part "CRCW0805100RFKEAHP"))
    )
    (comp (ref "R101")
      (value "1.07K")
      (footprint "ERJ-P06F1071V")
      (description "RES 1.07 KOHM 1% 1/2W 0805")
      (fields
        (field (name "MANUFACTURER") "Panasonic")
        (field (name "MANUFACTURER PART NUMBER") "ERJP06F1071V")
      )
      (libsource (lib "All_N_Cube3_Components") (part "ERJ-P06F1071V"))
    )
    (comp (ref "R102")
      (value "1K")
      (footprint "CRCW08051K00FKEAHP")
      (description "RES 1K OHM 1% 1/2W 0805")
      (fields
        (field (name "MANUFACTURER") "Vishay Dale")
        (field (name "MANUFACTURER PART NUMBER") "CRCW08051K00FKEAHP")
      )
      (libsource (lib "RG_Projects") (part "CRCW08051K00FKEAHP"))
    )
    (comp (ref "R103")
      (value "470K")
      (footprint "CRCW0805470KFKEAHP")
      (description "RES 470K OHM 1% 1/2W 0805")
      (fields
        (field (name "MANUFACTURER") "Vishay Dale")
        (field (name "MANUFACTURER PART NUMBER") "CRCW0805470KFKEAHP")
      )
      (libsource (lib "All_N_Cube3_Components") (part "CRCW0805470KFKEAHP"))
    )
    (comp (ref "R104")
      (value "10K")
      (footprint "ERJ-P06F1002V")
      (description "RES 10K OHM 1% 1/2W 0805")
      (fields
        (field (name "MANUFACTURER") "Panasonic")
        (field (name "MANUFACTURER PART NUMBER") "ERJ-P06F1002V")
      )
      (libsource (lib "RG_Projects") (part "ERJ-P06F1002V"))
    )
    (comp (ref "R105")
      (value "4.7K")
      (footprint "All_N_Cube3_Components:ERJ-P06F4701V")
      (description "RES 4.7K OHM 1% 1/2W 0805")
      (fields
        (field (name "MANUFACTURER") "Panasonic Electronic Components")
        (field (name "MANUFACTURER PART NUMBER") "ERJ-P06F4701V")
      )
      (libsource (lib "All_N_Cube3_Components") (part "ERJ-P06F4701V"))
    )
    (comp (ref "R106")
      (value "1K")
      (footprint "CRCW08051K00FKEAHP")
      (description "RES 1K OHM 1% 1/2W 0805")
      (fields
        (field (name "MANUFACTURER") "Vishay Dale")
        (field (name "MANUFACTURER PART NUMBER") "CRCW08051K00FKEAHP")
      )
      (libsource (lib "RG_Projects") (part "CRCW08051K00FKEAHP"))
    )
    (comp (ref "R107")
      (value "12.4K")
      (footprint "CRCW080512K4FKEAHP")
      (description "RES SMD 12.4K OHM 1% 1/2W 0805")
      (fields
        (field (name "MANUFACTURER") "Vishay Dale")
        (field (name "MANUFACTURER PART NUMBER") "CRCW080512K4FKEAHP")
      )
      (libsource (lib "All_N_Cube3_Components") (part "CRCW080512K4FKEAHP"))
    )
    (comp (ref "R108")
      (value "1M")
      (footprint "CRCW08051M00FKEAHP")
      (description "RES 1M OHM 1% 1/2W 0805")
      (fields
        (field (name "MANUFACTURER") "Vishay Dale")
        (field (name "MANUFACTURER PART NUMBER") "CRCW08051M00FKEAHP")
      )
      (libsource (lib "All_N_Cube3_Components") (part "CRCW08051M00FKEAHP"))
    )
    (comp (ref "R109")
      (value "1K")
      (footprint "CRCW08051K00FKEAHP")
      (description "RES 1K OHM 1% 1/2W 0805")
      (fields
        (field (name "MANUFACTURER") "Vishay Dale")
        (field (name "MANUFACTURER PART NUMBER") "CRCW08051K00FKEAHP")
      )
      (libsource (lib "RG_Projects") (part "CRCW08051K00FKEAHP"))
    )
    (comp (ref "R110")
      (value "1K")
      (footprint "CRCW08051K00FKEAHP")
      (description "RES 1K OHM 1% 1/2W 0805")
      (fields
        (field (name "MANUFACTURER") "Vishay Dale")
        (field (name "MANUFACTURER PART NUMBER") "CRCW08051K00FKEAHP")
      )
      (libsource (lib "RG_Projects") (part "CRCW08051K00FKEAHP"))
    )
    (comp (ref "R111")
      (value "510K")
      (footprint "CRCW0805510KFKEAHP")
      (description "RES 510K OHM 1% 1/2W 0805")
      (fields
        (field (name "MANUFACTURER") "Vishay Dale")
        (field (name "MANUFACTURER PART NUMBER") "CRCW0805510KFKEAHP")
      )
      (libsource (lib "All_N_Cube3_Components") (part "CRCW0805510KFKEAHP"))
    )
    (comp (ref "R112")
      (value "78.7K")
      (footprint "ERJ-P06F7872V")
      (description "RES 78.7 KOHM 1% 1/2W 0805")
      (fields
        (field (name "MANUFACTURER") "Panasonic")
        (field (name "MANUFACTURER PART NUMBER") "ERJ-P06F7872V")
      )
      (libsource (lib "All_N_Cube3_Components") (part "ERJ-P06F7872V"))
    )
    (comp (ref "R113")
      (value "9.09K")
      (footprint "CRCW08059K09FKEAHP")
      (description "RES 9.09K OHM 1% 1/2W 0805")
      (fields
        (field (name "MANUFACTURER") "Vishay Dale")
        (field (name "MANUFACTURER PART NUMBER") "CRCW08059K09FKEAHP")
      )
      (libsource (lib "All_N_Cube3_Components") (part "CRCW08059K09FKEAHP"))
    )
    (comp (ref "R114")
      (value "4.7K")
      (footprint "All_N_Cube3_Components:ERJ-P06F4701V")
      (description "RES 4.7K OHM 1% 1/2W 0805")
      (fields
        (field (name "MANUFACTURER") "Panasonic Electronic Components")
        (field (name "MANUFACTURER PART NUMBER") "ERJ-P06F4701V")
      )
      (libsource (lib "All_N_Cube3_Components") (part "ERJ-P06F4701V"))
    )
    (comp (ref "R115")
      (value "4.7K")
      (footprint "All_N_Cube3_Components:ERJ-P06F4701V")
      (description "RES 4.7K OHM 1% 1/2W 0805")
      (fields
        (field (name "MANUFACTURER") "Panasonic Electronic Components")
        (field (name "MANUFACTURER PART NUMBER") "ERJ-P06F4701V")
      )
      (libsource (lib "All_N_Cube3_Components") (part "ERJ-P06F4701V"))
    )
    (comp (ref "R116")
      (value "1.6K")
      (footprint "ERJ-P06F1601V")
      (description "RES 1.6K OHM 1% 1/2W 0805")
      (fields
        (field (name "MANUFACTURER") "KEMET")
        (field (name "MANUFACTURER PART NUMBER") "C0805C472K4RAC7800")
      )
      (libsource (lib "All_N_Cube3_Components") (part "ERJ-P06F1601V"))
    )
    (comp (ref "R117")
      (value "105K")
      (footprint "ERJ-P06F1053V")
      (description "RES 105 KOHM 1% 1/2W 0805")
      (fields
        (field (name "MANUFACTURER") "Panasonic")
        (field (name "MANUFACTURER PART NUMBER") "ERJP06F1053V")
      )
      (libsource (lib "All_N_Cube3_Components") (part "ERJ-P06F1053V"))
    )
    (comp (ref "R118")
      (value "100K")
      (footprint "CRCW0805100KFKEAHP")
      (description "RES 100K OHM 1% 1/2W 0805")
      (fields
        (field (name "MANUFACTURER") "Vishay")
        (field (name "MANUFACTURER PART NUMBER") "CRCW0805100KFKEAHP")
      )
      (libsource (lib "All_N_Cube3_Components") (part "CRCW0805100KFKEAHP"))
    )
    (comp (ref "R119")
      (value "100K")
      (footprint "CRCW0805100KFKEAHP")
      (description "RES 100K OHM 1% 1/2W 0805")
      (fields
        (field (name "MANUFACTURER") "Vishay")
        (field (name "MANUFACTURER PART NUMBER") "CRCW0805100KFKEAHP")
      )
      (libsource (lib "All_N_Cube3_Components") (part "CRCW0805100KFKEAHP"))
    )
    (comp (ref "R120")
      (value "0.04ohm")
      (footprint "All_N_Cube3_Components:RL3720WT-R040-G")
      (description "RES 0.04 OHM 1W 1508 WIDE")
      (fields
        (field (name "MANUFACTURER") "Susumu")
        (field (name "MANUFACTURER PART NUMBER") "RL3720WT-R040-G")
      )
      (libsource (lib "All_N_Cube3_Components") (part "RL3720WT-R040-G"))
    )
    (comp (ref "R121")
      (value "0.04ohm")
      (footprint "All_N_Cube3_Components:RL3720WT-R040-G")
      (description "RES 0.04 OHM 1W 1508 WIDE")
      (fields
        (field (name "MANUFACTURER") "Susumu")
        (field (name "MANUFACTURER PART NUMBER") "RL3720WT-R040-G")
      )
      (libsource (lib "All_N_Cube3_Components") (part "RL3720WT-R040-G"))
    )
    (comp (ref "R122")
      (value "0.04ohm")
      (footprint "All_N_Cube3_Components:RL3720WT-R040-G")
      (description "RES 0.04 OHM 1W 1508 WIDE")
      (fields
        (field (name "MANUFACTURER") "Susumu")
        (field (name "MANUFACTURER PART NUMBER") "RL3720WT-R040-G")
      )
      (libsource (lib "All_N_Cube3_Components") (part "RL3720WT-R040-G"))
    )
    (comp (ref "R123")
      (value "0.04ohm")
      (footprint "All_N_Cube3_Components:RL3720WT-R040-G")
      (description "RES 0.04 OHM 1W 1508 WIDE")
      (fields
        (field (name "MANUFACTURER") "Susumu")
        (field (name "MANUFACTURER PART NUMBER") "RL3720WT-R040-G")
      )
      (libsource (lib "All_N_Cube3_Components") (part "RL3720WT-R040-G"))
    )
    (comp (ref "R124")
      (value "4.7K")
      (footprint "RG_Projects:ERJ-P06F4701V")
      (description "RES 4.7K OHM 1% 1/2W 0805")
      (fields
        (field (name "MANUFACTURER") "Panasonic Electronic Components")
        (field (name "MANUFACTURER PART NUMBER") "ERJ-P06F4701V")
      )
      (libsource (lib "All_N_Cube3_Components") (part "ERJ-P06F4701V"))
    )
    (comp (ref "R125")
      (value "4.7K")
      (footprint "RG_Projects:ERJ-P06F4701V")
      (description "RES 4.7K OHM 1% 1/2W 0805")
      (fields
        (field (name "MANUFACTURER") "Panasonic Electronic Components")
        (field (name "MANUFACTURER PART NUMBER") "ERJ-P06F4701V")
      )
      (libsource (lib "All_N_Cube3_Components") (part "ERJ-P06F4701V"))
    )
    (comp (ref "R126")
      (value "4.7K")
      (footprint "RG_Projects:ERJ-P06F4701V")
      (description "RES 4.7K OHM 1% 1/2W 0805")
      (fields
        (field (name "MANUFACTURER") "Panasonic Electronic Components")
        (field (name "MANUFACTURER PART NUMBER") "ERJ-P06F4701V")
      )
      (libsource (lib "All_N_Cube3_Components") (part "ERJ-P06F4701V"))
    )
    (comp (ref "R127")
      (value "1K")
      (footprint "CRCW08051K00FKEAHP")
      (description "RES 1K OHM 1% 1/2W 0805")
      (fields
        (field (name "MANUFACTURER") "Vishay Dale")
        (field (name "MANUFACTURER PART NUMBER") "CRCW08051K00FKEAHP")
      )
      (libsource (lib "RG_Projects") (part "CRCW08051K00FKEAHP"))
    )
    (comp (ref "R128")
      (value "1K")
      (footprint "CRCW08051K00FKEAHP")
      (description "RES 1K OHM 1% 1/2W 0805")
      (fields
        (field (name "MANUFACTURER") "Vishay Dale")
        (field (name "MANUFACTURER PART NUMBER") "CRCW08051K00FKEAHP")
      )
      (libsource (lib "RG_Projects") (part "CRCW08051K00FKEAHP"))
    )
    (comp (ref "R129")
      (value "4.7K")
      (footprint "All_N_Cube3_Components:ERJ-P06F4701V")
      (description "RES 4.7K OHM 1% 1/2W 0805")
      (fields
        (field (name "MANUFACTURER") "Panasonic Electronic Components")
        (field (name "MANUFACTURER PART NUMBER") "ERJ-P06F4701V")
      )
      (libsource (lib "All_N_Cube3_Components") (part "ERJ-P06F4701V"))
    )
    (comp (ref "R130")
      (value "4.7K")
      (footprint "All_N_Cube3_Components:ERJ-P06F4701V")
      (description "RES 4.7K OHM 1% 1/2W 0805")
      (fields
        (field (name "MANUFACTURER") "Panasonic Electronic Components")
        (field (name "MANUFACTURER PART NUMBER") "ERJ-P06F4701V")
      )
      (libsource (lib "All_N_Cube3_Components") (part "ERJ-P06F4701V"))
    )
    (comp (ref "RBF1")
      (value "53261-0271")
      (footprint "53261-0271")
      (description "CONN HEADER SMD R/A 2POS 1.25MM")
      (fields
        (field (name "MANUFACTURER") "Molex, LLC")
        (field (name "MANUFACTURER PART NUMBER") "0532610271")
      )
      (libsource (lib "") (part "53261-0271_1"))
    )
    (comp (ref "RBF2")
      (value "53261-0271")
      (footprint "53261-0271")
      (description "CONN HEADER SMD R/A 2POS 1.25MM")
      (fields
        (field (name "MANUFACTURER") "Molex, LLC")
        (field (name "MANUFACTURER PART NUMBER") "0532610271")
      )
      (libsource (lib "All_N_Cube3_Components") (part "53261-0271"))
    )
    (comp (ref "SSW1")
      (value "53261-0271")
      (footprint "53261-0271")
      (description "CONN HEADER SMD R/A 2POS 1.25MM")
      (fields
        (field (name "MANUFACTURER") "Molex, LLC")
        (field (name "MANUFACTURER PART NUMBER") "0532610271")
      )
      (libsource (lib "All_N_Cube3_Components") (part "53261-0271"))
    )
    (comp (ref "SSW2")
      (value "53261-0371")
      (footprint "53261-0371")
      (description "CONN HEADER SMD R/A 3POS 1.25MM")
      (fields (field (name "MANUFACTURER") "Molex"))
      (libsource (lib "All_N_Cube3_Components") (part "53261-0371"))
    )
    (comp (ref "Temp")
      (value "53261-0471")
      (footprint "53261-0471")
      (description "CONN HEADER SMD R/A 4POS 1.25MM")
      (fields (field (name "MANUFACTURER") "Molex"))
      (libsource (lib "All_N_Cube3_Components") (part "53261-0471"))
    )
    (comp (ref "U1")
      (value "IRF7329TRPBF")
      (footprint "IRF7329TRPBF")
      (description "MOSFET 2P-CH 12V 9.2A 8-SOIC")
      (fields (field (name "MANUFACTURER") "International Rectifier"))
      (libsource (lib "RG_Projects") (part "IRF7329TRPBF"))
    )
    (comp (ref "U2")
      (value "IRF7329TRPBF")
      (footprint "IRF7329TRPBF")
      (description "MOSFET 2P-CH 12V 9.2A 8-SOIC")
      (fields (field (name "MANUFACTURER") "International Rectifier"))
      (libsource (lib "RG_Projects") (part "IRF7329TRPBF"))
    )
    (comp (ref "U3")
      (value "IRF7329TRPBF")
      (footprint "IRF7329TRPBF")
      (description "MOSFET 2P-CH 12V 9.2A 8-SOIC")
      (fields (field (name "MANUFACTURER") "International Rectifier"))
      (libsource (lib "RG_Projects") (part "IRF7329TRPBF"))
    )
    (comp (ref "U4")
      (value "IRF7329TRPBF")
      (footprint "IRF7329TRPBF")
      (description "MOSFET 2P-CH 12V 9.2A 8-SOIC")
      (fields (field (name "MANUFACTURER") "International Rectifier"))
      (libsource (lib "RG_Projects") (part "IRF7329TRPBF"))
    )
    (comp (ref "U5")
      (value "TPS621361RGXR")
      (footprint "TPS621361RGXR")
      (description "IC REG BUCK ADJUSTABLE 4A 11VQFN")
      (fields (field (name "MANUFACTURER") "Texas Instruments"))
      (libsource (lib "RG_Projects") (part "TPS621361RGXR"))
    )
    (comp (ref "U6")
      (value "IRFML8244TRPBF")
      (footprint "IRFML8244TRPBF")
      (description "MOSFET N-CH 25V 5.8A SOT23")
      (fields (field (name "MANUFACTURER") "International Rectifier"))
      (libsource (lib "RG_Projects") (part "IRFML8244TRPBF"))
    )
    (comp (ref "U7")
      (value "IRFML8244TRPBF")
      (footprint "IRFML8244TRPBF")
      (description "MOSFET N-CH 25V 5.8A SOT23")
      (fields (field (name "MANUFACTURER") "International Rectifier"))
      (libsource (lib "RG_Projects") (part "IRFML8244TRPBF"))
    )
    (comp (ref "U8")
      (value "LMZ22005")
      (footprint "LMZ22005TZX/NOPB")
      (description "DC DC CONVERTER 0.8-6V")
      (fields
        (field (name "MANUFACTURER") "TI National Semiconductor")
        (field (name "MANUFACTURER PART NUMBER") "LMZ22005TZX/NOPB")
      )
      (libsource (lib "RG_Projects") (part "LMZ22005TZX/NOPB"))
    )
    (comp (ref "U9")
      (value "LT6106")
      (footprint "LT6106HS5#TRPBF")
      (description "IC OPAMP CURR SENSE TSOT23-5")
      (fields
        (field (name "MANUFACTURER") "Linear Technology")
        (field (name "MANUFACTURER PART NUMBER") "LT6106HS5#TRMPBF")
      )
      (libsource (lib "All_N_Cube3_Components") (part "LT6106HS5#TRPBF"))
    )
    (comp (ref "U10")
      (value "LT6106")
      (footprint "LT6106HS5#TRPBF")
      (description "IC OPAMP CURR SENSE TSOT23-5")
      (fields
        (field (name "MANUFACTURER") "Linear Technology")
        (field (name "MANUFACTURER PART NUMBER") "LT6106HS5#TRMPBF")
      )
      (libsource (lib "All_N_Cube3_Components") (part "LT6106HS5#TRPBF"))
    )
    (comp (ref "U11")
      (value "LTC4361")
      (footprint "LTC4361HTS8-2")
      (description "IC OVERVOLT PROT CONT TSOT23-8")
      (fields
        (field (name "MANUFACTURER") "Linear Technology")
        (field (name "MANUFACTURER PART NUMBER") "LTC4361ITS8-2#TRMPBF")
      )
      (libsource (lib "All_ESK_Components") (part "LTC4361HTS8-2#TRMPBF"))
    )
    (comp (ref "U12")
      (value "LTC4361")
      (footprint "LTC4361HTS8-2")
      (description "IC OVERVOLT PROT CONT TSOT23-8")
      (fields
        (field (name "MANUFACTURER") "Linear Technology")
        (field (name "MANUFACTURER PART NUMBER") "LTC4361ITS8-2#TRMPBF")
      )
      (libsource (lib "All_ESK_Components") (part "LTC4361HTS8-2#TRMPBF"))
    )
    (comp (ref "U13")
      (value "G6SK-2G DC5")
      (footprint "G6SK-2G DC5")
      (description "RELAY TELECOM DPDT 2A 5V")
      (fields (field (name "MANUFACTURER") "Omron Electronics Inc-EMC Div"))
      (libsource (lib "All_N_Cube3_Components") (part "G6SK-2G DC5"))
    )
    (comp (ref "U14")
      (value "IRFML8244TRPBF")
      (footprint "IRFML8244TRPBF")
      (description "MOSFET N-CH 25V 5.8A SOT23")
      (fields (field (name "MANUFACTURER") "International Rectifier"))
      (libsource (lib "RG_Projects") (part "IRFML8244TRPBF"))
    )
    (comp (ref "U15")
      (value "IRFML8244TRPBF")
      (footprint "IRFML8244TRPBF")
      (description "MOSFET N-CH 25V 5.8A SOT23")
      (fields (field (name "MANUFACTURER") "International Rectifier"))
      (libsource (lib "RG_Projects") (part "IRFML8244TRPBF"))
    )
    (comp (ref "U16")
      (value "IRFML8244TRPBF")
      (footprint "IRFML8244TRPBF")
      (description "MOSFET N-CH 25V 5.8A SOT23")
      (fields (field (name "MANUFACTURER") "International Rectifier"))
      (libsource (lib "RG_Projects") (part "IRFML8244TRPBF"))
    )
    (comp (ref "U17")
      (value "LMZ22005")
      (footprint "LMZ22005TZX/NOPB")
      (description "DC DC CONVERTER 0.8-6V")
      (fields
        (field (name "MANUFACTURER") "TI National Semiconductor")
        (field (name "MANUFACTURER PART NUMBER") "LMZ22005TZX/NOPB")
      )
      (libsource (lib "RG_Projects") (part "LMZ22005TZX/NOPB"))
    )
    (comp (ref "U18")
      (value "TPS621361RGXR")
      (footprint "TPS621361RGXR")
      (description "IC REG BUCK ADJUSTABLE 4A 11VQFN")
      (fields (field (name "MANUFACTURER") "Texas Instruments"))
      (libsource (lib "RG_Projects") (part "TPS621361RGXR"))
    )
    (comp (ref "U19")
      (value "LT6106")
      (footprint "LT6106HS5#TRPBF")
      (description "IC OPAMP CURR SENSE TSOT23-5")
      (fields
        (field (name "MANUFACTURER") "Linear Technology")
        (field (name "MANUFACTURER PART NUMBER") "LT6106HS5#TRMPBF")
      )
      (libsource (lib "All_N_Cube3_Components") (part "LT6106HS5#TRPBF"))
    )
    (comp (ref "U20")
      (value "LTC4361")
      (footprint "LTC4361HTS8-2")
      (description "IC OVERVOLT PROT CONT TSOT23-8")
      (fields
        (field (name "MANUFACTURER") "Linear Technology")
        (field (name "MANUFACTURER PART NUMBER") "LTC4361ITS8-2#TRMPBF")
      )
      (libsource (lib "All_ESK_Components") (part "LTC4361HTS8-2#TRMPBF"))
    )
    (comp (ref "U21")
      (value "LTC4361")
      (footprint "LTC4361HTS8-2")
      (description "IC OVERVOLT PROT CONT TSOT23-8")
      (fields
        (field (name "MANUFACTURER") "Linear Technology")
        (field (name "MANUFACTURER PART NUMBER") "LTC4361ITS8-2#TRMPBF")
      )
      (libsource (lib "All_ESK_Components") (part "LTC4361HTS8-2#TRMPBF"))
    )
    (comp (ref "U22")
      (value "LTC4361")
      (footprint "LTC4361HTS8-2")
      (description "IC OVERVOLT PROT CONT TSOT23-8")
      (fields
        (field (name "MANUFACTURER") "Linear Technology")
        (field (name "MANUFACTURER PART NUMBER") "LTC4361ITS8-2#TRMPBF")
      )
      (libsource (lib "All_ESK_Components") (part "LTC4361HTS8-2#TRMPBF"))
    )
    (comp (ref "U23")
      (value "INA286")
      (footprint "INA286AQDRQ1")
      (description "IC CURRENT SHUNT MONITOR 8SOIC")
      (fields
        (field (name "MANUFACTURER") "Texas Instruments")
        (field (name "MANUFACTURER PART NUMBER") "INA286AQDRQ1")
      )
      (libsource (lib "RG_Projects") (part "INA286AQDRQ1"))
    )
    (comp (ref "U24")
      (value "IRFML8244TRPBF")
      (footprint "IRFML8244TRPBF")
      (description "MOSFET N-CH 25V 5.8A SOT23")
      (fields (field (name "MANUFACTURER") "International Rectifier"))
      (libsource (lib "RG_Projects") (part "IRFML8244TRPBF"))
    )
    (comp (ref "U25")
      (value "IRFML8244TRPBF")
      (footprint "IRFML8244TRPBF")
      (description "MOSFET N-CH 25V 5.8A SOT23")
      (fields (field (name "MANUFACTURER") "International Rectifier"))
      (libsource (lib "RG_Projects") (part "IRFML8244TRPBF"))
    )
    (comp (ref "U26")
      (value "IRFML8244TRPBF")
      (footprint "IRFML8244TRPBF")
      (description "MOSFET N-CH 25V 5.8A SOT23")
      (fields (field (name "MANUFACTURER") "International Rectifier"))
      (libsource (lib "RG_Projects") (part "IRFML8244TRPBF"))
    )
    (comp (ref "U27")
      (value "LTC3119")
      (footprint "LTC3119EUFD#PBF")
      (description "IC REG BCK BST ADJ 5A 28QFN")
      (fields
        (field (name "MANUFACTURER") "Analog Devices / Linear Technology")
        (field (name "MANUFACTURER PART NUMBER") "LTC3119EUFD#PBF")
      )
      (libsource (lib "RG_Projects") (part "LTC3119EUFD#PBF"))
    )
    (comp (ref "U28")
      (value "LMZ22005")
      (footprint "LMZ22005TZX/NOPB")
      (description "DC DC CONVERTER 0.8-6V")
      (fields
        (field (name "MANUFACTURER") "TI National Semiconductor")
        (field (name "MANUFACTURER PART NUMBER") "LMZ22005TZX/NOPB")
      )
      (libsource (lib "RG_Projects") (part "LMZ22005TZX/NOPB"))
    )
    (comp (ref "U29")
      (value "LT6106")
      (footprint "LT6106HS5#TRPBF")
      (description "IC OPAMP CURR SENSE TSOT23-5")
      (fields
        (field (name "MANUFACTURER") "Linear Technology")
        (field (name "MANUFACTURER PART NUMBER") "LT6106HS5#TRMPBF")
      )
      (libsource (lib "All_N_Cube3_Components") (part "LT6106HS5#TRPBF"))
    )
    (comp (ref "U30")
      (value "LTC4361")
      (footprint "LTC4361HTS8-2")
      (description "IC OVERVOLT PROT CONT TSOT23-8")
      (fields
        (field (name "MANUFACTURER") "Linear Technology")
        (field (name "MANUFACTURER PART NUMBER") "LTC4361ITS8-2#TRMPBF")
      )
      (libsource (lib "All_ESK_Components") (part "LTC4361HTS8-2#TRMPBF"))
    )
    (comp (ref "U31")
      (value "LTC4361")
      (footprint "LTC4361HTS8-2")
      (description "IC OVERVOLT PROT CONT TSOT23-8")
      (fields
        (field (name "MANUFACTURER") "Linear Technology")
        (field (name "MANUFACTURER PART NUMBER") "LTC4361ITS8-2#TRMPBF")
      )
      (libsource (lib "All_ESK_Components") (part "LTC4361HTS8-2#TRMPBF"))
    )
    (comp (ref "U32")
      (value "LTC4361")
      (footprint "LTC4361HTS8-2")
      (description "IC OVERVOLT PROT CONT TSOT23-8")
      (fields
        (field (name "MANUFACTURER") "Linear Technology")
        (field (name "MANUFACTURER PART NUMBER") "LTC4361ITS8-2#TRMPBF")
      )
      (libsource (lib "All_ESK_Components") (part "LTC4361HTS8-2#TRMPBF"))
    )
    (comp (ref "U33")
      (value "IRFML8244TRPBF")
      (footprint "IRFML8244TRPBF")
      (description "MOSFET N-CH 25V 5.8A SOT23")
      (fields (field (name "MANUFACTURER") "International Rectifier"))
      (libsource (lib "RG_Projects") (part "IRFML8244TRPBF"))
    )
    (comp (ref "U34")
      (value "IRFML8244TRPBF")
      (footprint "IRFML8244TRPBF")
      (description "MOSFET N-CH 25V 5.8A SOT23")
      (fields (field (name "MANUFACTURER") "International Rectifier"))
      (libsource (lib "RG_Projects") (part "IRFML8244TRPBF"))
    )
    (comp (ref "U35")
      (value "LTC4361")
      (footprint "LTC4361HTS8-2")
      (description "IC OVERVOLT PROT CONT TSOT23-8")
      (fields
        (field (name "MANUFACTURER") "Linear Technology")
        (field (name "MANUFACTURER PART NUMBER") "LTC4361ITS8-2#TRMPBF")
      )
      (libsource (lib "All_ESK_Components") (part "LTC4361HTS8-2#TRMPBF"))
    )
    (comp (ref "U36")
      (value "LTC4361")
      (footprint "LTC4361HTS8-2")
      (description "IC OVERVOLT PROT CONT TSOT23-8")
      (fields
        (field (name "MANUFACTURER") "Linear Technology")
        (field (name "MANUFACTURER PART NUMBER") "LTC4361ITS8-2#TRMPBF")
      )
      (libsource (lib "All_ESK_Components") (part "LTC4361HTS8-2#TRMPBF"))
    )
    (comp (ref "U37")
      (value "CD74HC4051QPWRQ1")
      (footprint "CD74HC4051QPWRQ1")
      (description "IC MUX/DEMUX 8X1 16TSSOP")
      (fields (field (name "MANUFACTURER") "Texas Instruments") (field (name "BASE PART NUMBER") "74HC4051"))
      (libsource (lib "All_N_Cube3_Components") (part "CD74HC4051QPWRQ1"))
    )
    (comp (ref "U38")
      (value "CD74HC4051QPWRQ1")
      (footprint "CD74HC4051QPWRQ1")
      (description "IC MUX/DEMUX 8X1 16TSSOP")
      (fields (field (name "MANUFACTURER") "Texas Instruments") (field (name "BASE PART NUMBER") "74HC4051"))
      (libsource (lib "All_N_Cube3_Components") (part "CD74HC4051QPWRQ1"))
    )
  )
  (nets
    (net (code "1") (name "/+5V") (class "Default")
      (node (ref "C33") (pin "2") (pinfunction "2_2") (pintype "passive"))
      (node (ref "C40") (pin "2") (pinfunction "2_2") (pintype "passive"))
      (node (ref "C58") (pin "2") (pinfunction "2_2") (pintype "passive"))
      (node (ref "C59") (pin "2") (pinfunction "2_2") (pintype "passive"))
      (node (ref "D3") (pin "1") (pinfunction "1_1") (pintype "passive"))
      (node (ref "D4") (pin "1") (pinfunction "1_1") (pintype "passive"))
      (node (ref "U13") (pin "1") (pinfunction "S+_1") (pintype "passive"))
      (node (ref "U13") (pin "5") (pinfunction "R+_5") (pintype "passive"))
      (node (ref "U23") (pin "6") (pinfunction "V+_6") (pintype "passive"))
      (node (ref "U23") (pin "7") (pinfunction "REF1_7") (pintype "passive"))
      (node (ref "U25") (pin "2") (pinfunction "S_2") (pintype "passive"))
      (node (ref "U31") (pin "2") (pinfunction "OUT_2") (pintype "passive"))
      (node (ref "U37") (pin "16") (pinfunction "VCC_16") (pintype "passive"))
      (node (ref "U38") (pin "16") (pinfunction "VCC_16") (pintype "passive"))
    )
    (net (code "2") (name "/+5V_BUS") (class "Default")
      (node (ref "J12") (pin "2") (pinfunction "2_2") (pintype "passive"))
      (node (ref "R120") (pin "1") (pinfunction "1_1") (pintype "passive"))
      (node (ref "R121") (pin "1") (pinfunction "1_1") (pintype "passive"))
      (node (ref "R122") (pin "1") (pinfunction "1_1") (pintype "passive"))
      (node (ref "R123") (pin "1") (pinfunction "1_1") (pintype "passive"))
      (node (ref "R90") (pin "1") (pinfunction "1_1") (pintype "passive"))
      (node (ref "R91") (pin "1") (pinfunction "1_1") (pintype "passive"))
      (node (ref "R92") (pin "1") (pinfunction "1_1") (pintype "passive"))
      (node (ref "R96") (pin "1") (pinfunction "1_1") (pintype "passive"))
      (node (ref "R97") (pin "1") (pinfunction "1_1") (pintype "passive"))
      (node (ref "R98") (pin "1") (pinfunction "1_1") (pintype "passive"))
      (node (ref "U30") (pin "3") (pinfunction "GATEP_3") (pintype "passive"))
      (node (ref "U30") (pin "5") (pinfunction "IN_5") (pintype "passive"))
      (node (ref "U31") (pin "3") (pinfunction "GATEP_3") (pintype "passive"))
      (node (ref "U31") (pin "5") (pinfunction "IN_5") (pintype "passive"))
      (node (ref "U32") (pin "3") (pinfunction "GATEP_3") (pintype "passive"))
      (node (ref "U32") (pin "5") (pinfunction "IN_5") (pintype "passive"))
      (node (ref "U35") (pin "3") (pinfunction "GATEP_3") (pintype "passive"))
      (node (ref "U35") (pin "5") (pinfunction "IN_5") (pintype "passive"))
      (node (ref "U36") (pin "3") (pinfunction "GATEP_3") (pintype "passive"))
      (node (ref "U36") (pin "5") (pinfunction "IN_5") (pintype "passive"))
    )
    (net (code "3") (name "/+8.82Vout1") (class "Default")
      (node (ref "C11") (pin "2") (pinfunction "2_2") (pintype "passive"))
      (node (ref "C12") (pin "2") (pinfunction "2_2") (pintype "passive"))
      (node (ref "D2") (pin "2") (pinfunction "2_2") (pintype "passive"))
      (node (ref "L1") (pin "2") (pinfunction "2_2") (pintype "passive"))
      (node (ref "R12") (pin "2") (pinfunction "2_2") (pintype "passive"))
      (node (ref "R16") (pin "1") (pinfunction "1_1") (pintype "passive"))
      (node (ref "U5") (pin "6") (pinfunction "VOS_6") (pintype "passive"))
    )
    (net (code "4") (name "/+8.82Vout2") (class "Default")
      (node (ref "C27") (pin "2") (pinfunction "2_2") (pintype "passive"))
      (node (ref "C28") (pin "2") (pinfunction "2_2") (pintype "passive"))
      (node (ref "D6") (pin "2") (pinfunction "2_2") (pintype "passive"))
      (node (ref "L2") (pin "2") (pinfunction "2_2") (pintype "passive"))
      (node (ref "R68") (pin "2") (pinfunction "2_2") (pintype "passive"))
      (node (ref "R69") (pin "1") (pinfunction "1_1") (pintype "passive"))
      (node (ref "U18") (pin "6") (pinfunction "VOS_6") (pintype "passive"))
    )
    (net (code "5") (name "/+8.82Vout3") (class "Default")
      (node (ref "C46") (pin "2") (pinfunction "2_2") (pintype "passive"))
      (node (ref "C47") (pin "2") (pinfunction "2_2") (pintype "passive"))
      (node (ref "D8") (pin "2") (pinfunction "2_2") (pintype "passive"))
      (node (ref "R108") (pin "2") (pinfunction "2_2") (pintype "passive"))
      (node (ref "U27") (pin "3") (pinfunction "PVout_3") (pintype "passive"))
      (node (ref "U27") (pin "4") (pinfunction "PVout_4") (pintype "passive"))
    )
    (net (code "6") (name "/+X") (class "Default")
      (node (ref "+X") (pin "1") (pinfunction "1_1") (pintype "passive"))
      (node (ref "-X") (pin "1") (pinfunction "1_1") (pintype "passive"))
      (node (ref "C10") (pin "2") (pinfunction "2_2") (pintype "passive"))
      (node (ref "C9") (pin "2") (pinfunction "2_2") (pintype "passive"))
      (node (ref "D1") (pin "2") (pinfunction "2_2") (pintype "passive"))
      (node (ref "R11") (pin "2") (pinfunction "2_2") (pintype "passive"))
      (node (ref "R72") (pin "2") (pinfunction "2_2") (pintype "passive"))
      (node (ref "U5") (pin "1") (pinfunction "VIN_1") (pintype "passive"))
      (node (ref "U5") (pin "8") (pinfunction "EN_8") (pintype "passive"))
    )
    (net (code "7") (name "/+Y") (class "Default")
      (node (ref "+Y") (pin "1") (pinfunction "1_1") (pintype "passive"))
      (node (ref "-Y") (pin "1") (pinfunction "1_1") (pintype "passive"))
      (node (ref "C25") (pin "2") (pinfunction "2_2") (pintype "passive"))
      (node (ref "C26") (pin "2") (pinfunction "2_2") (pintype "passive"))
      (node (ref "D5") (pin "2") (pinfunction "2_2") (pintype "passive"))
      (node (ref "R67") (pin "2") (pinfunction "2_2") (pintype "passive"))
      (node (ref "U18") (pin "1") (pinfunction "VIN_1") (pintype "passive"))
      (node (ref "U18") (pin "8") (pinfunction "EN_8") (pintype "passive"))
    )
    (net (code "8") (name "/+Z") (class "Default")
      (node (ref "+Z") (pin "1") (pinfunction "1_1") (pintype "passive"))
      (node (ref "C51") (pin "2") (pinfunction "2_2") (pintype "passive"))
      (node (ref "C52") (pin "2") (pinfunction "2_2") (pintype "passive"))
      (node (ref "D7") (pin "2") (pinfunction "2_2") (pintype "passive"))
      (node (ref "R103") (pin "2") (pinfunction "2_2") (pintype "passive"))
      (node (ref "U27") (pin "15") (pinfunction "RUN_15") (pintype "passive"))
      (node (ref "U27") (pin "16") (pinfunction "VIN_16") (pintype "passive"))
      (node (ref "U27") (pin "19") (pinfunction "PVin_19") (pintype "passive"))
      (node (ref "U27") (pin "20") (pinfunction "PVin_20") (pintype "passive"))
    )
    (net (code "9") (name "/3V3_1_COM") (class "Default")
      (node (ref "C6") (pin "1") (pinfunction "1_1") (pintype "passive"))
      (node (ref "C7") (pin "1") (pinfunction "1_1") (pintype "passive"))
      (node (ref "R14") (pin "2") (pinfunction "2_2") (pintype "passive"))
      (node (ref "R15") (pin "2") (pinfunction "2_2") (pintype "passive"))
      (node (ref "R3") (pin "1") (pinfunction "1_1") (pintype "passive"))
      (node (ref "R7") (pin "1") (pinfunction "1_1") (pintype "passive"))
      (node (ref "R8") (pin "2") (pinfunction "2_2") (pintype "passive"))
      (node (ref "U10") (pin "5") (pinfunction "V+_5") (pintype "passive"))
      (node (ref "U8") (pin "7") (pinfunction "VOUT_7") (pintype "passive"))
    )
    (net (code "10") (name "/3V3_2_BUS") (class "Default")
      (node (ref "C22") (pin "1") (pinfunction "1_1") (pintype "passive"))
      (node (ref "C23") (pin "1") (pinfunction "1_1") (pintype "passive"))
      (node (ref "R55") (pin "1") (pinfunction "1_1") (pintype "passive"))
      (node (ref "R59") (pin "1") (pinfunction "1_1") (pintype "passive"))
      (node (ref "R60") (pin "2") (pinfunction "2_2") (pintype "passive"))
      (node (ref "R65") (pin "2") (pinfunction "2_2") (pintype "passive"))
      (node (ref "R66") (pin "2") (pinfunction "2_2") (pintype "passive"))
      (node (ref "U17") (pin "7") (pinfunction "VOUT_7") (pintype "passive"))
      (node (ref "U19") (pin "5") (pinfunction "V+_5") (pintype "passive"))
    )
    (net (code "11") (name "/3V3_BUS") (class "Default")
      (node (ref "J8") (pin "2") (pinfunction "2_2") (pintype "passive"))
      (node (ref "R10") (pin "1") (pinfunction "1_1") (pintype "passive"))
      (node (ref "R5") (pin "1") (pinfunction "1_1") (pintype "passive"))
      (node (ref "R56") (pin "1") (pinfunction "1_1") (pintype "passive"))
      (node (ref "R57") (pin "1") (pinfunction "1_1") (pintype "passive"))
      (node (ref "R58") (pin "1") (pinfunction "1_1") (pintype "passive"))
      (node (ref "R61") (pin "1") (pinfunction "1_1") (pintype "passive"))
      (node (ref "R62") (pin "1") (pinfunction "1_1") (pintype "passive"))
      (node (ref "R63") (pin "1") (pinfunction "1_1") (pintype "passive"))
      (node (ref "U12") (pin "3") (pinfunction "GATEP_3") (pintype "passive"))
      (node (ref "U12") (pin "5") (pinfunction "IN_5") (pintype "passive"))
      (node (ref "U20") (pin "3") (pinfunction "GATEP_3") (pintype "passive"))
      (node (ref "U20") (pin "5") (pinfunction "IN_5") (pintype "passive"))
      (node (ref "U21") (pin "3") (pinfunction "GATEP_3") (pintype "passive"))
      (node (ref "U21") (pin "5") (pinfunction "IN_5") (pintype "passive"))
      (node (ref "U22") (pin "3") (pinfunction "GATEP_3") (pintype "passive"))
      (node (ref "U22") (pin "5") (pinfunction "IN_5") (pintype "passive"))
    )
    (net (code "12") (name "/3V3_COM") (class "Default")
      (node (ref "J3") (pin "2") (pinfunction "2_2") (pintype "passive"))
      (node (ref "R4") (pin "1") (pinfunction "1_1") (pintype "passive"))
      (node (ref "R9") (pin "1") (pinfunction "1_1") (pintype "passive"))
      (node (ref "U11") (pin "3") (pinfunction "GATEP_3") (pintype "passive"))
      (node (ref "U11") (pin "5") (pinfunction "IN_5") (pintype "passive"))
    )
    (net (code "13") (name "/5V_1") (class "Default")
      (node (ref "C36") (pin "1") (pinfunction "1_1") (pintype "passive"))
      (node (ref "C43") (pin "1") (pinfunction "1_1") (pintype "passive"))
      (node (ref "C44") (pin "1") (pinfunction "1_1") (pintype "passive"))
      (node (ref "R100") (pin "2") (pinfunction "2_2") (pintype "passive"))
      (node (ref "R89") (pin "1") (pinfunction "1_1") (pintype "passive"))
      (node (ref "R94") (pin "1") (pinfunction "1_1") (pintype "passive"))
      (node (ref "R95") (pin "2") (pinfunction "2_2") (pintype "passive"))
      (node (ref "R99") (pin "2") (pinfunction "2_2") (pintype "passive"))
      (node (ref "U28") (pin "7") (pinfunction "VOUT_7") (pintype "passive"))
      (node (ref "U29") (pin "5") (pinfunction "V+_5") (pintype "passive"))
    )
    (net (code "14") (name "/ADCS_3V3") (class "Default")
      (node (ref "C19") (pin "2") (pinfunction "2_2") (pintype "passive"))
      (node (ref "U15") (pin "2") (pinfunction "S_2") (pintype "passive"))
      (node (ref "U21") (pin "2") (pinfunction "OUT_2") (pintype "passive"))
    )
    (net (code "15") (name "/ADM_5V") (class "Default")
      (node (ref "C57") (pin "2") (pinfunction "2_2") (pintype "passive"))
      (node (ref "U34") (pin "2") (pinfunction "S_2") (pintype "passive"))
      (node (ref "U36") (pin "2") (pinfunction "OUT_2") (pintype "passive"))
    )
    (net (code "16") (name "/AirCoil_3V3") (class "Default")
      (node (ref "C4") (pin "2") (pinfunction "2_2") (pintype "passive"))
      (node (ref "U12") (pin "2") (pinfunction "OUT_2") (pintype "passive"))
      (node (ref "U7") (pin "2") (pinfunction "S_2") (pintype "passive"))
    )
    (net (code "17") (name "/AntennaTimer_5V") (class "Default")
      (node (ref "C41") (pin "2") (pinfunction "2_2") (pintype "passive"))
      (node (ref "U26") (pin "2") (pinfunction "S_2") (pintype "passive"))
      (node (ref "U32") (pin "2") (pinfunction "OUT_2") (pintype "passive"))
    )
    (net (code "18") (name "/BATT_+") (class "Default")
      (node (ref "BAT") (pin "1") (pinfunction "1_1") (pintype "passive"))
      (node (ref "BAT") (pin "2") (pinfunction "2_2") (pintype "passive"))
      (node (ref "BAT") (pin "3") (pinfunction "3_3") (pintype "passive"))
      (node (ref "F1") (pin "1") (pinfunction "1_1") (pintype "passive"))
      (node (ref "J14") (pin "22") (pinfunction "ASL6_22") (pintype "passive"))
      (node (ref "J14") (pin "24") (pinfunction "ASL5_24") (pintype "passive"))
      (node (ref "J_BAT") (pin "1") (pinfunction "1_1") (pintype "passive"))
      (node (ref "Q2") (pin "3") (pinfunction "C_3") (pintype "passive"))
      (node (ref "Q3") (pin "3") (pinfunction "C_3") (pintype "passive"))
      (node (ref "R45") (pin "1") (pinfunction "1_1") (pintype "passive"))
      (node (ref "R46") (pin "1") (pinfunction "1_1") (pintype "passive"))
    )
    (net (code "19") (name "/BATT_-") (class "Default")
      (node (ref "BAT") (pin "5") (pinfunction "5_5") (pintype "passive"))
      (node (ref "BAT") (pin "6") (pinfunction "6_6") (pintype "passive"))
      (node (ref "BAT") (pin "7") (pinfunction "7_7") (pintype "passive"))
      (node (ref "J14") (pin "26") (pinfunction "ASL4_26") (pintype "passive"))
      (node (ref "J14") (pin "28") (pinfunction "CS10_28") (pintype "passive"))
      (node (ref "J_BAT") (pin "2") (pinfunction "2_2") (pintype "passive"))
      (node (ref "SSW2") (pin "1") (pinfunction "1_1") (pintype "passive"))
    )
    (net (code "20") (name "/BATT_BUS") (class "Default")
      (node (ref "J5") (pin "1") (pinfunction "1_1") (pintype "passive"))
      (node (ref "R64") (pin "2") (pinfunction "2_2") (pintype "passive"))
      (node (ref "R87") (pin "2") (pinfunction "2_2") (pintype "passive"))
      (node (ref "R88") (pin "2") (pinfunction "2_2") (pintype "passive"))
      (node (ref "U23") (pin "8") (pinfunction "+IN_8") (pintype "passive"))
    )
    (net (code "21") (name "/CORE_COM") (class "Default")
      (node (ref "C3") (pin "2") (pinfunction "2_2") (pintype "passive"))
      (node (ref "U11") (pin "2") (pinfunction "OUT_2") (pintype "passive"))
      (node (ref "U6") (pin "2") (pinfunction "S_2") (pintype "passive"))
    )
    (net (code "22") (name "/CORE_OBC") (class "Default")
      (node (ref "C18") (pin "2") (pinfunction "2_2") (pintype "passive"))
      (node (ref "U14") (pin "2") (pinfunction "S_2") (pintype "passive"))
      (node (ref "U20") (pin "2") (pinfunction "OUT_2") (pintype "passive"))
    )
    (net (code "23") (name "/GYRO_5V") (class "Default")
      (node (ref "C56") (pin "2") (pinfunction "2_2") (pintype "passive"))
      (node (ref "Heater") (pin "1") (pinfunction "1_1") (pintype "passive"))
      (node (ref "U33") (pin "2") (pinfunction "S_2") (pintype "passive"))
      (node (ref "U35") (pin "2") (pinfunction "OUT_2") (pintype "passive"))
    )
    (net (code "24") (name "/I_3V3") (class "Default")
      (node (ref "U37") (pin "4") (pinfunction "A7_4") (pintype "passive"))
    )
    (net (code "25") (name "/I_5V") (class "Default")
      (node (ref "U37") (pin "1") (pinfunction "A4_1") (pintype "passive"))
    )
    (net (code "26") (name "/I_BAT") (class "Default")
      (node (ref "U38") (pin "15") (pinfunction "A2_15") (pintype "passive"))
    )
    (net (code "27") (name "/I_COM") (class "Default")
      (node (ref "U37") (pin "14") (pinfunction "A1_14") (pintype "passive"))
    )
    (net (code "28") (name "/I_SA") (class "Default")
      (node (ref "U38") (pin "13") (pinfunction "A0_13") (pintype "passive"))
    )
    (net (code "29") (name "/KILL_SW_FLAG") (class "Default")
      (node (ref "R37") (pin "1") (pinfunction "1_1") (pintype "passive"))
      (node (ref "R44") (pin "2") (pinfunction "2_2") (pintype "passive"))
    )
    (net (code "30") (name "/NC_SW2") (class "Default")
      (node (ref "R38") (pin "2") (pinfunction "2_2") (pintype "passive"))
      (node (ref "SSW1") (pin "1") (pinfunction "1_1") (pintype "passive"))
    )
    (net (code "31") (name "/NO_SW1") (class "Default")
      (node (ref "SSW2") (pin "2") (pinfunction "2_2") (pintype "passive"))
    )
    (net (code "32") (name "/O{slash}P1") (class "Default")
      (node (ref "U38") (pin "3") (pinfunction "A_3") (pintype "passive"))
    )
    (net (code "33") (name "/O{slash}P2") (class "Default")
      (node (ref "U37") (pin "3") (pinfunction "A_3") (pintype "passive"))
    )
    (net (code "34") (name "/PBF1") (class "Default")
      (node (ref "J17") (pin "2") (pinfunction "2_2") (pintype "passive"))
      (node (ref "RBF2") (pin "1") (pinfunction "1_1") (pintype "passive"))
      (node (ref "SSW2") (pin "3") (pinfunction "3_3") (pintype "passive"))
    )
    (net (code "35") (name "/PBF2") (class "Default")
      (node (ref "RBF2") (pin "2") (pinfunction "2_2") (pintype "passive"))
    )
    (net (code "36") (name "/PL_5V") (class "Default")
      (node (ref "C39") (pin "2") (pinfunction "2_2") (pintype "passive"))
      (node (ref "U24") (pin "2") (pinfunction "S_2") (pintype "passive"))
      (node (ref "U30") (pin "2") (pinfunction "OUT_2") (pintype "passive"))
    )
    (net (code "37") (name "/RBF") (class "Default")
      (node (ref "R49") (pin "2") (pinfunction "2_2") (pintype "passive"))
      (node (ref "R50") (pin "1") (pinfunction "1_1") (pintype "passive"))
      (node (ref "RBF1") (pin "1") (pinfunction "1_1") (pintype "passive"))
    )
    (net (code "38") (name "/S0") (class "Default")
      (node (ref "U37") (pin "11") (pinfunction "S0_11") (pintype "passive"))
      (node (ref "U38") (pin "11") (pinfunction "S0_11") (pintype "passive"))
    )
    (net (code "39") (name "/S1") (class "Default")
      (node (ref "U37") (pin "10") (pinfunction "S1_10") (pintype "passive"))
      (node (ref "U38") (pin "10") (pinfunction "S1_10") (pintype "passive"))
    )
    (net (code "40") (name "/S2") (class "Default")
      (node (ref "U37") (pin "9") (pinfunction "S2_9") (pintype "passive"))
      (node (ref "U38") (pin "9") (pinfunction "S2_9") (pintype "passive"))
    )
    (net (code "41") (name "/SAR_3V3") (class "Default")
      (node (ref "C20") (pin "2") (pinfunction "2_2") (pintype "passive"))
      (node (ref "U16") (pin "2") (pinfunction "S_2") (pintype "passive"))
      (node (ref "U22") (pin "2") (pinfunction "OUT_2") (pintype "passive"))
    )
    (net (code "42") (name "/T1_BAT") (class "Default")
      (node (ref "R124") (pin "1") (pinfunction "1_1") (pintype "passive"))
      (node (ref "Temp") (pin "1") (pinfunction "1_1") (pintype "passive"))
      (node (ref "U38") (pin "1") (pinfunction "A4_1") (pintype "passive"))
    )
    (net (code "43") (name "/T2_BAT") (class "Default")
      (node (ref "R125") (pin "1") (pinfunction "1_1") (pintype "passive"))
      (node (ref "Temp") (pin "2") (pinfunction "2_2") (pintype "passive"))
      (node (ref "U38") (pin "2") (pinfunction "A6_2") (pintype "passive"))
    )
    (net (code "44") (name "/T3_BAT") (class "Default")
      (node (ref "R126") (pin "1") (pinfunction "1_1") (pintype "passive"))
      (node (ref "Temp") (pin "3") (pinfunction "3_3") (pintype "passive"))
      (node (ref "U38") (pin "4") (pinfunction "A7_4") (pintype "passive"))
    )
    (net (code "45") (name "/V_3V3") (class "Default")
      (node (ref "R65") (pin "1") (pinfunction "1_1") (pintype "passive"))
      (node (ref "R74") (pin "2") (pinfunction "2_2") (pintype "passive"))
      (node (ref "U37") (pin "5") (pinfunction "A5_5") (pintype "passive"))
    )
    (net (code "46") (name "/V_5V") (class "Default")
      (node (ref "R104") (pin "2") (pinfunction "2_2") (pintype "passive"))
      (node (ref "R99") (pin "1") (pinfunction "1_1") (pintype "passive"))
      (node (ref "U37") (pin "2") (pinfunction "A6_2") (pintype "passive"))
    )
    (net (code "47") (name "/V_BAT") (class "Default")
      (node (ref "R64") (pin "1") (pinfunction "1_1") (pintype "passive"))
      (node (ref "R70") (pin "2") (pinfunction "2_2") (pintype "passive"))
      (node (ref "U38") (pin "14") (pinfunction "A1_14") (pintype "passive"))
    )
    (net (code "48") (name "/V_BUS") (class "Default")
      (node (ref "D2") (pin "1") (pinfunction "1_1") (pintype "passive"))
      (node (ref "D6") (pin "1") (pinfunction "1_1") (pintype "passive"))
      (node (ref "D8") (pin "1") (pinfunction "1_1") (pintype "passive"))
      (node (ref "R13") (pin "2") (pinfunction "2_2") (pintype "passive"))
      (node (ref "R2") (pin "1") (pinfunction "1_1") (pintype "passive"))
      (node (ref "R6") (pin "1") (pinfunction "1_1") (pintype "passive"))
      (node (ref "U9") (pin "5") (pinfunction "V+_5") (pintype "passive"))
    )
    (net (code "49") (name "/V_BUS_1") (class "Default")
      (node (ref "J1") (pin "1") (pinfunction "1_1") (pintype "passive"))
      (node (ref "R2") (pin "2") (pinfunction "2_2") (pintype "passive"))
      (node (ref "R6") (pin "2") (pinfunction "2_2") (pintype "passive"))
      (node (ref "U9") (pin "4") (pinfunction "+IN_4") (pintype "passive"))
    )
    (net (code "50") (name "/V_BUS_2") (class "Default")
      (node (ref "J1") (pin "2") (pinfunction "2_2") (pintype "passive"))
      (node (ref "R23") (pin "1") (pinfunction "1_1") (pintype "passive"))
      (node (ref "U1") (pin "1") (pinfunction "S1_1") (pintype "passive"))
      (node (ref "U1") (pin "3") (pinfunction "S2_3") (pintype "passive"))
    )
    (net (code "51") (name "/V_BUS_3") (class "Default")
      (node (ref "R24") (pin "1") (pinfunction "1_1") (pintype "passive"))
      (node (ref "U1") (pin "5") (pinfunction "D2_5") (pintype "passive"))
      (node (ref "U1") (pin "6") (pinfunction "D2_6") (pintype "passive"))
      (node (ref "U1") (pin "7") (pinfunction "D1_7") (pintype "passive"))
      (node (ref "U1") (pin "8") (pinfunction "D1_8") (pintype "passive"))
      (node (ref "U2") (pin "1") (pinfunction "S1_1") (pintype "passive"))
      (node (ref "U2") (pin "3") (pinfunction "S2_3") (pintype "passive"))
    )
    (net (code "52") (name "/V_BUS_4") (class "Default")
      (node (ref "J5") (pin "2") (pinfunction "2_2") (pintype "passive"))
      (node (ref "R25") (pin "1") (pinfunction "1_1") (pintype "passive"))
      (node (ref "U2") (pin "5") (pinfunction "D2_5") (pintype "passive"))
      (node (ref "U2") (pin "6") (pinfunction "D2_6") (pintype "passive"))
      (node (ref "U2") (pin "7") (pinfunction "D1_7") (pintype "passive"))
      (node (ref "U2") (pin "8") (pinfunction "D1_8") (pintype "passive"))
      (node (ref "U3") (pin "1") (pinfunction "S1_1") (pintype "passive"))
      (node (ref "U3") (pin "3") (pinfunction "S2_3") (pintype "passive"))
    )
    (net (code "53") (name "/V_BUS_5") (class "Default")
      (node (ref "R26") (pin "1") (pinfunction "1_1") (pintype "passive"))
      (node (ref "U3") (pin "5") (pinfunction "D2_5") (pintype "passive"))
      (node (ref "U3") (pin "6") (pinfunction "D2_6") (pintype "passive"))
      (node (ref "U3") (pin "7") (pinfunction "D1_7") (pintype "passive"))
      (node (ref "U3") (pin "8") (pinfunction "D1_8") (pintype "passive"))
      (node (ref "U4") (pin "1") (pinfunction "S1_1") (pintype "passive"))
      (node (ref "U4") (pin "3") (pinfunction "S2_3") (pintype "passive"))
    )
    (net (code "54") (name "/V_BUS_6") (class "Default")
      (node (ref "J11") (pin "1") (pinfunction "1_1") (pintype "passive"))
      (node (ref "J2") (pin "1") (pinfunction "1_1") (pintype "passive"))
      (node (ref "J7") (pin "1") (pinfunction "1_1") (pintype "passive"))
      (node (ref "U4") (pin "5") (pinfunction "D2_5") (pintype "passive"))
      (node (ref "U4") (pin "6") (pinfunction "D2_6") (pintype "passive"))
      (node (ref "U4") (pin "7") (pinfunction "D1_7") (pintype "passive"))
      (node (ref "U4") (pin "8") (pinfunction "D1_8") (pintype "passive"))
    )
    (net (code "55") (name "/V_COM") (class "Default")
      (node (ref "R14") (pin "1") (pinfunction "1_1") (pintype "passive"))
      (node (ref "R31") (pin "2") (pinfunction "2_2") (pintype "passive"))
      (node (ref "U37") (pin "15") (pinfunction "A2_15") (pintype "passive"))
    )
    (net (code "56") (name "/V_SA") (class "Default")
      (node (ref "R72") (pin "1") (pinfunction "1_1") (pintype "passive"))
      (node (ref "R82") (pin "2") (pinfunction "2_2") (pintype "passive"))
      (node (ref "U38") (pin "12") (pinfunction "A3_12") (pintype "passive"))
    )
    (net (code "57") (name "GND") (class "Default")
      (node (ref "+X") (pin "2") (pinfunction "2_2") (pintype "passive"))
      (node (ref "+Y") (pin "2") (pinfunction "2_2") (pintype "passive"))
      (node (ref "+Z") (pin "2") (pinfunction "2_2") (pintype "passive"))
      (node (ref "-X") (pin "2") (pinfunction "2_2") (pintype "passive"))
      (node (ref "-Y") (pin "2") (pinfunction "2_2") (pintype "passive"))
      (node (ref "C1") (pin "2") (pinfunction "2_2") (pintype "passive"))
      (node (ref "C10") (pin "1") (pinfunction "1_1") (pintype "passive"))
      (node (ref "C11") (pin "1") (pinfunction "1_1") (pintype "passive"))
      (node (ref "C12") (pin "1") (pinfunction "1_1") (pintype "passive"))
      (node (ref "C13") (pin "1") (pinfunction "1_1") (pintype "passive"))
      (node (ref "C14") (pin "2") (pinfunction "2_2") (pintype "passive"))
      (node (ref "C15") (pin "2") (pinfunction "2_2") (pintype "passive"))
      (node (ref "C16") (pin "2") (pinfunction "2_2") (pintype "passive"))
      (node (ref "C17") (pin "2") (pinfunction "2_2") (pintype "passive"))
      (node (ref "C18") (pin "1") (pinfunction "1_1") (pintype "passive"))
      (node (ref "C19") (pin "1") (pinfunction "1_1") (pintype "passive"))
      (node (ref "C2") (pin "2") (pinfunction "2_2") (pintype "passive"))
      (node (ref "C20") (pin "1") (pinfunction "1_1") (pintype "passive"))
      (node (ref "C21") (pin "1") (pinfunction "1_1") (pintype "passive"))
      (node (ref "C22") (pin "2") (pinfunction "2_2") (pintype "passive"))
      (node (ref "C23") (pin "2") (pinfunction "2_2") (pintype "passive"))
      (node (ref "C24") (pin "1") (pinfunction "1_1") (pintype "passive"))
      (node (ref "C25") (pin "1") (pinfunction "1_1") (pintype "passive"))
      (node (ref "C26") (pin "1") (pinfunction "1_1") (pintype "passive"))
      (node (ref "C27") (pin "1") (pinfunction "1_1") (pintype "passive"))
      (node (ref "C28") (pin "1") (pinfunction "1_1") (pintype "passive"))
      (node (ref "C29") (pin "1") (pinfunction "1_1") (pintype "passive"))
      (node (ref "C3") (pin "1") (pinfunction "1_1") (pintype "passive"))
      (node (ref "C30") (pin "2") (pinfunction "2_2") (pintype "passive"))
      (node (ref "C31") (pin "2") (pinfunction "2_2") (pintype "passive"))
      (node (ref "C32") (pin "2") (pinfunction "2_2") (pintype "passive"))
      (node (ref "C33") (pin "1") (pinfunction "1_1") (pintype "passive"))
      (node (ref "C36") (pin "2") (pinfunction "2_2") (pintype "passive"))
      (node (ref "C37") (pin "2") (pinfunction "2_2") (pintype "passive"))
      (node (ref "C38") (pin "2") (pinfunction "2_2") (pintype "passive"))
      (node (ref "C39") (pin "1") (pinfunction "1_1") (pintype "passive"))
      (node (ref "C4") (pin "1") (pinfunction "1_1") (pintype "passive"))
      (node (ref "C40") (pin "1") (pinfunction "1_1") (pintype "passive"))
      (node (ref "C41") (pin "1") (pinfunction "1_1") (pintype "passive"))
      (node (ref "C42") (pin "1") (pinfunction "1_1") (pintype "passive"))
      (node (ref "C43") (pin "2") (pinfunction "2_2") (pintype "passive"))
      (node (ref "C44") (pin "2") (pinfunction "2_2") (pintype "passive"))
      (node (ref "C45") (pin "1") (pinfunction "1_1") (pintype "passive"))
      (node (ref "C46") (pin "1") (pinfunction "1_1") (pintype "passive"))
      (node (ref "C47") (pin "1") (pinfunction "1_1") (pintype "passive"))
      (node (ref "C48") (pin "2") (pinfunction "2_2") (pintype "passive"))
      (node (ref "C49") (pin "2") (pinfunction "2_2") (pintype "passive"))
      (node (ref "C5") (pin "1") (pinfunction "1_1") (pintype "passive"))
      (node (ref "C50") (pin "2") (pinfunction "2_2") (pintype "passive"))
      (node (ref "C51") (pin "1") (pinfunction "1_1") (pintype "passive"))
      (node (ref "C52") (pin "1") (pinfunction "1_1") (pintype "passive"))
      (node (ref "C53") (pin "2") (pinfunction "2_2") (pintype "passive"))
      (node (ref "C54") (pin "1") (pinfunction "1_1") (pintype "passive"))
      (node (ref "C55") (pin "1") (pinfunction "1_1") (pintype "passive"))
      (node (ref "C56") (pin "1") (pinfunction "1_1") (pintype "passive"))
      (node (ref "C57") (pin "1") (pinfunction "1_1") (pintype "passive"))
      (node (ref "C58") (pin "1") (pinfunction "1_1") (pintype "passive"))
      (node (ref "C59") (pin "1") (pinfunction "1_1") (pintype "passive"))
      (node (ref "C6") (pin "2") (pinfunction "2_2") (pintype "passive"))
      (node (ref "C60") (pin "2") (pinfunction "2_2") (pintype "passive"))
      (node (ref "C61") (pin "2") (pinfunction "2_2") (pintype "passive"))
      (node (ref "C7") (pin "2") (pinfunction "2_2") (pintype "passive"))
      (node (ref "C8") (pin "1") (pinfunction "1_1") (pintype "passive"))
      (node (ref "C9") (pin "1") (pinfunction "1_1") (pintype "passive"))
      (node (ref "Heater") (pin "2") (pinfunction "2_2") (pintype "passive"))
      (node (ref "J14") (pin "16") (pinfunction "DGND_16") (pintype "passive"))
      (node (ref "J14") (pin "3") (pinfunction "DGND_3") (pintype "passive"))
      (node (ref "J14") (pin "37") (pinfunction "DGND_37") (pintype "passive"))
      (node (ref "J14") (pin "4") (pinfunction "DGND_4") (pintype "passive"))
      (node (ref "J14") (pin "49") (pinfunction "DGND_49") (pintype "passive"))
      (node (ref "J14") (pin "50") (pinfunction "DGND_50") (pintype "passive"))
      (node (ref "J17") (pin "1") (pinfunction "1_1") (pintype "passive"))
      (node (ref "J19") (pin "35") (pinfunction "DGND_35") (pintype "passive"))
      (node (ref "J19") (pin "37") (pinfunction "DGND_37") (pintype "passive"))
      (node (ref "J19") (pin "38") (pinfunction "DGND_38") (pintype "passive"))
      (node (ref "J19") (pin "8") (pinfunction "DGND_8") (pintype "passive"))
      (node (ref "J_Antenna") (pin "4") (pinfunction "4_4") (pintype "passive"))
      (node (ref "J_SAR") (pin "2") (pinfunction "2_2") (pintype "passive"))
      (node (ref "Q1") (pin "2") (pinfunction "E_2") (pintype "passive"))
      (node (ref "Q10") (pin "2") (pinfunction "E_2") (pintype "passive"))
      (node (ref "Q11") (pin "2") (pinfunction "E_2") (pintype "passive"))
      (node (ref "Q4") (pin "2") (pinfunction "E_2") (pintype "passive"))
      (node (ref "Q5") (pin "2") (pinfunction "E_2") (pintype "passive"))
      (node (ref "Q6") (pin "2") (pinfunction "E_2") (pintype "passive"))
      (node (ref "Q7") (pin "2") (pinfunction "E_2") (pintype "passive"))
      (node (ref "Q8") (pin "2") (pinfunction "E_2") (pintype "passive"))
      (node (ref "Q9") (pin "2") (pinfunction "E_2") (pintype "passive"))
      (node (ref "R101") (pin "1") (pinfunction "1_1") (pintype "passive"))
      (node (ref "R104") (pin "1") (pinfunction "1_1") (pintype "passive"))
      (node (ref "R105") (pin "1") (pinfunction "1_1") (pintype "passive"))
      (node (ref "R106") (pin "2") (pinfunction "2_2") (pintype "passive"))
      (node (ref "R117") (pin "1") (pinfunction "1_1") (pintype "passive"))
      (node (ref "R118") (pin "2") (pinfunction "2_2") (pintype "passive"))
      (node (ref "R119") (pin "2") (pinfunction "2_2") (pintype "passive"))
      (node (ref "R19") (pin "1") (pinfunction "1_1") (pintype "passive"))
      (node (ref "R31") (pin "1") (pinfunction "1_1") (pintype "passive"))
      (node (ref "R32") (pin "1") (pinfunction "1_1") (pintype "passive"))
      (node (ref "R33") (pin "1") (pinfunction "1_1") (pintype "passive"))
      (node (ref "R34") (pin "1") (pinfunction "1_1") (pintype "passive"))
      (node (ref "R35") (pin "2") (pinfunction "2_2") (pintype "passive"))
      (node (ref "R39") (pin "2") (pinfunction "2_2") (pintype "passive"))
      (node (ref "R43") (pin "1") (pinfunction "1_1") (pintype "passive"))
      (node (ref "R44") (pin "1") (pinfunction "1_1") (pintype "passive"))
      (node (ref "R51") (pin "1") (pinfunction "1_1") (pintype "passive"))
      (node (ref "R52") (pin "1") (pinfunction "1_1") (pintype "passive"))
      (node (ref "R70") (pin "1") (pinfunction "1_1") (pintype "passive"))
      (node (ref "R71") (pin "1") (pinfunction "1_1") (pintype "passive"))
      (node (ref "R74") (pin "1") (pinfunction "1_1") (pintype "passive"))
      (node (ref "R78") (pin "1") (pinfunction "1_1") (pintype "passive"))
      (node (ref "R79") (pin "2") (pinfunction "2_2") (pintype "passive"))
      (node (ref "R82") (pin "1") (pinfunction "1_1") (pintype "passive"))
      (node (ref "R83") (pin "2") (pinfunction "2_2") (pintype "passive"))
      (node (ref "R84") (pin "1") (pinfunction "1_1") (pintype "passive"))
      (node (ref "R93") (pin "1") (pinfunction "1_1") (pintype "passive"))
      (node (ref "RBF1") (pin "2") (pinfunction "2_2") (pintype "passive"))
      (node (ref "SSW1") (pin "2") (pinfunction "2_2") (pintype "passive"))
      (node (ref "Temp") (pin "4") (pinfunction "4_4") (pintype "passive"))
      (node (ref "U11") (pin "1") (pinfunction "~{ON}_1") (pintype "passive"))
      (node (ref "U11") (pin "4") (pinfunction "GND_4") (pintype "passive"))
      (node (ref "U12") (pin "4") (pinfunction "GND_4") (pintype "passive"))
      (node (ref "U13") (pin "3") (pinfunction "COM_3") (pintype "passive"))
      (node (ref "U13") (pin "8") (pinfunction "COM_8") (pintype "passive"))
      (node (ref "U17") (pin "2") (pinfunction "SYNC_2") (pintype "passive"))
      (node (ref "U17") (pin "4") (pinfunction "AGND_4") (pintype "passive"))
      (node (ref "U17") (pin "8") (pinfunction "PGND_8") (pintype "passive"))
      (node (ref "U18") (pin "10") (pinfunction "MODE_10") (pintype "passive"))
      (node (ref "U18") (pin "11") (pinfunction "VSEL_11") (pintype "passive"))
      (node (ref "U18") (pin "3") (pinfunction "GND_3") (pintype "passive"))
      (node (ref "U18") (pin "4") (pinfunction "FB2_4") (pintype "passive"))
      (node (ref "U20") (pin "1") (pinfunction "~{ON}_1") (pintype "passive"))
      (node (ref "U20") (pin "4") (pinfunction "GND_4") (pintype "passive"))
      (node (ref "U21") (pin "4") (pinfunction "GND_4") (pintype "passive"))
      (node (ref "U22") (pin "4") (pinfunction "GND_4") (pintype "passive"))
      (node (ref "U27") (pin "1") (pinfunction "PGND_1") (pintype "passive"))
      (node (ref "U27") (pin "11") (pinfunction "SGND_11") (pintype "passive"))
      (node (ref "U27") (pin "17") (pinfunction "PGND_17") (pintype "passive"))
      (node (ref "U27") (pin "22") (pinfunction "PGND_22") (pintype "passive"))
      (node (ref "U27") (pin "24") (pinfunction "NC_24") (pintype "passive"))
      (node (ref "U27") (pin "25") (pinfunction "SYNC_25") (pintype "passive"))
      (node (ref "U27") (pin "26") (pinfunction "NC_26") (pintype "passive"))
      (node (ref "U27") (pin "27") (pinfunction "NC_27") (pintype "passive"))
      (node (ref "U27") (pin "29") (pinfunction "PGND_29") (pintype "passive"))
      (node (ref "U27") (pin "6") (pinfunction "PGND_6") (pintype "passive"))
      (node (ref "U28") (pin "2") (pinfunction "SYNC_2") (pintype "passive"))
      (node (ref "U28") (pin "4") (pinfunction "AGND_4") (pintype "passive"))
      (node (ref "U28") (pin "8") (pinfunction "PGND_8") (pintype "passive"))
      (node (ref "U30") (pin "4") (pinfunction "GND_4") (pintype "passive"))
      (node (ref "U31") (pin "1") (pinfunction "~{ON}_1") (pintype "passive"))
      (node (ref "U31") (pin "4") (pinfunction "GND_4") (pintype "passive"))
      (node (ref "U32") (pin "4") (pinfunction "GND_4") (pintype "passive"))
      (node (ref "U35") (pin "4") (pinfunction "GND_4") (pintype "passive"))
      (node (ref "U36") (pin "4") (pinfunction "GND_4") (pintype "passive"))
      (node (ref "U37") (pin "6") (pinfunction "~{E}_6") (pintype "passive"))
      (node (ref "U37") (pin "7") (pinfunction "VEE_7") (pintype "passive"))
      (node (ref "U37") (pin "8") (pinfunction "GND_8") (pintype "passive"))
      (node (ref "U38") (pin "6") (pinfunction "~{E}_6") (pintype "passive"))
      (node (ref "U38") (pin "7") (pinfunction "VEE_7") (pintype "passive"))
      (node (ref "U38") (pin "8") (pinfunction "GND_8") (pintype "passive"))
      (node (ref "U5") (pin "10") (pinfunction "MODE_10") (pintype "passive"))
      (node (ref "U5") (pin "11") (pinfunction "VSEL_11") (pintype "passive"))
      (node (ref "U5") (pin "3") (pinfunction "GND_3") (pintype "passive"))
      (node (ref "U5") (pin "4") (pinfunction "FB2_4") (pintype "passive"))
      (node (ref "U8") (pin "2") (pinfunction "SYNC_2") (pintype "passive"))
      (node (ref "U8") (pin "4") (pinfunction "AGND_4") (pintype "passive"))
      (node (ref "U8") (pin "8") (pinfunction "PGND_8") (pintype "passive"))
    )
    (net (code "58") (name "Net-(C34-Pad2)") (class "Default")
      (node (ref "C34") (pin "2") (pinfunction "2_2") (pintype "passive"))
      (node (ref "L3") (pin "1") (pinfunction "1_1") (pintype "passive"))
      (node (ref "U27") (pin "18") (pinfunction "SW1_18") (pintype "passive"))
      (node (ref "U27") (pin "21") (pinfunction "SW1_21") (pintype "passive"))
    )
    (net (code "59") (name "Net-(C35-Pad2)") (class "Default")
      (node (ref "C35") (pin "2") (pinfunction "2_2") (pintype "passive"))
      (node (ref "L3") (pin "2") (pinfunction "2_2") (pintype "passive"))
      (node (ref "U27") (pin "2") (pinfunction "SW2_2") (pintype "passive"))
      (node (ref "U27") (pin "5") (pinfunction "SW2_5") (pintype "passive"))
    )
    (net (code "60") (name "Net-(C54-Pad2)") (class "Default")
      (node (ref "C54") (pin "2") (pinfunction "2_2") (pintype "passive"))
      (node (ref "R112") (pin "1") (pinfunction "1_1") (pintype "passive"))
    )
    (net (code "61") (name "Net-(C55-Pad2)") (class "Default")
      (node (ref "C55") (pin "2") (pinfunction "2_2") (pintype "passive"))
      (node (ref "R116") (pin "1") (pinfunction "1_1") (pintype "passive"))
    )
    (net (code "62") (name "Net-(Q1-B)") (class "Default")
      (node (ref "Q1") (pin "1") (pinfunction "B_1") (pintype "passive"))
      (node (ref "R47") (pin "1") (pinfunction "1_1") (pintype "passive"))
    )
    (net (code "63") (name "Net-(Q1-C)") (class "Default")
      (node (ref "Q1") (pin "3") (pinfunction "C_3") (pintype "passive"))
      (node (ref "R40") (pin "1") (pinfunction "1_1") (pintype "passive"))
      (node (ref "U12") (pin "1") (pinfunction "~{ON}_1") (pintype "passive"))
    )
    (net (code "64") (name "Net-(Q2-B)") (class "Default")
      (node (ref "Q2") (pin "1") (pinfunction "B_1") (pintype "passive"))
      (node (ref "R45") (pin "2") (pinfunction "2_2") (pintype "passive"))
      (node (ref "R49") (pin "1") (pinfunction "1_1") (pintype "passive"))
    )
    (net (code "65") (name "Net-(Q2-E)") (class "Default")
      (node (ref "Q2") (pin "2") (pinfunction "E_2") (pintype "passive"))
      (node (ref "R41") (pin "1") (pinfunction "1_1") (pintype "passive"))
      (node (ref "R51") (pin "2") (pinfunction "2_2") (pintype "passive"))
    )
    (net (code "66") (name "Net-(Q3-B)") (class "Default")
      (node (ref "Q3") (pin "1") (pinfunction "B_1") (pintype "passive"))
      (node (ref "R46") (pin "2") (pinfunction "2_2") (pintype "passive"))
      (node (ref "R50") (pin "2") (pinfunction "2_2") (pintype "passive"))
    )
    (net (code "67") (name "Net-(Q3-E)") (class "Default")
      (node (ref "Q3") (pin "2") (pinfunction "E_2") (pintype "passive"))
      (node (ref "R42") (pin "1") (pinfunction "1_1") (pintype "passive"))
      (node (ref "R52") (pin "2") (pinfunction "2_2") (pintype "passive"))
    )
    (net (code "68") (name "Net-(Q4-B)") (class "Default")
      (node (ref "Q4") (pin "1") (pinfunction "B_1") (pintype "passive"))
      (node (ref "R54") (pin "2") (pinfunction "2_2") (pintype "passive"))
    )
    (net (code "69") (name "Net-(Q4-C)") (class "Default")
      (node (ref "D4") (pin "2") (pinfunction "2_2") (pintype "passive"))
      (node (ref "Q4") (pin "3") (pinfunction "C_3") (pintype "passive"))
      (node (ref "U13") (pin "6") (pinfunction "R-_6") (pintype "passive"))
    )
    (net (code "70") (name "Net-(Q5-B)") (class "Default")
      (node (ref "Q5") (pin "1") (pinfunction "B_1") (pintype "passive"))
      (node (ref "R53") (pin "1") (pinfunction "1_1") (pintype "passive"))
    )
    (net (code "71") (name "Net-(Q5-C)") (class "Default")
      (node (ref "D3") (pin "2") (pinfunction "2_2") (pintype "passive"))
      (node (ref "Q5") (pin "3") (pinfunction "C_3") (pintype "passive"))
      (node (ref "U13") (pin "10") (pinfunction "S-_10") (pintype "passive"))
    )
    (net (code "72") (name "Net-(Q6-B)") (class "Default")
      (node (ref "Q6") (pin "1") (pinfunction "B_1") (pintype "passive"))
      (node (ref "R85") (pin "1") (pinfunction "1_1") (pintype "passive"))
    )
    (net (code "73") (name "Net-(Q6-C)") (class "Default")
      (node (ref "Q6") (pin "3") (pinfunction "C_3") (pintype "passive"))
      (node (ref "R80") (pin "1") (pinfunction "1_1") (pintype "passive"))
      (node (ref "U21") (pin "1") (pinfunction "~{ON}_1") (pintype "passive"))
    )
    (net (code "74") (name "Net-(Q7-B)") (class "Default")
      (node (ref "Q7") (pin "1") (pinfunction "B_1") (pintype "passive"))
      (node (ref "R86") (pin "1") (pinfunction "1_1") (pintype "passive"))
    )
    (net (code "75") (name "Net-(Q7-C)") (class "Default")
      (node (ref "Q7") (pin "3") (pinfunction "C_3") (pintype "passive"))
      (node (ref "R81") (pin "1") (pinfunction "1_1") (pintype "passive"))
      (node (ref "U22") (pin "1") (pinfunction "~{ON}_1") (pintype "passive"))
    )
    (net (code "76") (name "Net-(Q8-B)") (class "Default")
      (node (ref "Q8") (pin "1") (pinfunction "B_1") (pintype "passive"))
      (node (ref "R114") (pin "1") (pinfunction "1_1") (pintype "passive"))
    )
    (net (code "77") (name "Net-(Q8-C)") (class "Default")
      (node (ref "Q8") (pin "3") (pinfunction "C_3") (pintype "passive"))
      (node (ref "R109") (pin "1") (pinfunction "1_1") (pintype "passive"))
      (node (ref "U30") (pin "1") (pinfunction "~{ON}_1") (pintype "passive"))
    )
    (net (code "78") (name "Net-(Q9-B)") (class "Default")
      (node (ref "Q9") (pin "1") (pinfunction "B_1") (pintype "passive"))
      (node (ref "R115") (pin "1") (pinfunction "1_1") (pintype "passive"))
    )
    (net (code "79") (name "Net-(Q9-C)") (class "Default")
      (node (ref "Q9") (pin "3") (pinfunction "C_3") (pintype "passive"))
      (node (ref "R110") (pin "1") (pinfunction "1_1") (pintype "passive"))
      (node (ref "U32") (pin "1") (pinfunction "~{ON}_1") (pintype "passive"))
    )
    (net (code "80") (name "Net-(Q10-B)") (class "Default")
      (node (ref "Q10") (pin "1") (pinfunction "B_1") (pintype "passive"))
      (node (ref "R129") (pin "1") (pinfunction "1_1") (pintype "passive"))
    )
    (net (code "81") (name "Net-(Q10-C)") (class "Default")
      (node (ref "Q10") (pin "3") (pinfunction "C_3") (pintype "passive"))
      (node (ref "R127") (pin "1") (pinfunction "1_1") (pintype "passive"))
      (node (ref "U35") (pin "1") (pinfunction "~{ON}_1") (pintype "passive"))
    )
    (net (code "82") (name "Net-(Q11-B)") (class "Default")
      (node (ref "Q11") (pin "1") (pinfunction "B_1") (pintype "passive"))
      (node (ref "R130") (pin "1") (pinfunction "1_1") (pintype "passive"))
    )
    (net (code "83") (name "Net-(Q11-C)") (class "Default")
      (node (ref "Q11") (pin "3") (pinfunction "C_3") (pintype "passive"))
      (node (ref "R128") (pin "1") (pinfunction "1_1") (pintype "passive"))
      (node (ref "U36") (pin "1") (pinfunction "~{ON}_1") (pintype "passive"))
    )
    (net (code "84") (name "Net-(R11-Pad1)") (class "Default")
      (node (ref "R11") (pin "1") (pinfunction "1_1") (pintype "passive"))
      (node (ref "R18") (pin "2") (pinfunction "2_2") (pintype "passive"))
    )
    (net (code "85") (name "Net-(R12-Pad1)") (class "Default")
      (node (ref "R12") (pin "1") (pinfunction "1_1") (pintype "passive"))
      (node (ref "R17") (pin "2") (pinfunction "2_2") (pintype "passive"))
    )
    (net (code "86") (name "Net-(R20-Pad2)") (class "Default")
      (node (ref "R20") (pin "2") (pinfunction "2_2") (pintype "passive"))
      (node (ref "R37") (pin "2") (pinfunction "2_2") (pintype "passive"))
      (node (ref "U13") (pin "4") (pinfunction "NO_4") (pintype "passive"))
      (node (ref "U13") (pin "7") (pinfunction "NO_7") (pintype "passive"))
    )
    (net (code "87") (name "Net-(R23-Pad2)") (class "Default")
      (node (ref "R23") (pin "2") (pinfunction "2_2") (pintype "passive"))
      (node (ref "R27") (pin "2") (pinfunction "2_2") (pintype "passive"))
      (node (ref "R36") (pin "1") (pinfunction "1_1") (pintype "passive"))
    )
    (net (code "88") (name "Net-(R24-Pad2)") (class "Default")
      (node (ref "R24") (pin "2") (pinfunction "2_2") (pintype "passive"))
      (node (ref "R28") (pin "2") (pinfunction "2_2") (pintype "passive"))
      (node (ref "R41") (pin "2") (pinfunction "2_2") (pintype "passive"))
    )
    (net (code "89") (name "Net-(R25-Pad2)") (class "Default")
      (node (ref "R25") (pin "2") (pinfunction "2_2") (pintype "passive"))
      (node (ref "R29") (pin "1") (pinfunction "1_1") (pintype "passive"))
      (node (ref "R42") (pin "2") (pinfunction "2_2") (pintype "passive"))
    )
    (net (code "90") (name "Net-(R26-Pad2)") (class "Default")
      (node (ref "R26") (pin "2") (pinfunction "2_2") (pintype "passive"))
      (node (ref "R30") (pin "1") (pinfunction "1_1") (pintype "passive"))
      (node (ref "R38") (pin "1") (pinfunction "1_1") (pintype "passive"))
    )
    (net (code "91") (name "Net-(R36-Pad2)") (class "Default")
      (node (ref "R36") (pin "2") (pinfunction "2_2") (pintype "passive"))
      (node (ref "U13") (pin "2") (pinfunction "NC_2") (pintype "passive"))
      (node (ref "U13") (pin "9") (pinfunction "NC_9") (pintype "passive"))
    )
    (net (code "92") (name "Net-(R67-Pad1)") (class "Default")
      (node (ref "R67") (pin "1") (pinfunction "1_1") (pintype "passive"))
      (node (ref "R77") (pin "2") (pinfunction "2_2") (pintype "passive"))
    )
    (net (code "93") (name "Net-(R68-Pad1)") (class "Default")
      (node (ref "R68") (pin "1") (pinfunction "1_1") (pintype "passive"))
      (node (ref "R76") (pin "2") (pinfunction "2_2") (pintype "passive"))
    )
    (net (code "94") (name "Net-(R103-Pad1)") (class "Default")
      (node (ref "R103") (pin "1") (pinfunction "1_1") (pintype "passive"))
      (node (ref "R107") (pin "2") (pinfunction "2_2") (pintype "passive"))
    )
    (net (code "95") (name "Net-(R108-Pad1)") (class "Default")
      (node (ref "R108") (pin "1") (pinfunction "1_1") (pintype "passive"))
      (node (ref "R113") (pin "2") (pinfunction "2_2") (pintype "passive"))
    )
    (net (code "96") (name "Net-(U1A-G1)") (class "Default")
      (node (ref "R27") (pin "1") (pinfunction "1_1") (pintype "passive"))
      (node (ref "U1") (pin "2") (pinfunction "G1_2") (pintype "passive"))
      (node (ref "U1") (pin "4") (pinfunction "G2_4") (pintype "passive"))
    )
    (net (code "97") (name "Net-(U2A-G1)") (class "Default")
      (node (ref "R28") (pin "1") (pinfunction "1_1") (pintype "passive"))
      (node (ref "U2") (pin "2") (pinfunction "G1_2") (pintype "passive"))
      (node (ref "U2") (pin "4") (pinfunction "G2_4") (pintype "passive"))
    )
    (net (code "98") (name "Net-(U3A-G1)") (class "Default")
      (node (ref "R29") (pin "2") (pinfunction "2_2") (pintype "passive"))
      (node (ref "U3") (pin "2") (pinfunction "G1_2") (pintype "passive"))
      (node (ref "U3") (pin "4") (pinfunction "G2_4") (pintype "passive"))
    )
    (net (code "99") (name "Net-(U4A-G1)") (class "Default")
      (node (ref "R30") (pin "2") (pinfunction "2_2") (pintype "passive"))
      (node (ref "U4") (pin "2") (pinfunction "G1_2") (pintype "passive"))
      (node (ref "U4") (pin "4") (pinfunction "G2_4") (pintype "passive"))
    )
    (net (code "100") (name "Net-(U5-FB)") (class "Default")
      (node (ref "R17") (pin "1") (pinfunction "1_1") (pintype "passive"))
      (node (ref "R39") (pin "1") (pinfunction "1_1") (pintype "passive"))
      (node (ref "U5") (pin "5") (pinfunction "FB_5") (pintype "passive"))
    )
    (net (code "101") (name "Net-(U5-PG)") (class "Default")
      (node (ref "R16") (pin "2") (pinfunction "2_2") (pintype "passive"))
      (node (ref "U5") (pin "7") (pinfunction "PG_7") (pintype "passive"))
    )
    (net (code "102") (name "Net-(U5-SS{slash}TR)") (class "Default")
      (node (ref "C13") (pin "2") (pinfunction "2_2") (pintype "passive"))
      (node (ref "R18") (pin "1") (pinfunction "1_1") (pintype "passive"))
      (node (ref "R43") (pin "2") (pinfunction "2_2") (pintype "passive"))
      (node (ref "U5") (pin "9") (pinfunction "SS/TR_9") (pintype "passive"))
    )
    (net (code "103") (name "Net-(U5-SW)") (class "Default")
      (node (ref "L1") (pin "1") (pinfunction "1_1") (pintype "passive"))
      (node (ref "U5") (pin "2") (pinfunction "SW_2") (pintype "passive"))
    )
    (net (code "104") (name "Net-(U8-FB)") (class "Default")
      (node (ref "R19") (pin "2") (pinfunction "2_2") (pintype "passive"))
      (node (ref "R8") (pin "1") (pinfunction "1_1") (pintype "passive"))
      (node (ref "U8") (pin "5") (pinfunction "FB_5") (pintype "passive"))
    )
    (net (code "105") (name "Net-(U8-SS{slash}TRK)") (class "Default")
      (node (ref "C8") (pin "2") (pinfunction "2_2") (pintype "passive"))
      (node (ref "U8") (pin "6") (pinfunction "SS/TRK_6") (pintype "passive"))
    )
    (net (code "106") (name "Net-(U8-VIN)") (class "Default")
      (node (ref "C1") (pin "1") (pinfunction "1_1") (pintype "passive"))
      (node (ref "C2") (pin "1") (pinfunction "1_1") (pintype "passive"))
      (node (ref "C5") (pin "2") (pinfunction "2_2") (pintype "passive"))
      (node (ref "J2") (pin "2") (pinfunction "2_2") (pintype "passive"))
      (node (ref "U8") (pin "1") (pinfunction "VIN_1") (pintype "passive"))
    )
    (net (code "107") (name "Net-(U9--IN)") (class "Default")
      (node (ref "R13") (pin "1") (pinfunction "1_1") (pintype "passive"))
      (node (ref "U9") (pin "3") (pinfunction "-IN_3") (pintype "passive"))
    )
    (net (code "108") (name "Net-(U9-OUT)") (class "Default")
      (node (ref "R21") (pin "1") (pinfunction "1_1") (pintype "passive"))
      (node (ref "R32") (pin "2") (pinfunction "2_2") (pintype "passive"))
      (node (ref "U9") (pin "1") (pinfunction "OUT_1") (pintype "passive"))
    )
    (net (code "109") (name "Net-(U9-V-)") (class "Default")
      (node (ref "R33") (pin "2") (pinfunction "2_2") (pintype "passive"))
      (node (ref "U9") (pin "2") (pinfunction "V-_2") (pintype "passive"))
    )
    (net (code "110") (name "Net-(U10-+IN)") (class "Default")
      (node (ref "J3") (pin "1") (pinfunction "1_1") (pintype "passive"))
      (node (ref "R3") (pin "2") (pinfunction "2_2") (pintype "passive"))
      (node (ref "R7") (pin "2") (pinfunction "2_2") (pintype "passive"))
      (node (ref "U10") (pin "4") (pinfunction "+IN_4") (pintype "passive"))
    )
    (net (code "111") (name "Net-(U10--IN)") (class "Default")
      (node (ref "R15") (pin "1") (pinfunction "1_1") (pintype "passive"))
      (node (ref "U10") (pin "3") (pinfunction "-IN_3") (pintype "passive"))
    )
    (net (code "112") (name "Net-(U10-OUT)") (class "Default")
      (node (ref "R22") (pin "1") (pinfunction "1_1") (pintype "passive"))
      (node (ref "R34") (pin "2") (pinfunction "2_2") (pintype "passive"))
      (node (ref "U10") (pin "1") (pinfunction "OUT_1") (pintype "passive"))
    )
    (net (code "113") (name "Net-(U10-V-)") (class "Default")
      (node (ref "R35") (pin "1") (pinfunction "1_1") (pintype "passive"))
      (node (ref "U10") (pin "2") (pinfunction "V-_2") (pintype "passive"))
    )
    (net (code "114") (name "Net-(U11-GATE)") (class "Default")
      (node (ref "C14") (pin "1") (pinfunction "1_1") (pintype "passive"))
      (node (ref "U11") (pin "7") (pinfunction "GATE_7") (pintype "passive"))
      (node (ref "U6") (pin "1") (pinfunction "G_1") (pintype "passive"))
    )
    (net (code "115") (name "Net-(U11-SENSE)") (class "Default")
      (node (ref "R4") (pin "2") (pinfunction "2_2") (pintype "passive"))
      (node (ref "R9") (pin "2") (pinfunction "2_2") (pintype "passive"))
      (node (ref "U11") (pin "6") (pinfunction "SENSE_6") (pintype "passive"))
      (node (ref "U6") (pin "3") (pinfunction "D_3") (pintype "passive"))
    )
    (net (code "116") (name "Net-(U12-GATE)") (class "Default")
      (node (ref "C15") (pin "1") (pinfunction "1_1") (pintype "passive"))
      (node (ref "U12") (pin "7") (pinfunction "GATE_7") (pintype "passive"))
      (node (ref "U7") (pin "1") (pinfunction "G_1") (pintype "passive"))
    )
    (net (code "117") (name "Net-(U12-SENSE)") (class "Default")
      (node (ref "R10") (pin "2") (pinfunction "2_2") (pintype "passive"))
      (node (ref "R5") (pin "2") (pinfunction "2_2") (pintype "passive"))
      (node (ref "U12") (pin "6") (pinfunction "SENSE_6") (pintype "passive"))
      (node (ref "U7") (pin "3") (pinfunction "D_3") (pintype "passive"))
    )
    (net (code "118") (name "Net-(U14-D)") (class "Default")
      (node (ref "R56") (pin "2") (pinfunction "2_2") (pintype "passive"))
      (node (ref "R61") (pin "2") (pinfunction "2_2") (pintype "passive"))
      (node (ref "U14") (pin "3") (pinfunction "D_3") (pintype "passive"))
      (node (ref "U20") (pin "6") (pinfunction "SENSE_6") (pintype "passive"))
    )
    (net (code "119") (name "Net-(U14-G)") (class "Default")
      (node (ref "C30") (pin "1") (pinfunction "1_1") (pintype "passive"))
      (node (ref "U14") (pin "1") (pinfunction "G_1") (pintype "passive"))
      (node (ref "U20") (pin "7") (pinfunction "GATE_7") (pintype "passive"))
    )
    (net (code "120") (name "Net-(U15-D)") (class "Default")
      (node (ref "R57") (pin "2") (pinfunction "2_2") (pintype "passive"))
      (node (ref "R62") (pin "2") (pinfunction "2_2") (pintype "passive"))
      (node (ref "U15") (pin "3") (pinfunction "D_3") (pintype "passive"))
      (node (ref "U21") (pin "6") (pinfunction "SENSE_6") (pintype "passive"))
    )
    (net (code "121") (name "Net-(U15-G)") (class "Default")
      (node (ref "C31") (pin "1") (pinfunction "1_1") (pintype "passive"))
      (node (ref "U15") (pin "1") (pinfunction "G_1") (pintype "passive"))
      (node (ref "U21") (pin "7") (pinfunction "GATE_7") (pintype "passive"))
    )
    (net (code "122") (name "Net-(U16-D)") (class "Default")
      (node (ref "R58") (pin "2") (pinfunction "2_2") (pintype "passive"))
      (node (ref "R63") (pin "2") (pinfunction "2_2") (pintype "passive"))
      (node (ref "U16") (pin "3") (pinfunction "D_3") (pintype "passive"))
      (node (ref "U22") (pin "6") (pinfunction "SENSE_6") (pintype "passive"))
    )
    (net (code "123") (name "Net-(U16-G)") (class "Default")
      (node (ref "C32") (pin "1") (pinfunction "1_1") (pintype "passive"))
      (node (ref "U16") (pin "1") (pinfunction "G_1") (pintype "passive"))
      (node (ref "U22") (pin "7") (pinfunction "GATE_7") (pintype "passive"))
    )
    (net (code "124") (name "Net-(U17-FB)") (class "Default")
      (node (ref "R60") (pin "1") (pinfunction "1_1") (pintype "passive"))
      (node (ref "R71") (pin "2") (pinfunction "2_2") (pintype "passive"))
      (node (ref "U17") (pin "5") (pinfunction "FB_5") (pintype "passive"))
    )
    (net (code "125") (name "Net-(U17-SS{slash}TRK)") (class "Default")
      (node (ref "C24") (pin "2") (pinfunction "2_2") (pintype "passive"))
      (node (ref "U17") (pin "6") (pinfunction "SS/TRK_6") (pintype "passive"))
    )
    (net (code "126") (name "Net-(U17-VIN)") (class "Default")
      (node (ref "C16") (pin "1") (pinfunction "1_1") (pintype "passive"))
      (node (ref "C17") (pin "1") (pinfunction "1_1") (pintype "passive"))
      (node (ref "C21") (pin "2") (pinfunction "2_2") (pintype "passive"))
      (node (ref "J7") (pin "2") (pinfunction "2_2") (pintype "passive"))
      (node (ref "U17") (pin "1") (pinfunction "VIN_1") (pintype "passive"))
    )
    (net (code "127") (name "Net-(U18-FB)") (class "Default")
      (node (ref "R76") (pin "1") (pinfunction "1_1") (pintype "passive"))
      (node (ref "R83") (pin "1") (pinfunction "1_1") (pintype "passive"))
      (node (ref "U18") (pin "5") (pinfunction "FB_5") (pintype "passive"))
    )
    (net (code "128") (name "Net-(U18-PG)") (class "Default")
      (node (ref "R69") (pin "2") (pinfunction "2_2") (pintype "passive"))
      (node (ref "U18") (pin "7") (pinfunction "PG_7") (pintype "passive"))
    )
    (net (code "129") (name "Net-(U18-SS{slash}TR)") (class "Default")
      (node (ref "C29") (pin "2") (pinfunction "2_2") (pintype "passive"))
      (node (ref "R77") (pin "1") (pinfunction "1_1") (pintype "passive"))
      (node (ref "R84") (pin "2") (pinfunction "2_2") (pintype "passive"))
      (node (ref "U18") (pin "9") (pinfunction "SS/TR_9") (pintype "passive"))
    )
    (net (code "130") (name "Net-(U18-SW)") (class "Default")
      (node (ref "L2") (pin "1") (pinfunction "1_1") (pintype "passive"))
      (node (ref "U18") (pin "2") (pinfunction "SW_2") (pintype "passive"))
    )
    (net (code "131") (name "Net-(U19-+IN)") (class "Default")
      (node (ref "J8") (pin "1") (pinfunction "1_1") (pintype "passive"))
      (node (ref "R55") (pin "2") (pinfunction "2_2") (pintype "passive"))
      (node (ref "R59") (pin "2") (pinfunction "2_2") (pintype "passive"))
      (node (ref "U19") (pin "4") (pinfunction "+IN_4") (pintype "passive"))
    )
    (net (code "132") (name "Net-(U19--IN)") (class "Default")
      (node (ref "R66") (pin "1") (pinfunction "1_1") (pintype "passive"))
      (node (ref "U19") (pin "3") (pinfunction "-IN_3") (pintype "passive"))
    )
    (net (code "133") (name "Net-(U19-OUT)") (class "Default")
      (node (ref "R73") (pin "1") (pinfunction "1_1") (pintype "passive"))
      (node (ref "R78") (pin "2") (pinfunction "2_2") (pintype "passive"))
      (node (ref "U19") (pin "1") (pinfunction "OUT_1") (pintype "passive"))
    )
    (net (code "134") (name "Net-(U19-V-)") (class "Default")
      (node (ref "R79") (pin "1") (pinfunction "1_1") (pintype "passive"))
      (node (ref "U19") (pin "2") (pinfunction "V-_2") (pintype "passive"))
    )
    (net (code "135") (name "Net-(U23--IN)") (class "Default")
      (node (ref "F1") (pin "2") (pinfunction "2_2") (pintype "passive"))
      (node (ref "R87") (pin "1") (pinfunction "1_1") (pintype "passive"))
      (node (ref "R88") (pin "1") (pinfunction "1_1") (pintype "passive"))
      (node (ref "U23") (pin "1") (pinfunction "-IN_1") (pintype "passive"))
    )
    (net (code "136") (name "Net-(U23-GND)") (class "Default")
      (node (ref "R93") (pin "2") (pinfunction "2_2") (pintype "passive"))
      (node (ref "U23") (pin "2") (pinfunction "GND_2") (pintype "passive"))
      (node (ref "U23") (pin "3") (pinfunction "REF2_3") (pintype "passive"))
      (node (ref "U23") (pin "4") (pinfunction "NC_4") (pintype "passive"))
    )
    (net (code "137") (name "Net-(U23-OUT)") (class "Default")
      (node (ref "R75") (pin "1") (pinfunction "1_1") (pintype "passive"))
      (node (ref "U23") (pin "5") (pinfunction "OUT_5") (pintype "passive"))
    )
    (net (code "138") (name "Net-(U24-D)") (class "Default")
      (node (ref "R90") (pin "2") (pinfunction "2_2") (pintype "passive"))
      (node (ref "R96") (pin "2") (pinfunction "2_2") (pintype "passive"))
      (node (ref "U24") (pin "3") (pinfunction "D_3") (pintype "passive"))
      (node (ref "U30") (pin "6") (pinfunction "SENSE_6") (pintype "passive"))
    )
    (net (code "139") (name "Net-(U24-G)") (class "Default")
      (node (ref "C48") (pin "1") (pinfunction "1_1") (pintype "passive"))
      (node (ref "U24") (pin "1") (pinfunction "G_1") (pintype "passive"))
      (node (ref "U30") (pin "7") (pinfunction "GATE_7") (pintype "passive"))
    )
    (net (code "140") (name "Net-(U25-D)") (class "Default")
      (node (ref "R91") (pin "2") (pinfunction "2_2") (pintype "passive"))
      (node (ref "R97") (pin "2") (pinfunction "2_2") (pintype "passive"))
      (node (ref "U25") (pin "3") (pinfunction "D_3") (pintype "passive"))
      (node (ref "U31") (pin "6") (pinfunction "SENSE_6") (pintype "passive"))
    )
    (net (code "141") (name "Net-(U25-G)") (class "Default")
      (node (ref "C49") (pin "1") (pinfunction "1_1") (pintype "passive"))
      (node (ref "U25") (pin "1") (pinfunction "G_1") (pintype "passive"))
      (node (ref "U31") (pin "7") (pinfunction "GATE_7") (pintype "passive"))
    )
    (net (code "142") (name "Net-(U26-D)") (class "Default")
      (node (ref "R92") (pin "2") (pinfunction "2_2") (pintype "passive"))
      (node (ref "R98") (pin "2") (pinfunction "2_2") (pintype "passive"))
      (node (ref "U26") (pin "3") (pinfunction "D_3") (pintype "passive"))
      (node (ref "U32") (pin "6") (pinfunction "SENSE_6") (pintype "passive"))
    )
    (net (code "143") (name "Net-(U26-G)") (class "Default")
      (node (ref "C50") (pin "1") (pinfunction "1_1") (pintype "passive"))
      (node (ref "U26") (pin "1") (pinfunction "G_1") (pintype "passive"))
      (node (ref "U32") (pin "7") (pinfunction "GATE_7") (pintype "passive"))
    )
    (net (code "144") (name "Net-(U27-BST1)") (class "Default")
      (node (ref "C34") (pin "1") (pinfunction "1_1") (pintype "passive"))
      (node (ref "U27") (pin "23") (pinfunction "BST1_23") (pintype "passive"))
    )
    (net (code "145") (name "Net-(U27-BST2)") (class "Default")
      (node (ref "C35") (pin "1") (pinfunction "1_1") (pintype "passive"))
      (node (ref "U27") (pin "28") (pinfunction "BST2_28") (pintype "passive"))
    )
    (net (code "146") (name "Net-(U27-FB)") (class "Default")
      (node (ref "R113") (pin "1") (pinfunction "1_1") (pintype "passive"))
      (node (ref "R119") (pin "1") (pinfunction "1_1") (pintype "passive"))
      (node (ref "U27") (pin "9") (pinfunction "FB_9") (pintype "passive"))
    )
    (net (code "147") (name "Net-(U27-MPPC)") (class "Default")
      (node (ref "R107") (pin "1") (pinfunction "1_1") (pintype "passive"))
      (node (ref "R116") (pin "2") (pinfunction "2_2") (pintype "passive"))
      (node (ref "R118") (pin "1") (pinfunction "1_1") (pintype "passive"))
      (node (ref "U27") (pin "12") (pinfunction "MPPC_12") (pintype "passive"))
    )
    (net (code "148") (name "Net-(U27-PGOOD)") (class "Default")
      (node (ref "R111") (pin "2") (pinfunction "2_2") (pintype "passive"))
      (node (ref "U27") (pin "7") (pinfunction "PGOOD_7") (pintype "passive"))
    )
    (net (code "149") (name "Net-(U27-RT)") (class "Default")
      (node (ref "R117") (pin "2") (pinfunction "2_2") (pintype "passive"))
      (node (ref "U27") (pin "14") (pinfunction "RT_14") (pintype "passive"))
    )
    (net (code "150") (name "Net-(U27-SVcc)") (class "Default")
      (node (ref "C53") (pin "1") (pinfunction "1_1") (pintype "passive"))
      (node (ref "R111") (pin "1") (pinfunction "1_1") (pintype "passive"))
      (node (ref "U27") (pin "13") (pinfunction "Vcc_13") (pintype "passive"))
      (node (ref "U27") (pin "8") (pinfunction "SVcc_8") (pintype "passive"))
    )
    (net (code "151") (name "Net-(U27-VC)") (class "Default")
      (node (ref "R112") (pin "2") (pinfunction "2_2") (pintype "passive"))
      (node (ref "U27") (pin "10") (pinfunction "VC_10") (pintype "passive"))
    )
    (net (code "152") (name "Net-(U28-FB)") (class "Default")
      (node (ref "R101") (pin "2") (pinfunction "2_2") (pintype "passive"))
      (node (ref "R95") (pin "1") (pinfunction "1_1") (pintype "passive"))
      (node (ref "U28") (pin "5") (pinfunction "FB_5") (pintype "passive"))
    )
    (net (code "153") (name "Net-(U28-SS{slash}TRK)") (class "Default")
      (node (ref "C45") (pin "2") (pinfunction "2_2") (pintype "passive"))
      (node (ref "U28") (pin "6") (pinfunction "SS/TRK_6") (pintype "passive"))
    )
    (net (code "154") (name "Net-(U28-VIN)") (class "Default")
      (node (ref "C37") (pin "1") (pinfunction "1_1") (pintype "passive"))
      (node (ref "C38") (pin "1") (pinfunction "1_1") (pintype "passive"))
      (node (ref "C42") (pin "2") (pinfunction "2_2") (pintype "passive"))
      (node (ref "J11") (pin "2") (pinfunction "2_2") (pintype "passive"))
      (node (ref "U28") (pin "1") (pinfunction "VIN_1") (pintype "passive"))
    )
    (net (code "155") (name "Net-(U29-+IN)") (class "Default")
      (node (ref "J12") (pin "1") (pinfunction "1_1") (pintype "passive"))
      (node (ref "R89") (pin "2") (pinfunction "2_2") (pintype "passive"))
      (node (ref "R94") (pin "2") (pinfunction "2_2") (pintype "passive"))
      (node (ref "U29") (pin "4") (pinfunction "+IN_4") (pintype "passive"))
    )
    (net (code "156") (name "Net-(U29--IN)") (class "Default")
      (node (ref "R100") (pin "1") (pinfunction "1_1") (pintype "passive"))
      (node (ref "U29") (pin "3") (pinfunction "-IN_3") (pintype "passive"))
    )
    (net (code "157") (name "Net-(U29-OUT)") (class "Default")
      (node (ref "R102") (pin "1") (pinfunction "1_1") (pintype "passive"))
      (node (ref "R105") (pin "2") (pinfunction "2_2") (pintype "passive"))
      (node (ref "U29") (pin "1") (pinfunction "OUT_1") (pintype "passive"))
    )
    (net (code "158") (name "Net-(U29-V-)") (class "Default")
      (node (ref "R106") (pin "1") (pinfunction "1_1") (pintype "passive"))
      (node (ref "U29") (pin "2") (pinfunction "V-_2") (pintype "passive"))
    )
    (net (code "159") (name "Net-(U33-D)") (class "Default")
      (node (ref "R120") (pin "2") (pinfunction "2_2") (pintype "passive"))
      (node (ref "R122") (pin "2") (pinfunction "2_2") (pintype "passive"))
      (node (ref "U33") (pin "3") (pinfunction "D_3") (pintype "passive"))
      (node (ref "U35") (pin "6") (pinfunction "SENSE_6") (pintype "passive"))
    )
    (net (code "160") (name "Net-(U33-G)") (class "Default")
      (node (ref "C60") (pin "1") (pinfunction "1_1") (pintype "passive"))
      (node (ref "U33") (pin "1") (pinfunction "G_1") (pintype "passive"))
      (node (ref "U35") (pin "7") (pinfunction "GATE_7") (pintype "passive"))
    )
    (net (code "161") (name "Net-(U34-D)") (class "Default")
      (node (ref "R121") (pin "2") (pinfunction "2_2") (pintype "passive"))
      (node (ref "R123") (pin "2") (pinfunction "2_2") (pintype "passive"))
      (node (ref "U34") (pin "3") (pinfunction "D_3") (pintype "passive"))
      (node (ref "U36") (pin "6") (pinfunction "SENSE_6") (pintype "passive"))
    )
    (net (code "162") (name "Net-(U34-G)") (class "Default")
      (node (ref "C61") (pin "1") (pinfunction "1_1") (pintype "passive"))
      (node (ref "U34") (pin "1") (pinfunction "G_1") (pintype "passive"))
      (node (ref "U36") (pin "7") (pinfunction "GATE_7") (pintype "passive"))
    )
    (net (code "163") (name "unconnected-(BAT-Pad4)") (class "Default")
      (node (ref "BAT") (pin "4") (pinfunction "4_4") (pintype "passive+no_connect"))
    )
    (net (code "164") (name "unconnected-(D1-Pad1)") (class "Default")
      (node (ref "D1") (pin "1") (pinfunction "1_1") (pintype "passive+no_connect"))
    )
    (net (code "165") (name "unconnected-(D5-Pad1)") (class "Default")
      (node (ref "D5") (pin "1") (pinfunction "1_1") (pintype "passive+no_connect"))
    )
    (net (code "166") (name "unconnected-(D7-Pad1)") (class "Default")
      (node (ref "D7") (pin "1") (pinfunction "1_1") (pintype "passive+no_connect"))
    )
    (net (code "167") (name "unconnected-(J14-+3.3V-Pad1)") (class "Default")
      (node (ref "J14") (pin "1") (pinfunction "+3.3V_1") (pintype "passive+no_connect"))
    )
    (net (code "168") (name "unconnected-(J14-+3.3V-Pad2)") (class "Default")
      (node (ref "J14") (pin "2") (pinfunction "+3.3V_2") (pintype "passive+no_connect"))
    )
    (net (code "169") (name "unconnected-(J14-+5V-Pad51)") (class "Default")
      (node (ref "J14") (pin "51") (pinfunction "+5V_51") (pintype "passive+no_connect"))
    )
    (net (code "170") (name "unconnected-(J14-+5V-Pad52)") (class "Default")
      (node (ref "J14") (pin "52") (pinfunction "+5V_52") (pintype "passive+no_connect"))
    )
    (net (code "171") (name "unconnected-(J14-ASL1-Pad29)") (class "Default")
      (node (ref "J14") (pin "29") (pinfunction "ASL1_29") (pintype "passive+no_connect"))
    )
    (net (code "172") (name "unconnected-(J14-ASL2-Pad31)") (class "Default")
      (node (ref "J14") (pin "31") (pinfunction "ASL2_31") (pintype "passive+no_connect"))
    )
    (net (code "173") (name "unconnected-(J14-ASL3-Pad33)") (class "Default")
      (node (ref "J14") (pin "33") (pinfunction "ASL3_33") (pintype "passive+no_connect"))
    )
    (net (code "174") (name "unconnected-(J14-CLK1-Pad10)") (class "Default")
      (node (ref "J14") (pin "10") (pinfunction "CLK1_10") (pintype "passive+no_connect"))
    )
    (net (code "175") (name "unconnected-(J14-CLK2-Pad45)") (class "Default")
      (node (ref "J14") (pin "45") (pinfunction "CLK2_45") (pintype "passive+no_connect"))
    )
    (net (code "176") (name "unconnected-(J14-CS1-Pad46)") (class "Default")
      (node (ref "J14") (pin "46") (pinfunction "CS1_46") (pintype "passive+no_connect"))
    )
    (net (code "177") (name "unconnected-(J14-CS2-Pad44)") (class "Default")
      (node (ref "J14") (pin "44") (pinfunction "CS2_44") (pintype "passive+no_connect"))
    )
    (net (code "178") (name "unconnected-(J14-CS3-Pad42)") (class "Default")
      (node (ref "J14") (pin "42") (pinfunction "CS3_42") (pintype "passive+no_connect"))
    )
    (net (code "179") (name "unconnected-(J14-CS4-Pad40)") (class "Default")
      (node (ref "J14") (pin "40") (pinfunction "CS4_40") (pintype "passive+no_connect"))
    )
    (net (code "180") (name "unconnected-(J14-CS5-Pad38)") (class "Default")
      (node (ref "J14") (pin "38") (pinfunction "CS5_38") (pintype "passive+no_connect"))
    )
    (net (code "181") (name "unconnected-(J14-CS6-Pad36)") (class "Default")
      (node (ref "J14") (pin "36") (pinfunction "CS6_36") (pintype "passive+no_connect"))
    )
    (net (code "182") (name "unconnected-(J14-CS7-Pad34)") (class "Default")
      (node (ref "J14") (pin "34") (pinfunction "CS7_34") (pintype "passive+no_connect"))
    )
    (net (code "183") (name "unconnected-(J14-CS8-Pad32)") (class "Default")
      (node (ref "J14") (pin "32") (pinfunction "CS8_32") (pintype "passive+no_connect"))
    )
    (net (code "184") (name "unconnected-(J14-CS9-Pad30)") (class "Default")
      (node (ref "J14") (pin "30") (pinfunction "CS9_30") (pintype "passive+no_connect"))
    )
    (net (code "185") (name "unconnected-(J14-DL1-Pad35)") (class "Default")
      (node (ref "J14") (pin "35") (pinfunction "DL1_35") (pintype "passive+no_connect"))
    )
    (net (code "186") (name "unconnected-(J14-DL2-Pad18)") (class "Default")
      (node (ref "J14") (pin "18") (pinfunction "DL2_18") (pintype "passive+no_connect"))
    )
    (net (code "187") (name "unconnected-(J14-MISO1-Pad6)") (class "Default")
      (node (ref "J14") (pin "6") (pinfunction "MISO1_6") (pintype "passive+no_connect"))
    )
    (net (code "188") (name "unconnected-(J14-MISO2-Pad41)") (class "Default")
      (node (ref "J14") (pin "41") (pinfunction "MISO2_41") (pintype "passive+no_connect"))
    )
    (net (code "189") (name "unconnected-(J14-MOSI1-Pad8)") (class "Default")
      (node (ref "J14") (pin "8") (pinfunction "MOSI1_8") (pintype "passive+no_connect"))
    )
    (net (code "190") (name "unconnected-(J14-MOSI2-Pad43)") (class "Default")
      (node (ref "J14") (pin "43") (pinfunction "MOSI2_43") (pintype "passive+no_connect"))
    )
    (net (code "191") (name "unconnected-(J14-NA-Pad20)") (class "Default")
      (node (ref "J14") (pin "20") (pinfunction "NA_20") (pintype "passive+no_connect"))
    )
    (net (code "192") (name "unconnected-(J14-NA-Pad27)") (class "Default")
      (node (ref "J14") (pin "27") (pinfunction "NA_27") (pintype "passive+no_connect"))
    )
    (net (code "193") (name "unconnected-(J14-NA-Pad48)") (class "Default")
      (node (ref "J14") (pin "48") (pinfunction "NA_48") (pintype "passive+no_connect"))
    )
    (net (code "194") (name "unconnected-(J14-PWRL0-Pad5)") (class "Default")
      (node (ref "J14") (pin "5") (pinfunction "PWRL0_5") (pintype "passive+no_connect"))
    )
    (net (code "195") (name "unconnected-(J14-PWRL1-Pad7)") (class "Default")
      (node (ref "J14") (pin "7") (pinfunction "PWRL1_7") (pintype "passive+no_connect"))
    )
    (net (code "196") (name "unconnected-(J14-PWRL2-Pad9)") (class "Default")
      (node (ref "J14") (pin "9") (pinfunction "PWRL2_9") (pintype "passive+no_connect"))
    )
    (net (code "197") (name "unconnected-(J14-PWRL3-Pad11)") (class "Default")
      (node (ref "J14") (pin "11") (pinfunction "PWRL3_11") (pintype "passive+no_connect"))
    )
    (net (code "198") (name "unconnected-(J14-PWRL4-Pad13)") (class "Default")
      (node (ref "J14") (pin "13") (pinfunction "PWRL4_13") (pintype "passive+no_connect"))
    )
    (net (code "199") (name "unconnected-(J14-PWRL5-Pad15)") (class "Default")
      (node (ref "J14") (pin "15") (pinfunction "PWRL5_15") (pintype "passive+no_connect"))
    )
    (net (code "200") (name "unconnected-(J14-PWRL6-Pad17)") (class "Default")
      (node (ref "J14") (pin "17") (pinfunction "PWRL6_17") (pintype "passive+no_connect"))
    )
    (net (code "201") (name "unconnected-(J14-PWRL7-Pad19)") (class "Default")
      (node (ref "J14") (pin "19") (pinfunction "PWRL7_19") (pintype "passive+no_connect"))
    )
    (net (code "202") (name "unconnected-(J14-PWRL8-Pad21)") (class "Default")
      (node (ref "J14") (pin "21") (pinfunction "PWRL8_21") (pintype "passive+no_connect"))
    )
    (net (code "203") (name "unconnected-(J14-PWRL9-Pad23)") (class "Default")
      (node (ref "J14") (pin "23") (pinfunction "PWRL9_23") (pintype "passive+no_connect"))
    )
    (net (code "204") (name "unconnected-(J14-PWRL10-Pad25)") (class "Default")
      (node (ref "J14") (pin "25") (pinfunction "PWRL10_25") (pintype "passive"))
    )
    (net (code "205") (name "unconnected-(J14-RST-Pad39)") (class "Default")
      (node (ref "J14") (pin "39") (pinfunction "RST_39") (pintype "passive+no_connect"))
    )
    (net (code "206") (name "unconnected-(J14-SS1-Pad12)") (class "Default")
      (node (ref "J14") (pin "12") (pinfunction "SS1_12") (pintype "passive+no_connect"))
    )
    (net (code "207") (name "unconnected-(J14-SS2-Pad47)") (class "Default")
      (node (ref "J14") (pin "47") (pinfunction "SS2_47") (pintype "passive+no_connect"))
    )
    (net (code "208") (name "unconnected-(J14-SYNC-Pad14)") (class "Default")
      (node (ref "J14") (pin "14") (pinfunction "SYNC_14") (pintype "passive+no_connect"))
    )
    (net (code "209") (name "unconnected-(J19-3.3V-Pad3)") (class "Default")
      (node (ref "J19") (pin "3") (pinfunction "3.3V_3") (pintype "passive+no_connect"))
    )
    (net (code "210") (name "unconnected-(J19-3.3V-Pad4)") (class "Default")
      (node (ref "J19") (pin "4") (pinfunction "3.3V_4") (pintype "passive+no_connect"))
    )
    (net (code "211") (name "unconnected-(J19-3.3V-Pad6)") (class "Default")
      (node (ref "J19") (pin "6") (pinfunction "3.3V_6") (pintype "passive+no_connect"))
    )
    (net (code "212") (name "unconnected-(J19-3.3V-Pad33)") (class "Default")
      (node (ref "J19") (pin "33") (pinfunction "3.3V_33") (pintype "passive+no_connect"))
    )
    (net (code "213") (name "unconnected-(J19-MCAL1-Pad17)") (class "Default")
      (node (ref "J19") (pin "17") (pinfunction "MCAL1_17") (pintype "passive+no_connect"))
    )
    (net (code "214") (name "unconnected-(J19-MCAL2-Pad19)") (class "Default")
      (node (ref "J19") (pin "19") (pinfunction "MCAL2_19") (pintype "passive+no_connect"))
    )
    (net (code "215") (name "unconnected-(J19-MHB1-Pad29)") (class "Default")
      (node (ref "J19") (pin "29") (pinfunction "MHB1_29") (pintype "passive+no_connect"))
    )
    (net (code "216") (name "unconnected-(J19-MHB2-Pad31)") (class "Default")
      (node (ref "J19") (pin "31") (pinfunction "MHB2_31") (pintype "passive+no_connect"))
    )
    (net (code "217") (name "unconnected-(J19-MPWRCTRL1-Pad21)") (class "Default")
      (node (ref "J19") (pin "21") (pinfunction "MPWRCTRL1_21") (pintype "passive+no_connect"))
    )
    (net (code "218") (name "unconnected-(J19-MPWRCTRL2-Pad23)") (class "Default")
      (node (ref "J19") (pin "23") (pinfunction "MPWRCTRL2_23") (pintype "passive+no_connect"))
    )
    (net (code "219") (name "unconnected-(J19-NA-Pad1)") (class "Default")
      (node (ref "J19") (pin "1") (pinfunction "NA_1") (pintype "passive+no_connect"))
    )
    (net (code "220") (name "unconnected-(J19-NA-Pad2)") (class "Default")
      (node (ref "J19") (pin "2") (pinfunction "NA_2") (pintype "passive+no_connect"))
    )
    (net (code "221") (name "unconnected-(J19-NA-Pad32)") (class "Default")
      (node (ref "J19") (pin "32") (pinfunction "NA_32") (pintype "passive+no_connect"))
    )
    (net (code "222") (name "unconnected-(J19-NA-Pad34)") (class "Default")
      (node (ref "J19") (pin "34") (pinfunction "NA_34") (pintype "passive+no_connect"))
    )
    (net (code "223") (name "unconnected-(J19-NA-Pad36)") (class "Default")
      (node (ref "J19") (pin "36") (pinfunction "NA_36") (pintype "passive+no_connect"))
    )
    (net (code "224") (name "unconnected-(J19-NA-Pad39)") (class "Default")
      (node (ref "J19") (pin "39") (pinfunction "NA_39") (pintype "passive+no_connect"))
    )
    (net (code "225") (name "unconnected-(J19-NA-Pad40)") (class "Default")
      (node (ref "J19") (pin "40") (pinfunction "NA_40") (pintype "passive+no_connect"))
    )
    (net (code "226") (name "unconnected-(J19-PAL-Pad13)") (class "Default")
      (node (ref "J19") (pin "13") (pinfunction "PAL_13") (pintype "passive+no_connect"))
    )
    (net (code "227") (name "unconnected-(J19-PAL1-Pad11)") (class "Default")
      (node (ref "J19") (pin "11") (pinfunction "PAL1_11") (pintype "passive+no_connect"))
    )
    (net (code "228") (name "unconnected-(J19-PSEL1-Pad5)") (class "Default")
      (node (ref "J19") (pin "5") (pinfunction "PSEL1_5") (pintype "passive+no_connect"))
    )
    (net (code "229") (name "unconnected-(J19-PSEL2-Pad7)") (class "Default")
      (node (ref "J19") (pin "7") (pinfunction "PSEL2_7") (pintype "passive+no_connect"))
    )
    (net (code "230") (name "unconnected-(J19-PSEL3-Pad9)") (class "Default")
      (node (ref "J19") (pin "9") (pinfunction "PSEL3_9") (pintype "passive+no_connect"))
    )
    (net (code "231") (name "unconnected-(J19-PWRCTRL0-Pad10)") (class "Default")
      (node (ref "J19") (pin "10") (pinfunction "PWRCTRL0_10") (pintype "passive+no_connect"))
    )
    (net (code "232") (name "unconnected-(J19-PWRCTRL1-Pad12)") (class "Default")
      (node (ref "J19") (pin "12") (pinfunction "PWRCTRL1_12") (pintype "passive+no_connect"))
    )
    (net (code "233") (name "unconnected-(J19-PWRCTRL2-Pad14)") (class "Default")
      (node (ref "J19") (pin "14") (pinfunction "PWRCTRL2_14") (pintype "passive+no_connect"))
    )
    (net (code "234") (name "unconnected-(J19-PWRCTRL3-Pad16)") (class "Default")
      (node (ref "J19") (pin "16") (pinfunction "PWRCTRL3_16") (pintype "passive+no_connect"))
    )
    (net (code "235") (name "unconnected-(J19-PWRCTRL4-Pad18)") (class "Default")
      (node (ref "J19") (pin "18") (pinfunction "PWRCTRL4_18") (pintype "passive+no_connect"))
    )
    (net (code "236") (name "unconnected-(J19-PWRCTRL5-Pad20)") (class "Default")
      (node (ref "J19") (pin "20") (pinfunction "PWRCTRL5_20") (pintype "passive+no_connect"))
    )
    (net (code "237") (name "unconnected-(J19-PWRCTRL6-Pad22)") (class "Default")
      (node (ref "J19") (pin "22") (pinfunction "PWRCTRL6_22") (pintype "passive+no_connect"))
    )
    (net (code "238") (name "unconnected-(J19-PWRCTRL7-Pad24)") (class "Default")
      (node (ref "J19") (pin "24") (pinfunction "PWRCTRL7_24") (pintype "passive+no_connect"))
    )
    (net (code "239") (name "unconnected-(J19-PWRCTRL8-Pad26)") (class "Default")
      (node (ref "J19") (pin "26") (pinfunction "PWRCTRL8_26") (pintype "passive+no_connect"))
    )
    (net (code "240") (name "unconnected-(J19-PWRCTRL9-Pad28)") (class "Default")
      (node (ref "J19") (pin "28") (pinfunction "PWRCTRL9_28") (pintype "passive+no_connect"))
    )
    (net (code "241") (name "unconnected-(J19-PWRCTRL10-Pad30)") (class "Default")
      (node (ref "J19") (pin "30") (pinfunction "PWRCTRL10_30") (pintype "passive+no_connect"))
    )
    (net (code "242") (name "unconnected-(J19-PWR_RST-Pad15)") (class "Default")
      (node (ref "J19") (pin "15") (pinfunction "PWR_RST_15") (pintype "passive+no_connect"))
    )
    (net (code "243") (name "unconnected-(J19-SPSI1-Pad25)") (class "Default")
      (node (ref "J19") (pin "25") (pinfunction "SPSI1_25") (pintype "passive+no_connect"))
    )
    (net (code "244") (name "unconnected-(J19-SPSI2-Pad27)") (class "Default")
      (node (ref "J19") (pin "27") (pinfunction "SPSI2_27") (pintype "passive+no_connect"))
    )
    (net (code "245") (name "unconnected-(J_Antenna-Pad1)") (class "Default")
      (node (ref "J_Antenna") (pin "1") (pinfunction "1_1") (pintype "passive+no_connect"))
    )
    (net (code "246") (name "unconnected-(J_Antenna-Pad2)") (class "Default")
      (node (ref "J_Antenna") (pin "2") (pinfunction "2_2") (pintype "passive+no_connect"))
    )
    (net (code "247") (name "unconnected-(J_Antenna-Pad3)") (class "Default")
      (node (ref "J_Antenna") (pin "3") (pinfunction "3_3") (pintype "passive+no_connect"))
    )
    (net (code "248") (name "unconnected-(J_SAR-Pad1)") (class "Default")
      (node (ref "J_SAR") (pin "1") (pinfunction "1_1") (pintype "passive+no_connect"))
    )
    (net (code "249") (name "unconnected-(R1-Pad1)") (class "Default")
      (node (ref "R1") (pin "1") (pinfunction "1_1") (pintype "passive"))
    )
    (net (code "250") (name "unconnected-(R1-Pad2)") (class "Default")
      (node (ref "R1") (pin "2") (pinfunction "2_2") (pintype "passive"))
    )
    (net (code "251") (name "unconnected-(R20-Pad1)") (class "Default")
      (node (ref "R20") (pin "1") (pinfunction "1_1") (pintype "passive+no_connect"))
    )
    (net (code "252") (name "unconnected-(R21-Pad2)") (class "Default")
      (node (ref "R21") (pin "2") (pinfunction "2_2") (pintype "passive+no_connect"))
    )
    (net (code "253") (name "unconnected-(R22-Pad2)") (class "Default")
      (node (ref "R22") (pin "2") (pinfunction "2_2") (pintype "passive+no_connect"))
    )
    (net (code "254") (name "unconnected-(R40-Pad2)") (class "Default")
      (node (ref "R40") (pin "2") (pinfunction "2_2") (pintype "passive+no_connect"))
    )
    (net (code "255") (name "unconnected-(R47-Pad2)") (class "Default")
      (node (ref "R47") (pin "2") (pinfunction "2_2") (pintype "passive+no_connect"))
    )
    (net (code "256") (name "unconnected-(R53-Pad2)") (class "Default")
      (node (ref "R53") (pin "2") (pinfunction "2_2") (pintype "passive+no_connect"))
    )
    (net (code "257") (name "unconnected-(R54-Pad1)") (class "Default")
      (node (ref "R54") (pin "1") (pinfunction "1_1") (pintype "passive+no_connect"))
    )
    (net (code "258") (name "unconnected-(R73-Pad2)") (class "Default")
      (node (ref "R73") (pin "2") (pinfunction "2_2") (pintype "passive+no_connect"))
    )
    (net (code "259") (name "unconnected-(R75-Pad2)") (class "Default")
      (node (ref "R75") (pin "2") (pinfunction "2_2") (pintype "passive+no_connect"))
    )
    (net (code "260") (name "unconnected-(R80-Pad2)") (class "Default")
      (node (ref "R80") (pin "2") (pinfunction "2_2") (pintype "passive+no_connect"))
    )
    (net (code "261") (name "unconnected-(R81-Pad2)") (class "Default")
      (node (ref "R81") (pin "2") (pinfunction "2_2") (pintype "passive+no_connect"))
    )
    (net (code "262") (name "unconnected-(R85-Pad2)") (class "Default")
      (node (ref "R85") (pin "2") (pinfunction "2_2") (pintype "passive+no_connect"))
    )
    (net (code "263") (name "unconnected-(R86-Pad2)") (class "Default")
      (node (ref "R86") (pin "2") (pinfunction "2_2") (pintype "passive+no_connect"))
    )
    (net (code "264") (name "unconnected-(R102-Pad2)") (class "Default")
      (node (ref "R102") (pin "2") (pinfunction "2_2") (pintype "passive+no_connect"))
    )
    (net (code "265") (name "unconnected-(R109-Pad2)") (class "Default")
      (node (ref "R109") (pin "2") (pinfunction "2_2") (pintype "passive+no_connect"))
    )
    (net (code "266") (name "unconnected-(R110-Pad2)") (class "Default")
      (node (ref "R110") (pin "2") (pinfunction "2_2") (pintype "passive+no_connect"))
    )
    (net (code "267") (name "unconnected-(R114-Pad2)") (class "Default")
      (node (ref "R114") (pin "2") (pinfunction "2_2") (pintype "passive+no_connect"))
    )
    (net (code "268") (name "unconnected-(R115-Pad2)") (class "Default")
      (node (ref "R115") (pin "2") (pinfunction "2_2") (pintype "passive+no_connect"))
    )
    (net (code "269") (name "unconnected-(R124-Pad2)") (class "Default")
      (node (ref "R124") (pin "2") (pinfunction "2_2") (pintype "passive+no_connect"))
    )
    (net (code "270") (name "unconnected-(R125-Pad2)") (class "Default")
      (node (ref "R125") (pin "2") (pinfunction "2_2") (pintype "passive+no_connect"))
    )
    (net (code "271") (name "unconnected-(R126-Pad2)") (class "Default")
      (node (ref "R126") (pin "2") (pinfunction "2_2") (pintype "passive+no_connect"))
    )
    (net (code "272") (name "unconnected-(R127-Pad2)") (class "Default")
      (node (ref "R127") (pin "2") (pinfunction "2_2") (pintype "passive+no_connect"))
    )
    (net (code "273") (name "unconnected-(R128-Pad2)") (class "Default")
      (node (ref "R128") (pin "2") (pinfunction "2_2") (pintype "passive+no_connect"))
    )
    (net (code "274") (name "unconnected-(R129-Pad2)") (class "Default")
      (node (ref "R129") (pin "2") (pinfunction "2_2") (pintype "passive+no_connect"))
    )
    (net (code "275") (name "unconnected-(R130-Pad2)") (class "Default")
      (node (ref "R130") (pin "2") (pinfunction "2_2") (pintype "passive+no_connect"))
    )
    (net (code "276") (name "unconnected-(U8-EN-Pad3)") (class "Default")
      (node (ref "U8") (pin "3") (pinfunction "EN_3") (pintype "passive+no_connect"))
    )
    (net (code "277") (name "unconnected-(U11-PWRGD-Pad8)") (class "Default")
      (node (ref "U11") (pin "8") (pinfunction "PWRGD_8") (pintype "output+no_connect"))
    )
    (net (code "278") (name "unconnected-(U12-PWRGD-Pad8)") (class "Default")
      (node (ref "U12") (pin "8") (pinfunction "PWRGD_8") (pintype "output+no_connect"))
    )
    (net (code "279") (name "unconnected-(U17-EN-Pad3)") (class "Default")
      (node (ref "U17") (pin "3") (pinfunction "EN_3") (pintype "passive+no_connect"))
    )
    (net (code "280") (name "unconnected-(U20-PWRGD-Pad8)") (class "Default")
      (node (ref "U20") (pin "8") (pinfunction "PWRGD_8") (pintype "output+no_connect"))
    )
    (net (code "281") (name "unconnected-(U21-PWRGD-Pad8)") (class "Default")
      (node (ref "U21") (pin "8") (pinfunction "PWRGD_8") (pintype "output+no_connect"))
    )
    (net (code "282") (name "unconnected-(U22-PWRGD-Pad8)") (class "Default")
      (node (ref "U22") (pin "8") (pinfunction "PWRGD_8") (pintype "output+no_connect"))
    )
    (net (code "283") (name "unconnected-(U28-EN-Pad3)") (class "Default")
      (node (ref "U28") (pin "3") (pinfunction "EN_3") (pintype "passive+no_connect"))
    )
    (net (code "284") (name "unconnected-(U30-PWRGD-Pad8)") (class "Default")
      (node (ref "U30") (pin "8") (pinfunction "PWRGD_8") (pintype "output+no_connect"))
    )
    (net (code "285") (name "unconnected-(U31-PWRGD-Pad8)") (class "Default")
      (node (ref "U31") (pin "8") (pinfunction "PWRGD_8") (pintype "output+no_connect"))
    )
    (net (code "286") (name "unconnected-(U32-PWRGD-Pad8)") (class "Default")
      (node (ref "U32") (pin "8") (pinfunction "PWRGD_8") (pintype "output+no_connect"))
    )
    (net (code "287") (name "unconnected-(U35-PWRGD-Pad8)") (class "Default")
      (node (ref "U35") (pin "8") (pinfunction "PWRGD_8") (pintype "output+no_connect"))
    )
    (net (code "288") (name "unconnected-(U36-PWRGD-Pad8)") (class "Default")
      (node (ref "U36") (pin "8") (pinfunction "PWRGD_8") (pintype "output+no_connect"))
    )
    (net (code "289") (name "unconnected-(U37-A0-Pad13)") (class "Default")
      (node (ref "U37") (pin "13") (pinfunction "A0_13") (pintype "passive+no_connect"))
    )
    (net (code "290") (name "unconnected-(U37-A3-Pad12)") (class "Default")
      (node (ref "U37") (pin "12") (pinfunction "A3_12") (pintype "passive+no_connect"))
    )
    (net (code "291") (name "unconnected-(U38-A5-Pad5)") (class "Default")
      (node (ref "U38") (pin "5") (pinfunction "A5_5") (pintype "passive+no_connect"))
    )
  )
)
